# WMHS_Eastern_LI_Invitational_Circuit_Boa.net
KiCad netlist of a schematic drawn in EAGLE
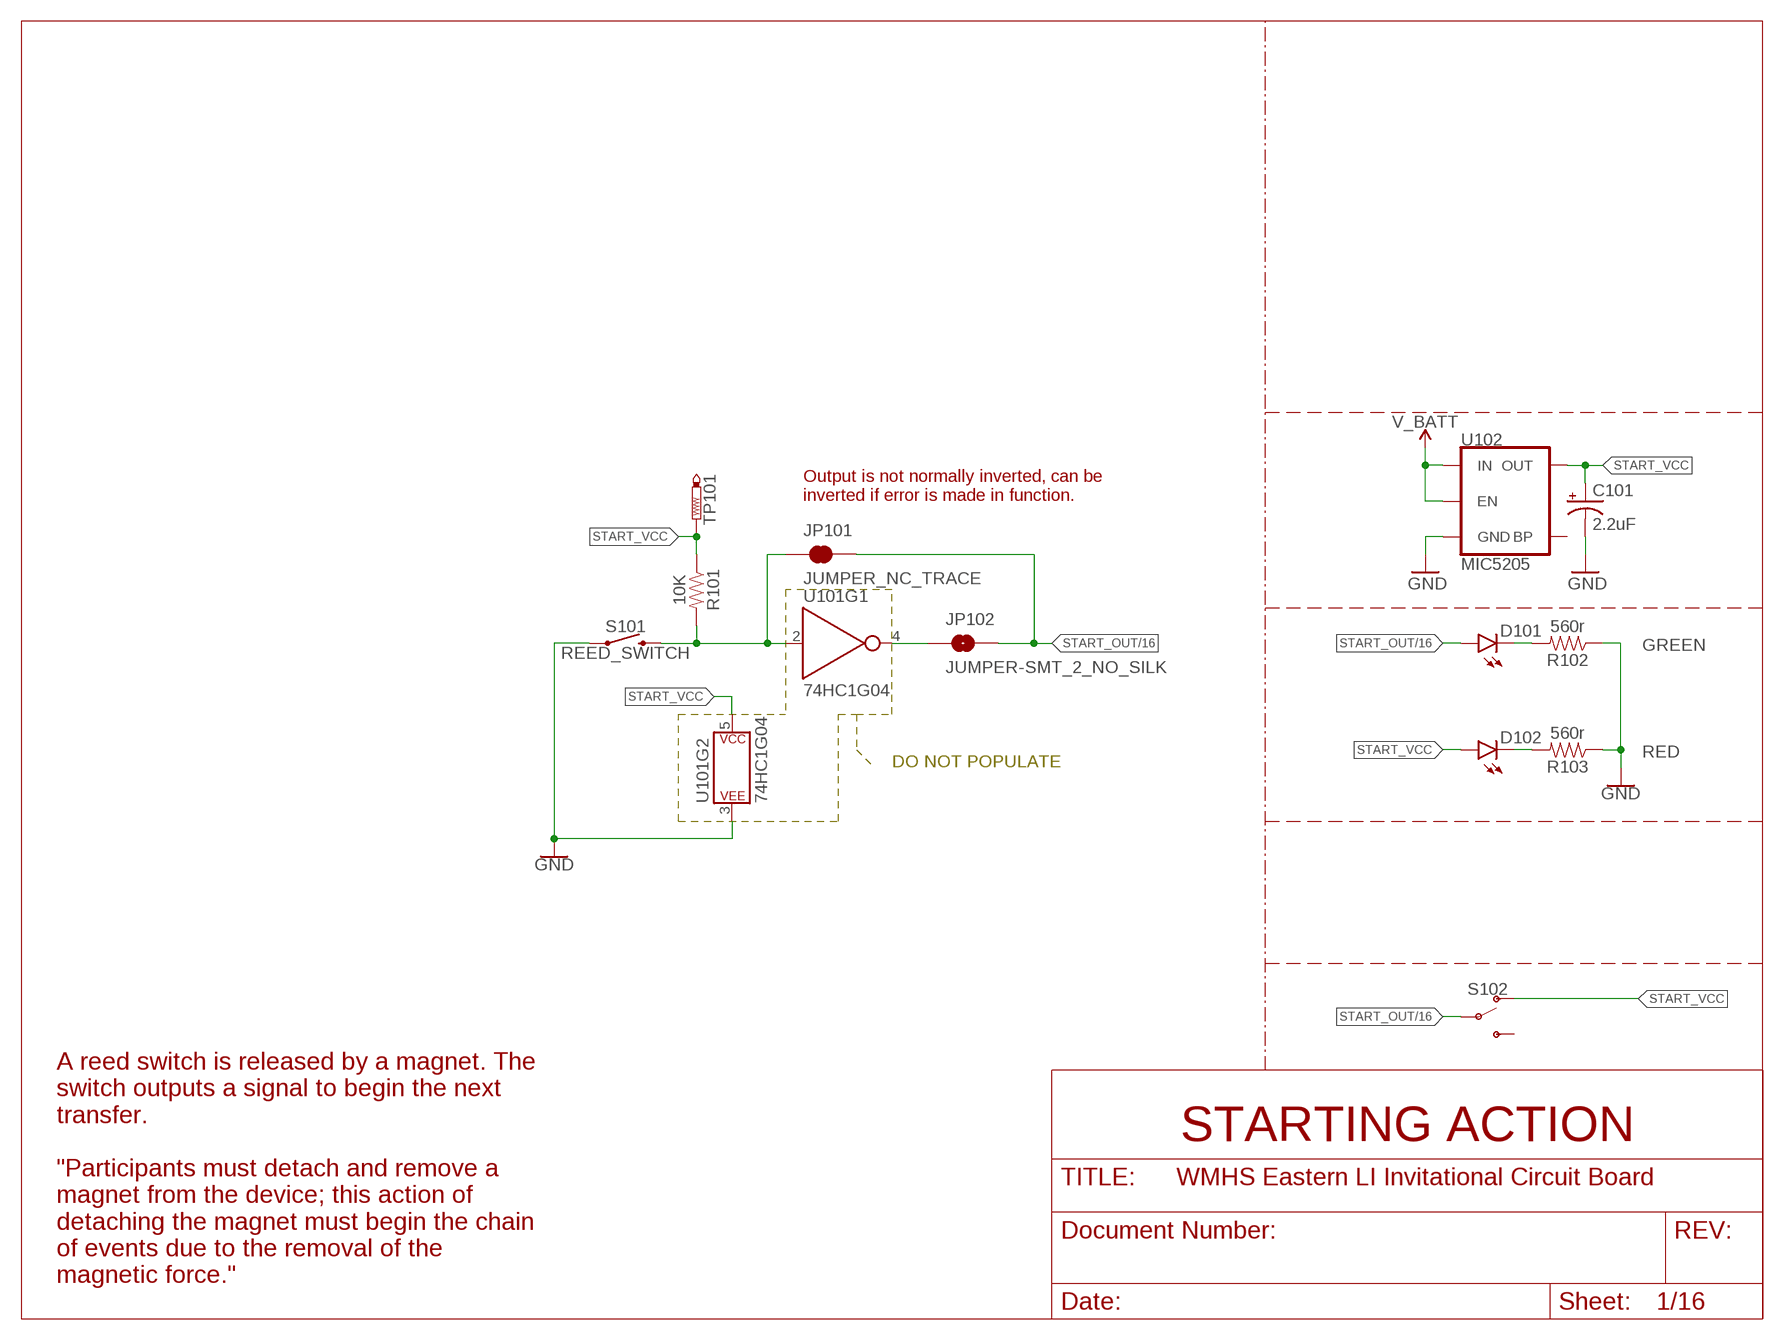
[diagram p0: schematic, sheet 1]
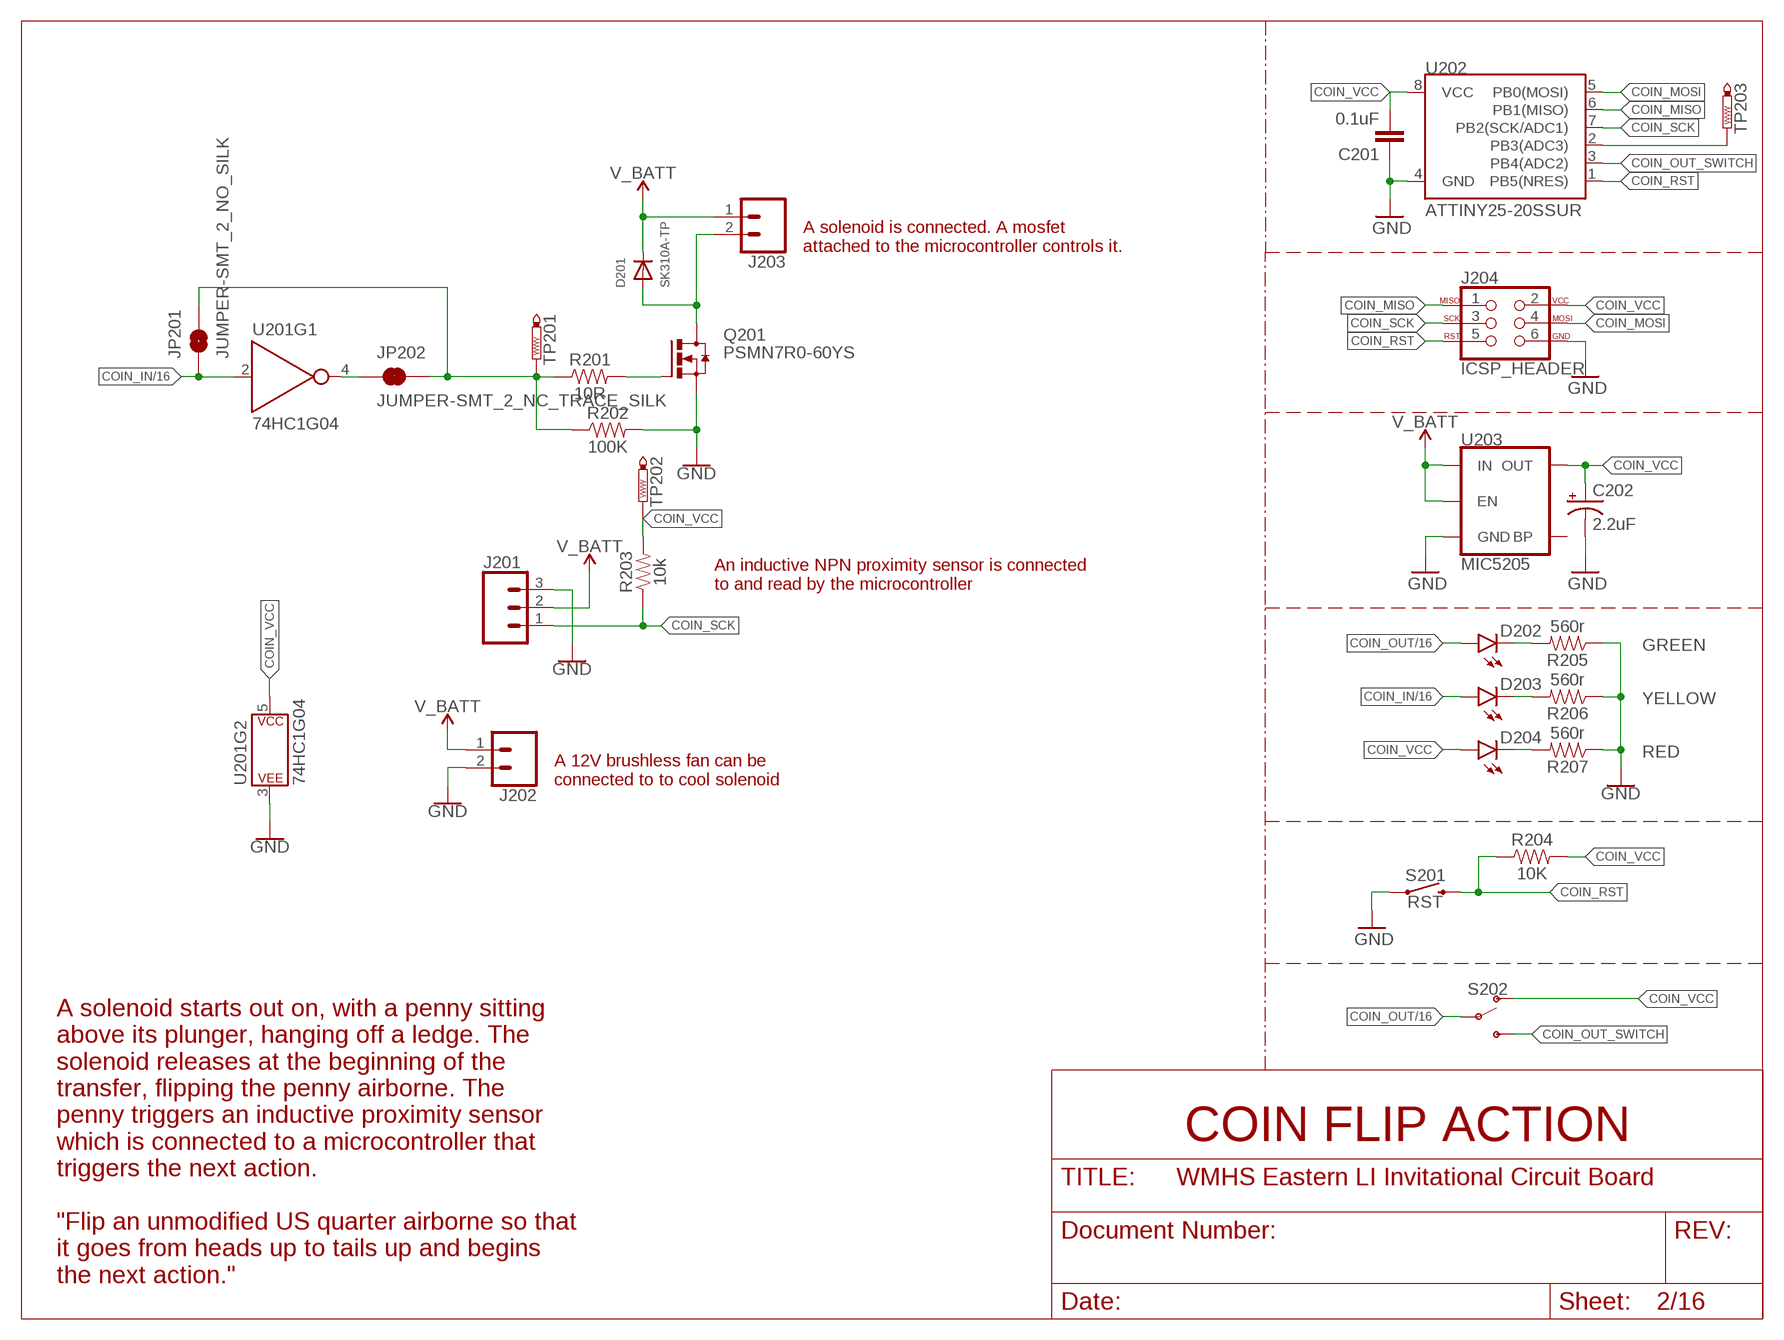
[diagram p1: schematic, sheet 2]
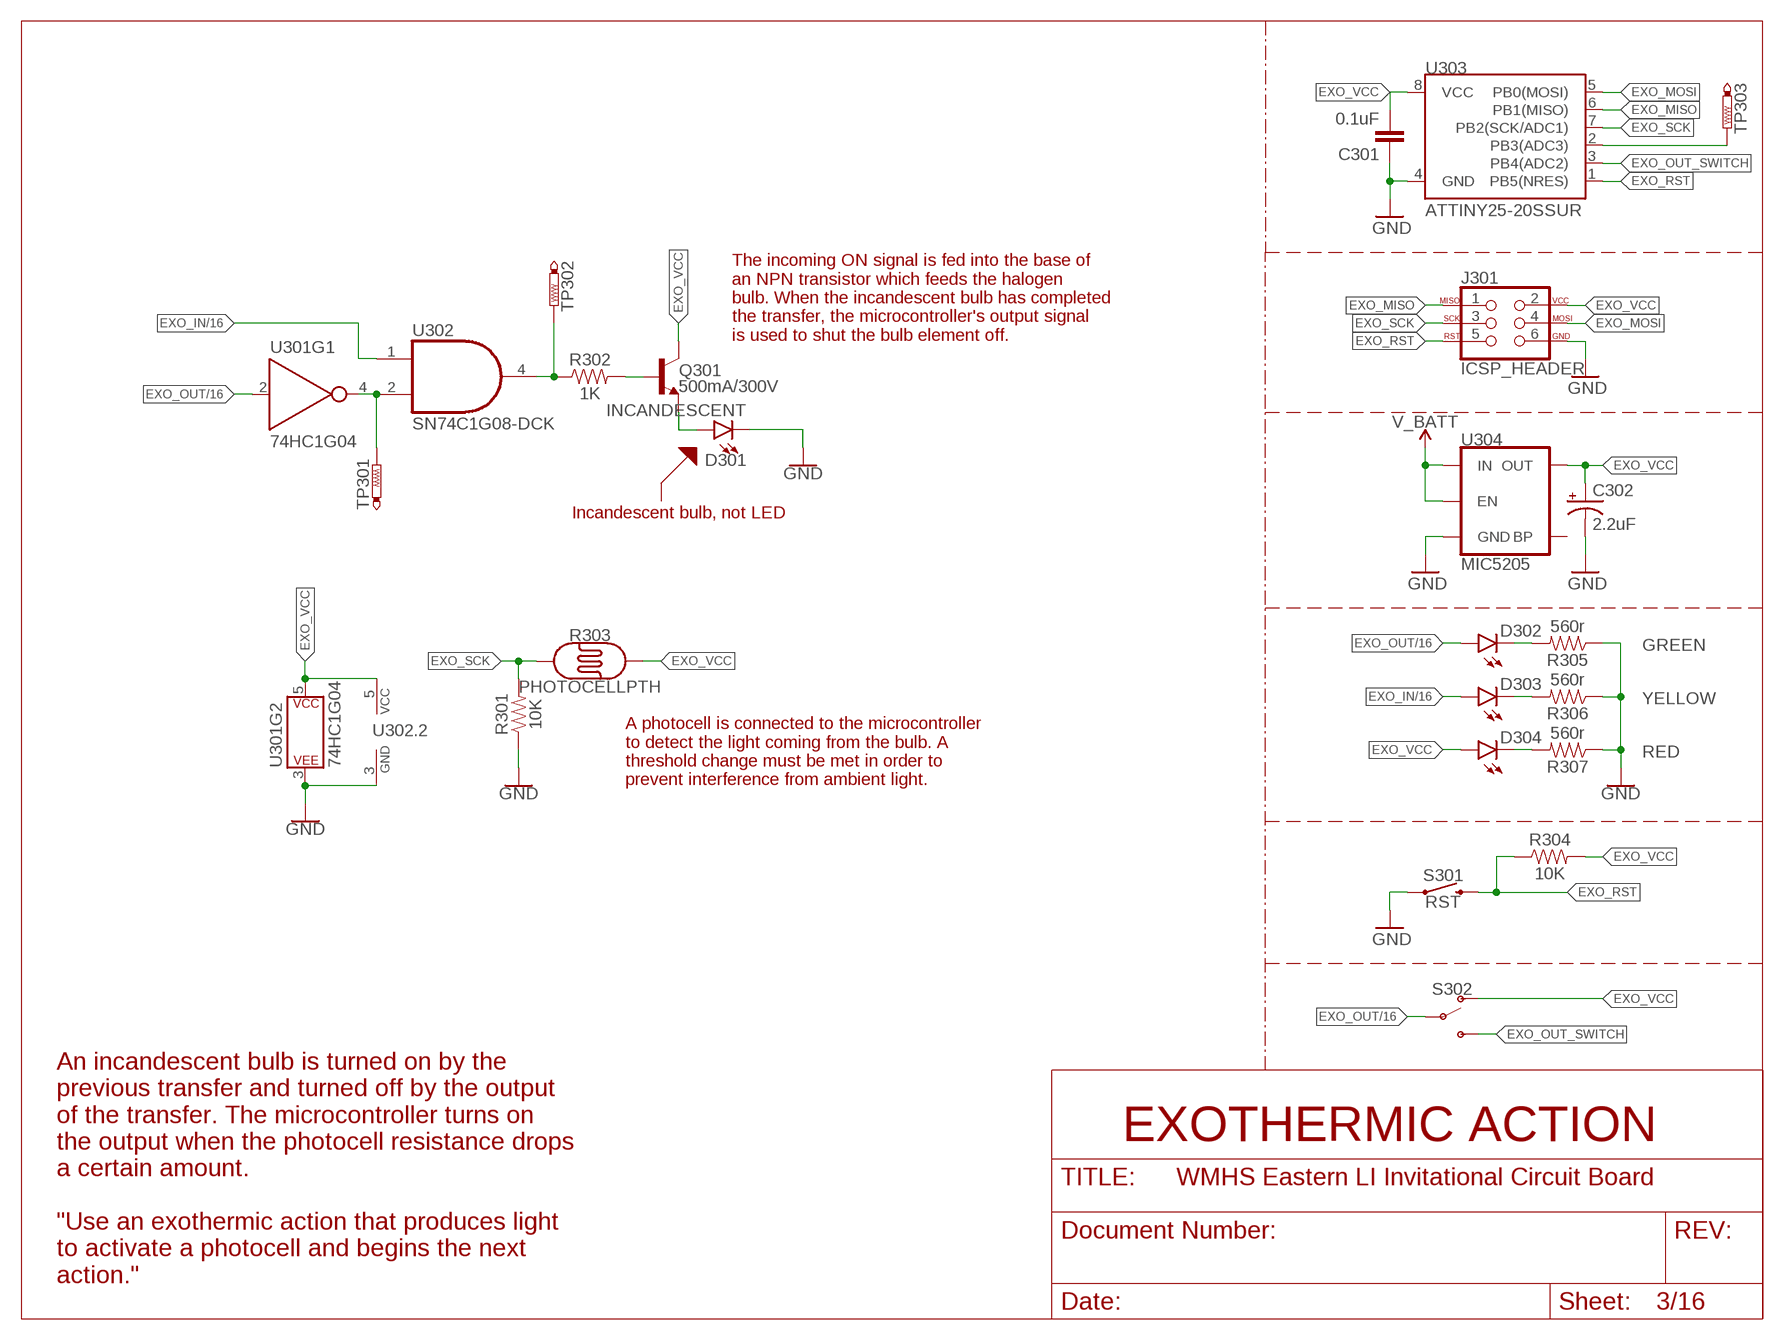
[diagram p2: schematic, sheet 3]
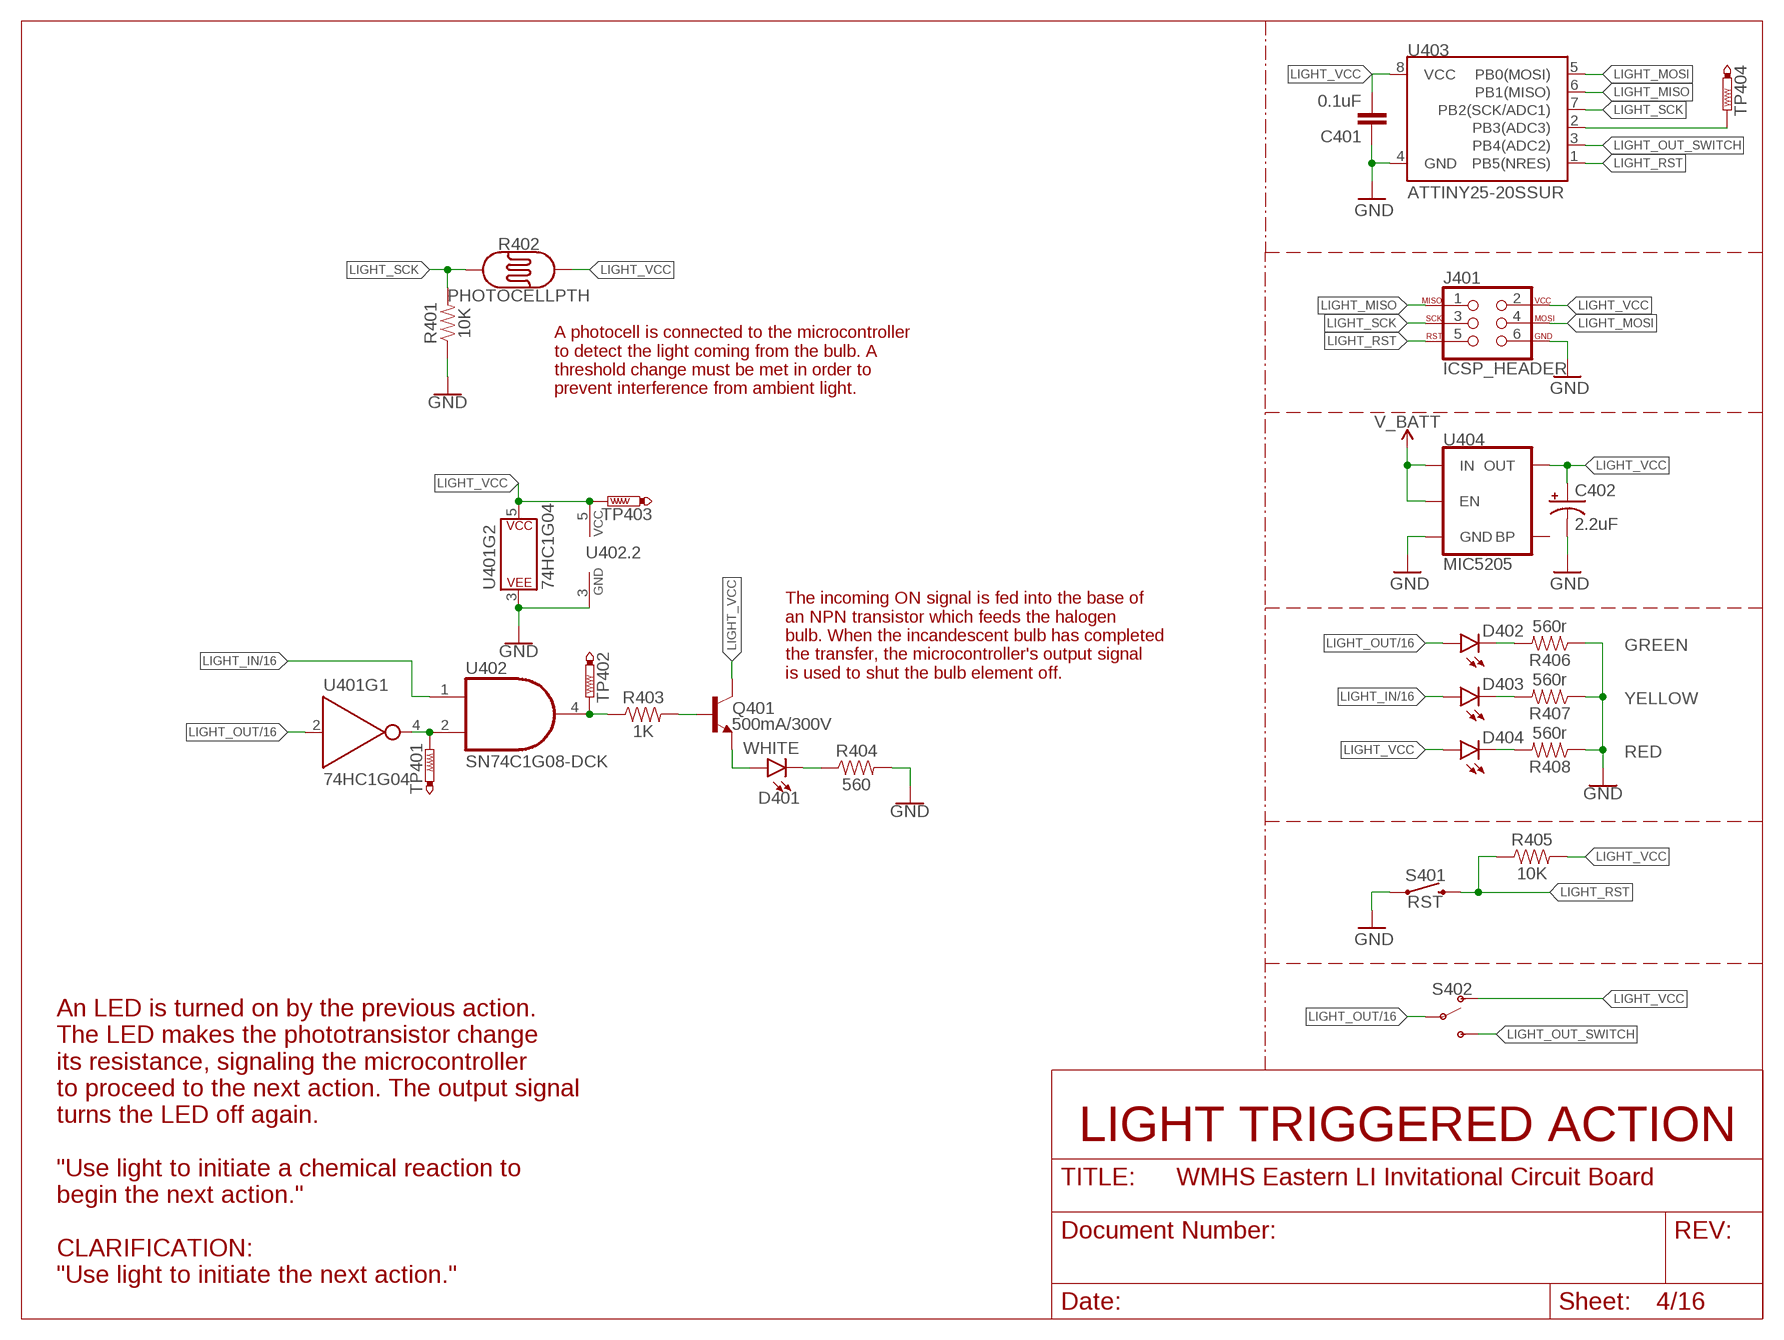
[diagram p3: schematic, sheet 4]
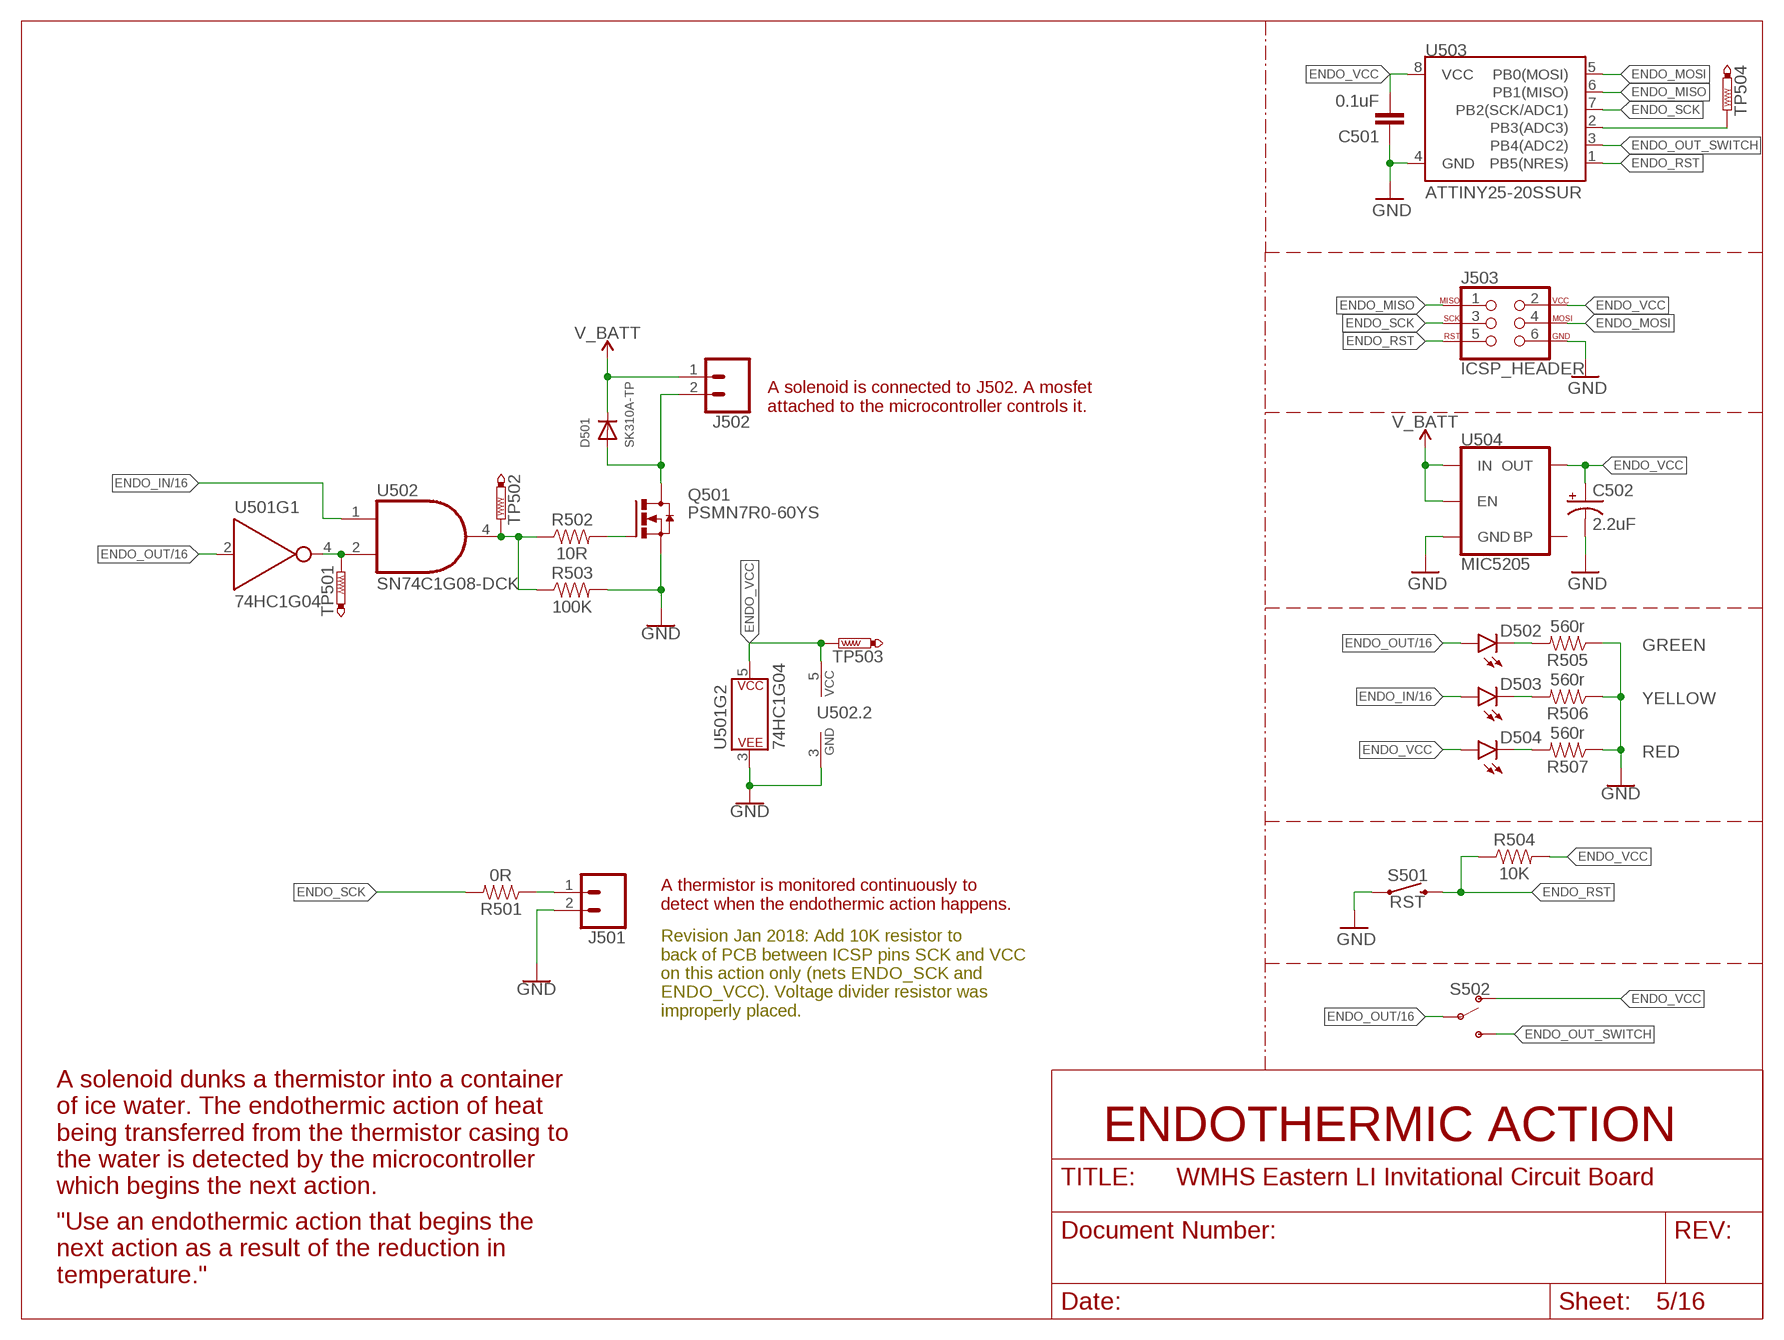
[diagram p4: schematic, sheet 5]
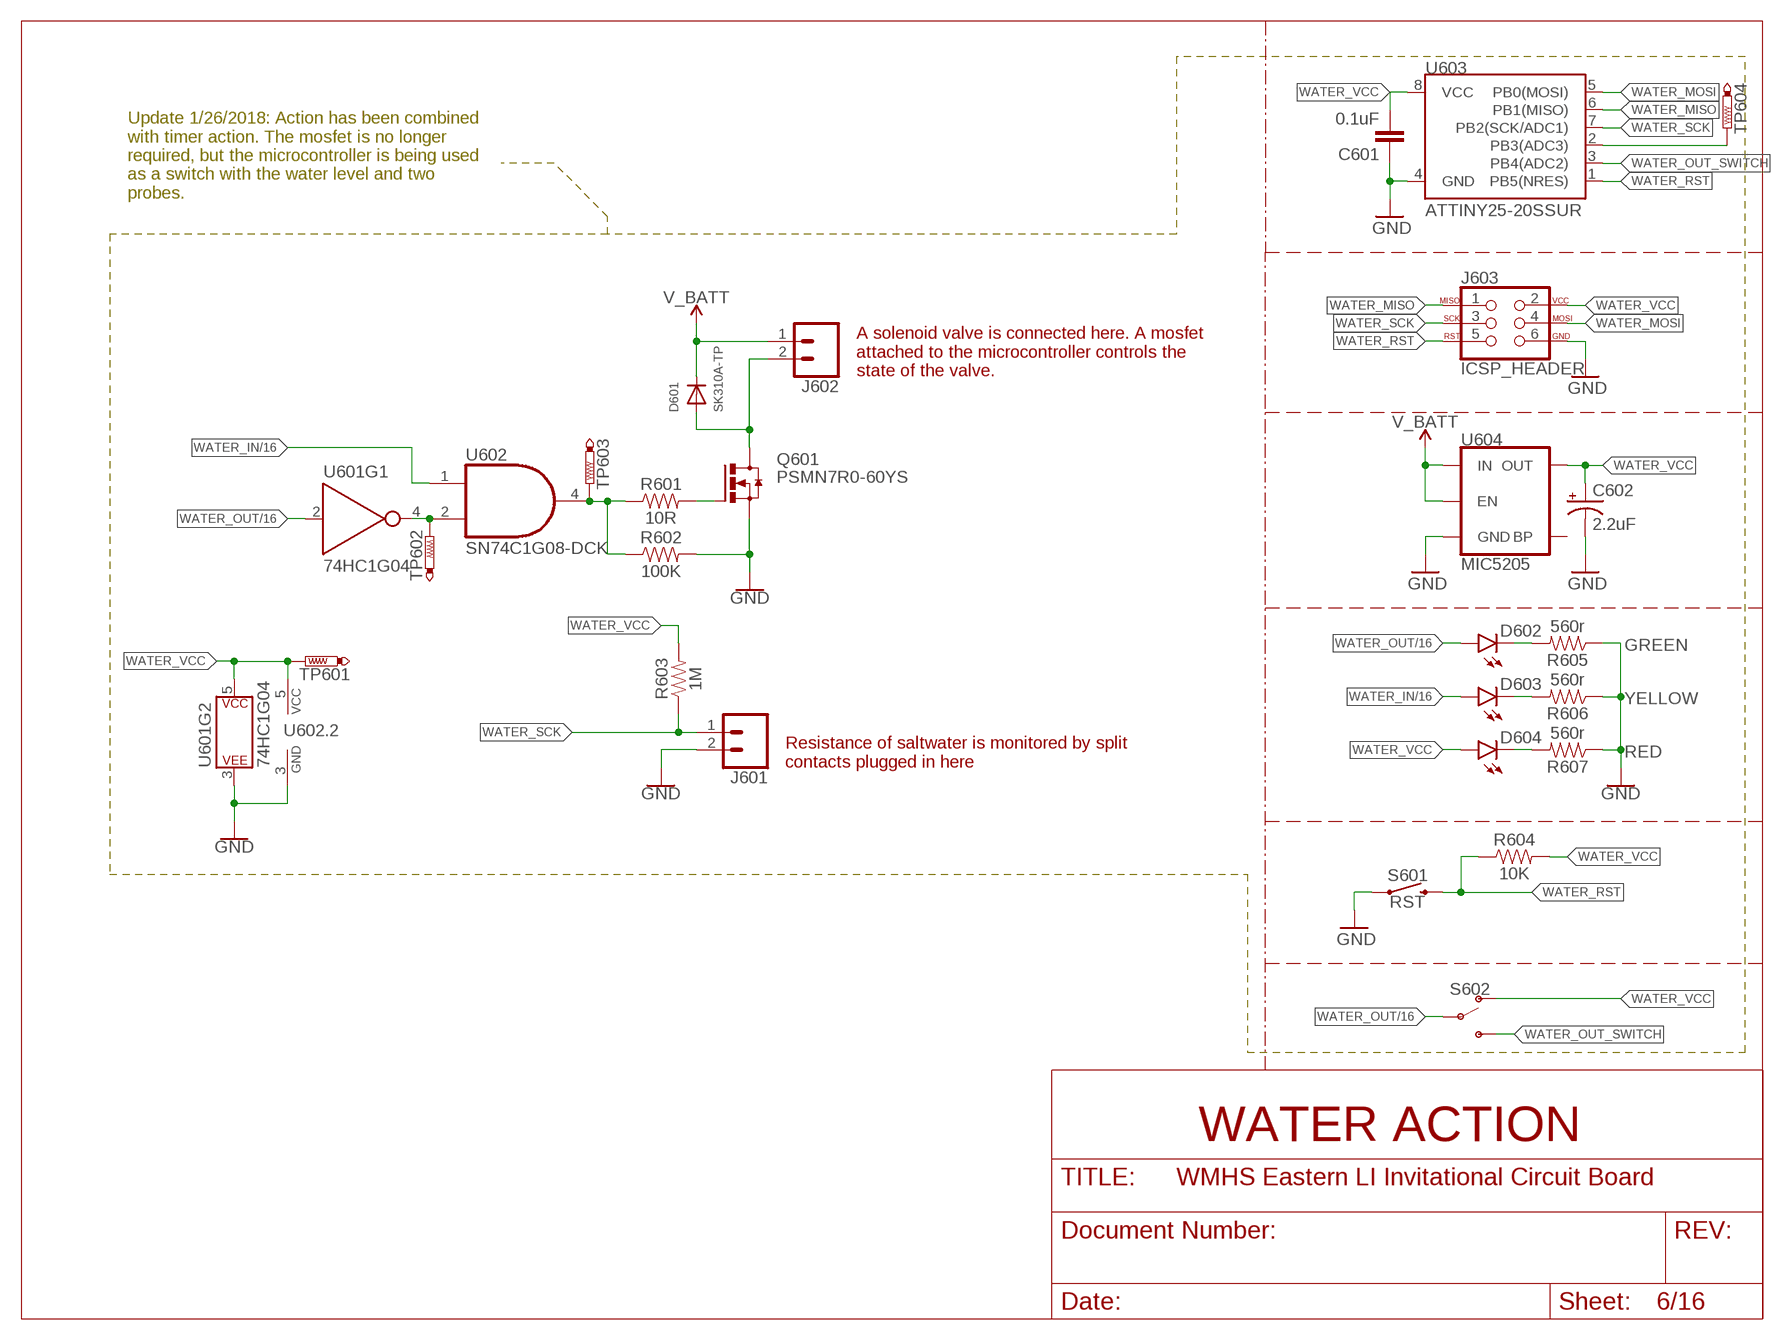
[diagram p5: schematic, sheet 6]
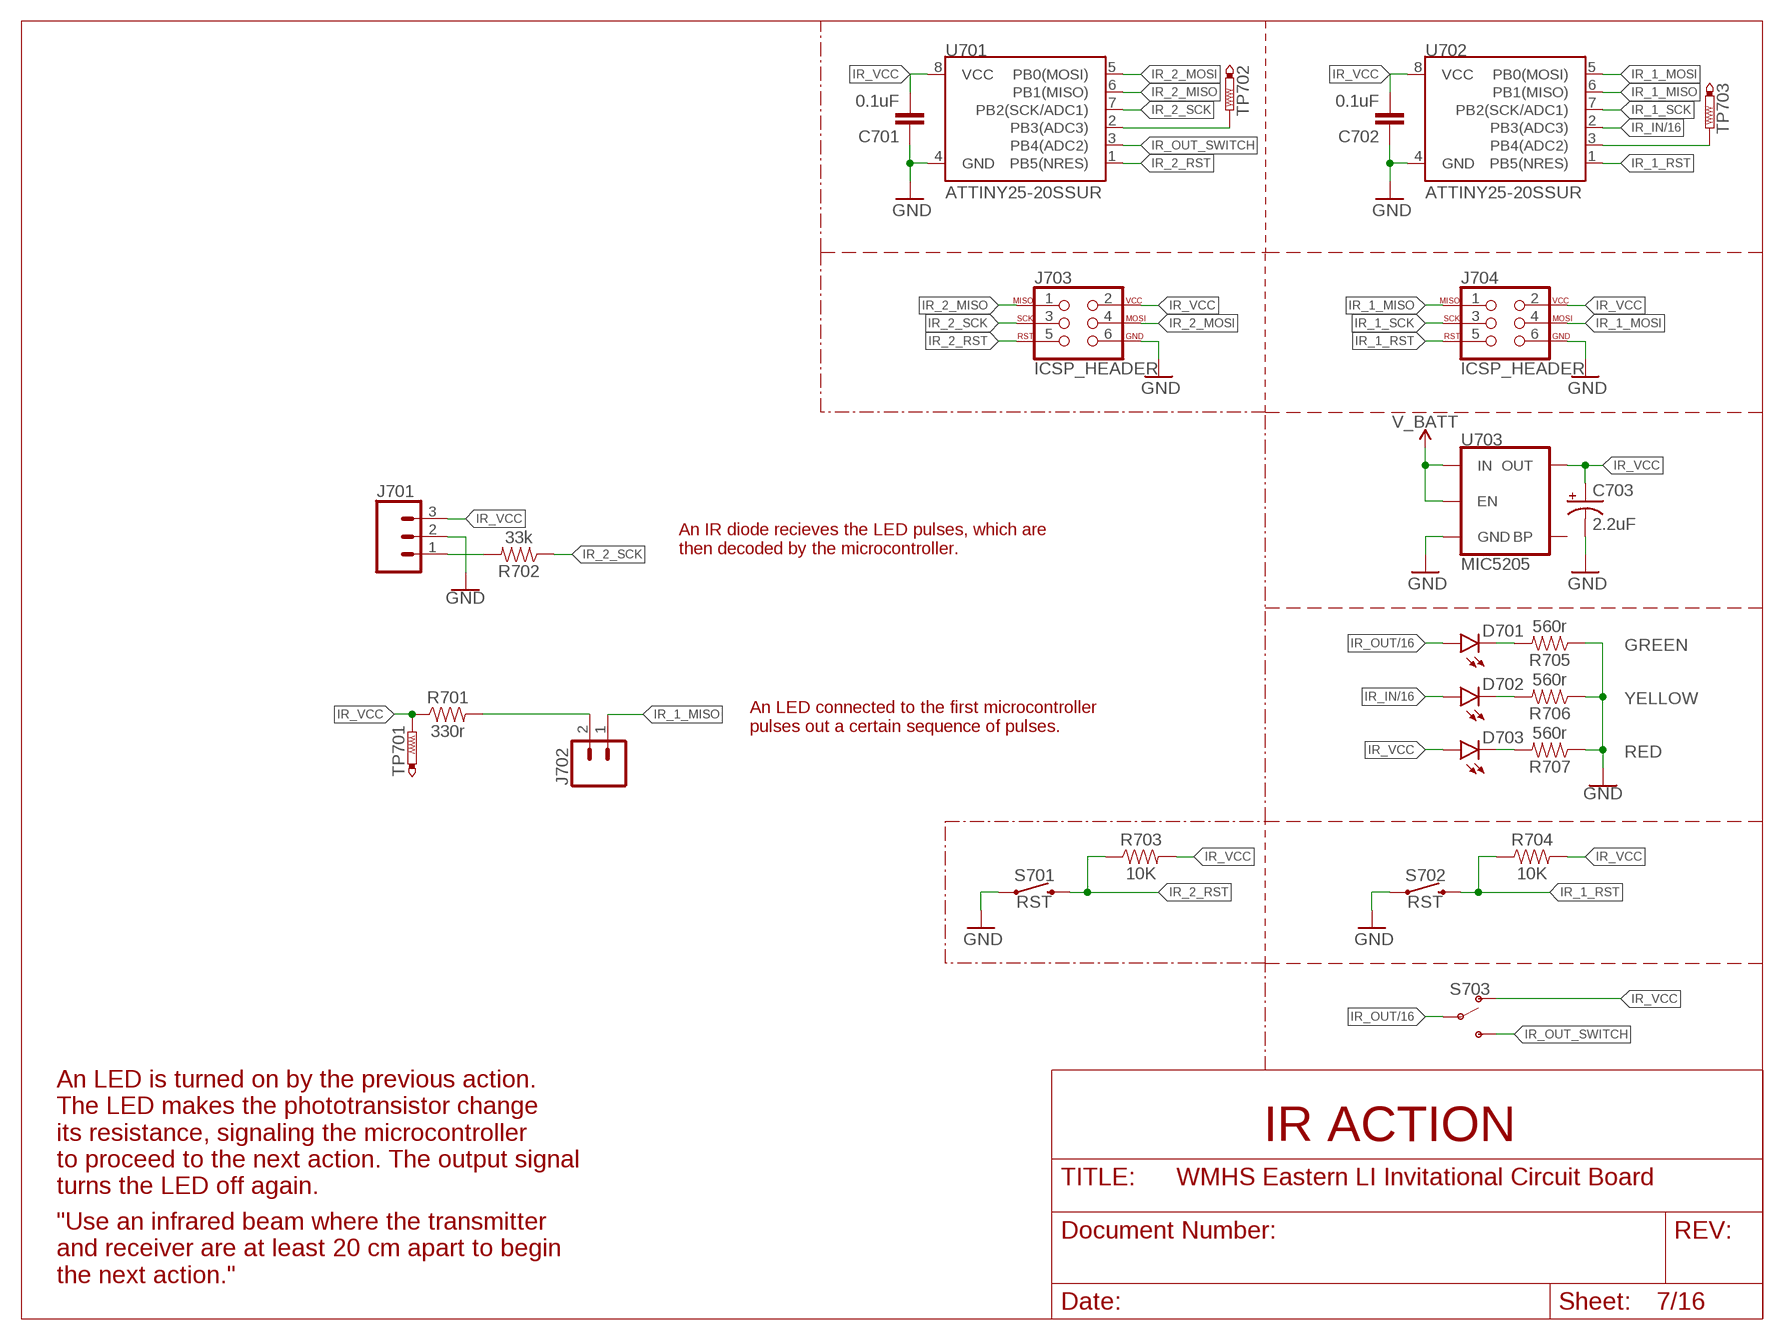
[diagram p6: schematic, sheet 7]
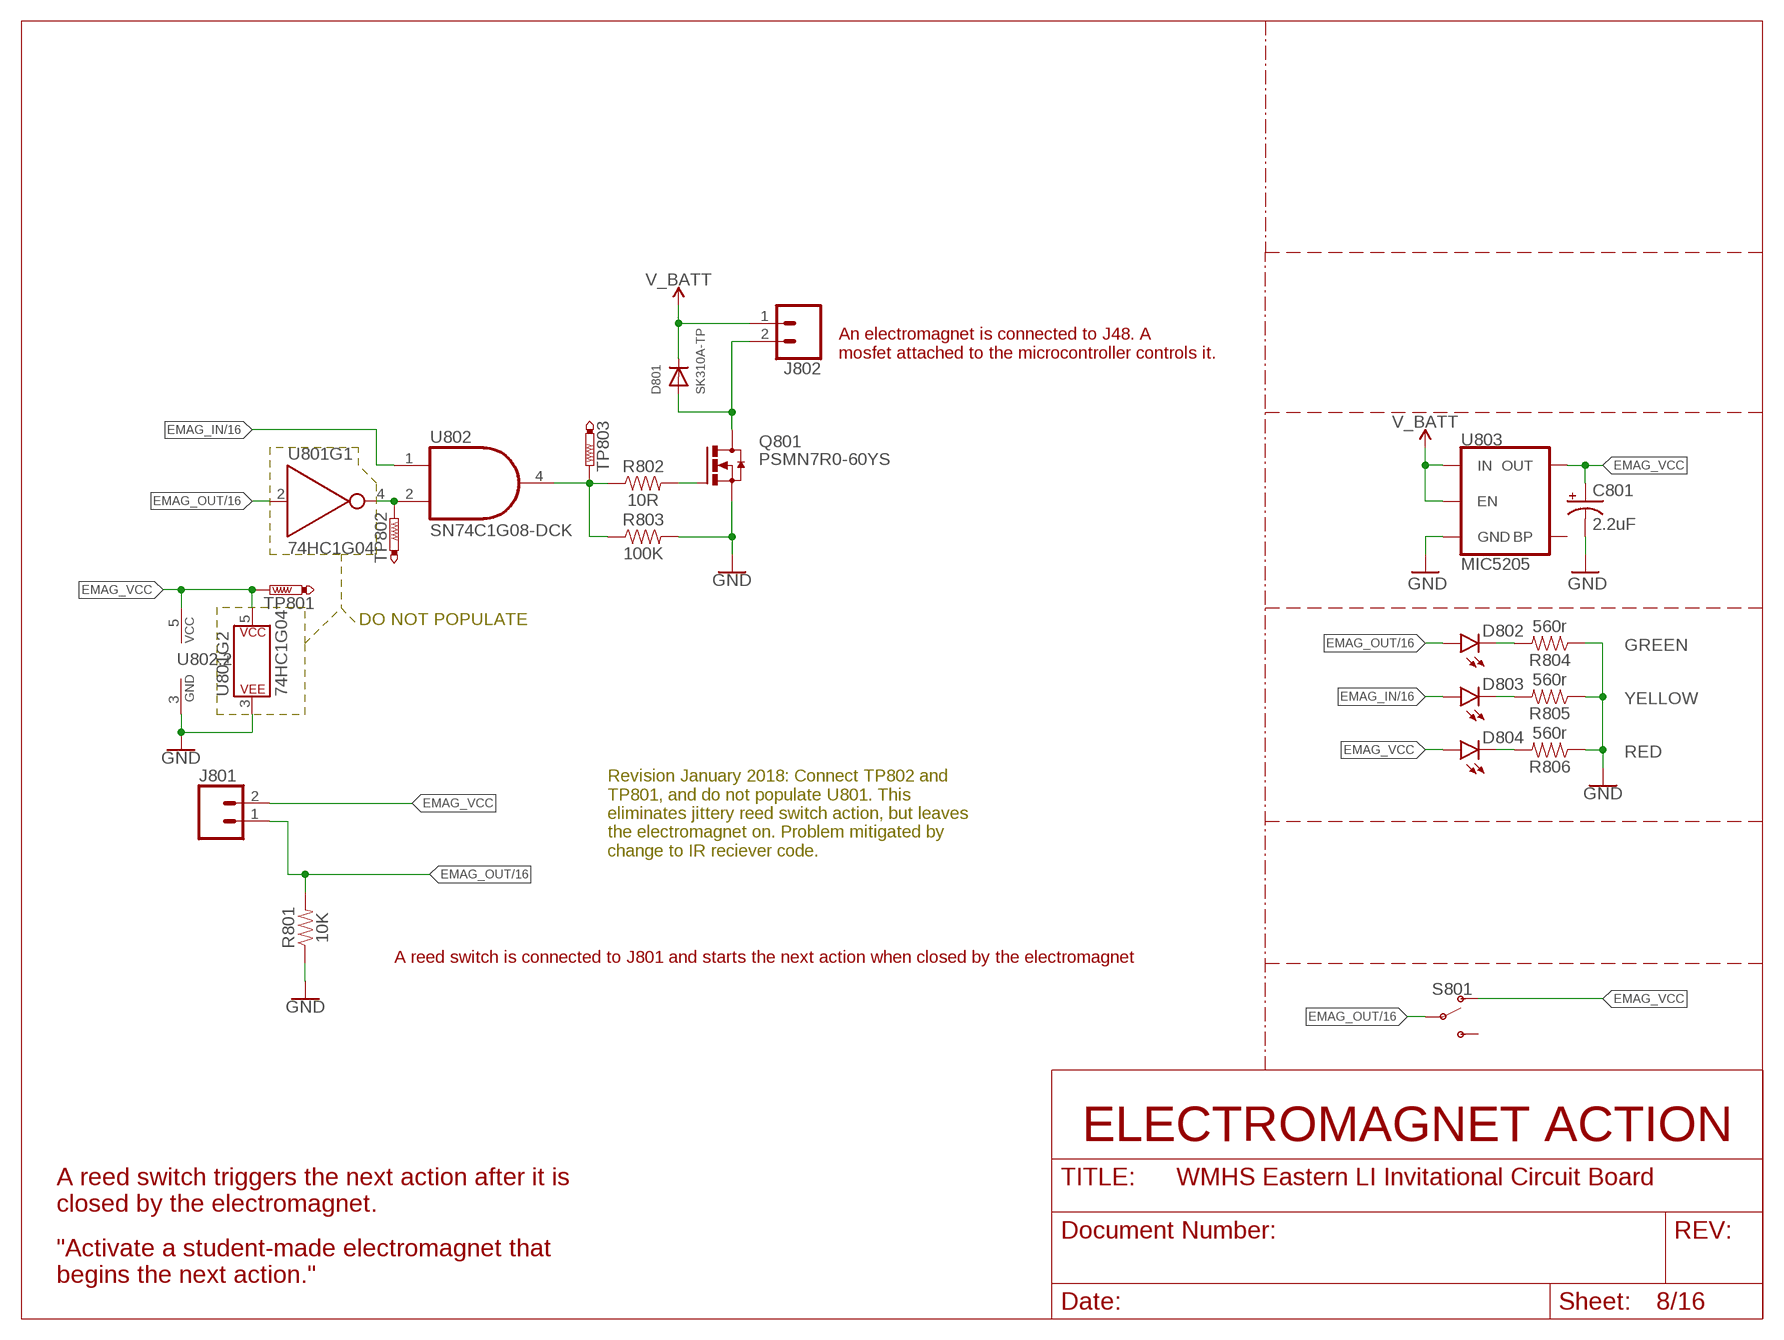
[diagram p7: schematic, sheet 8]
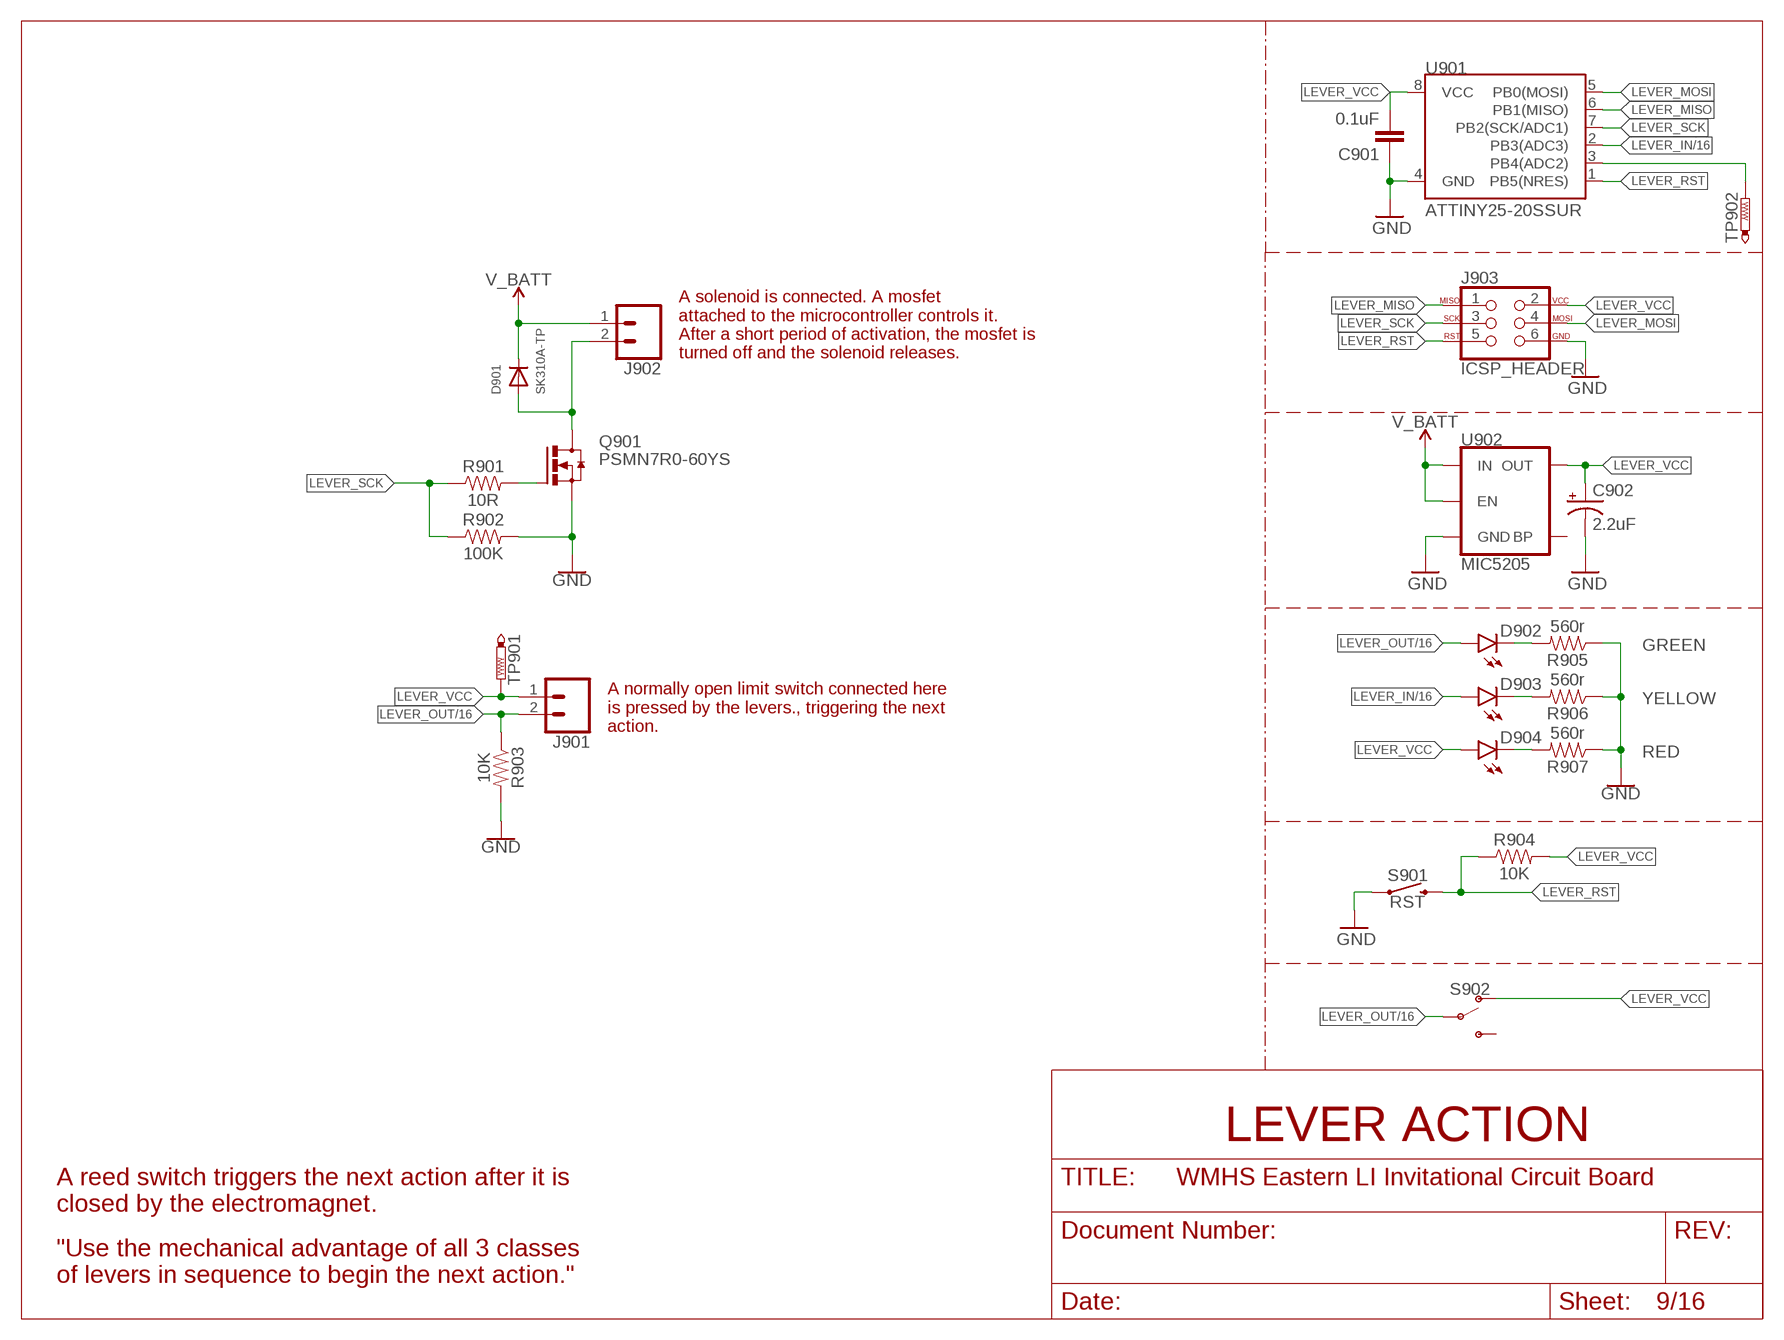
[diagram p8: schematic, sheet 9]
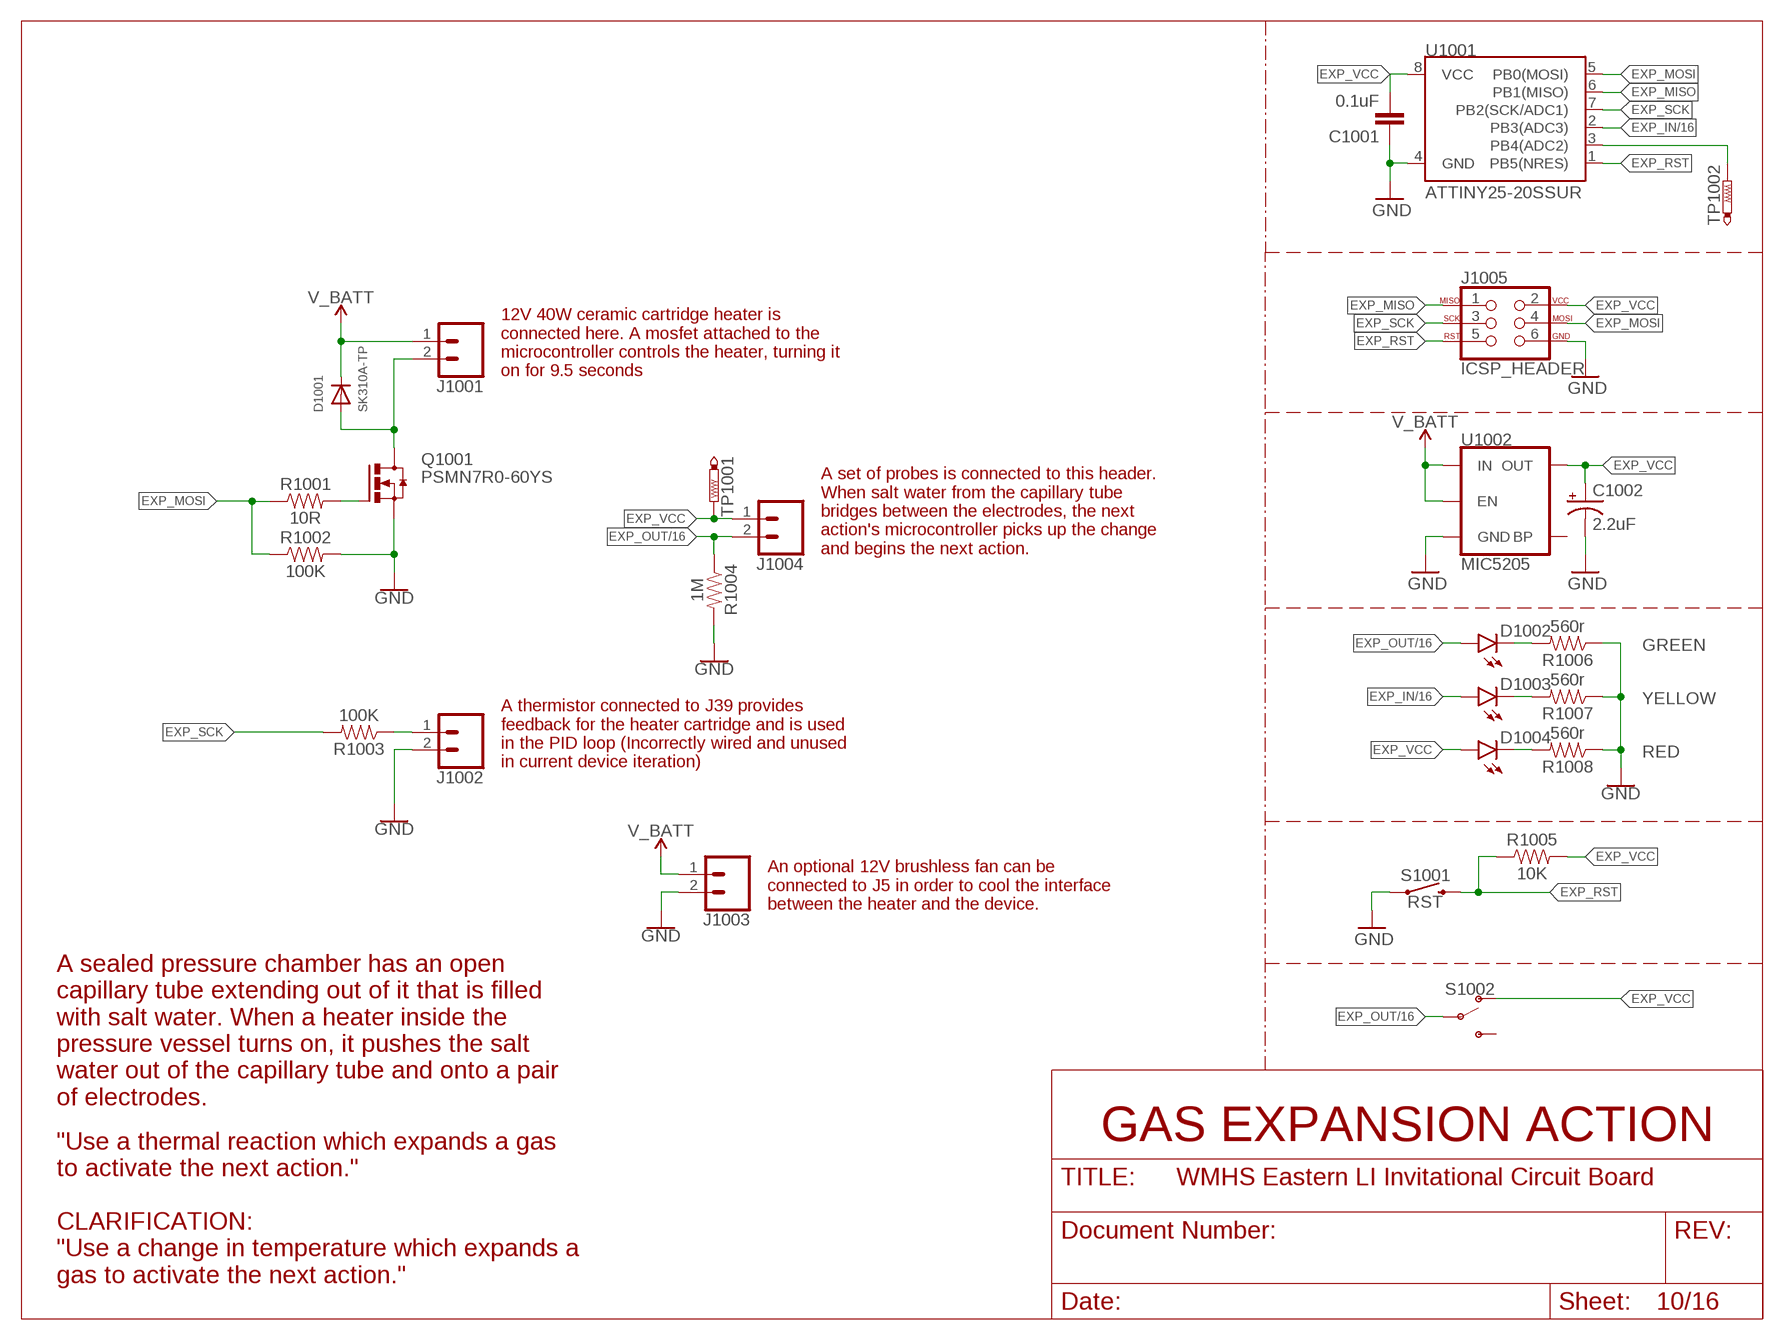
[diagram p9: schematic, sheet 10]
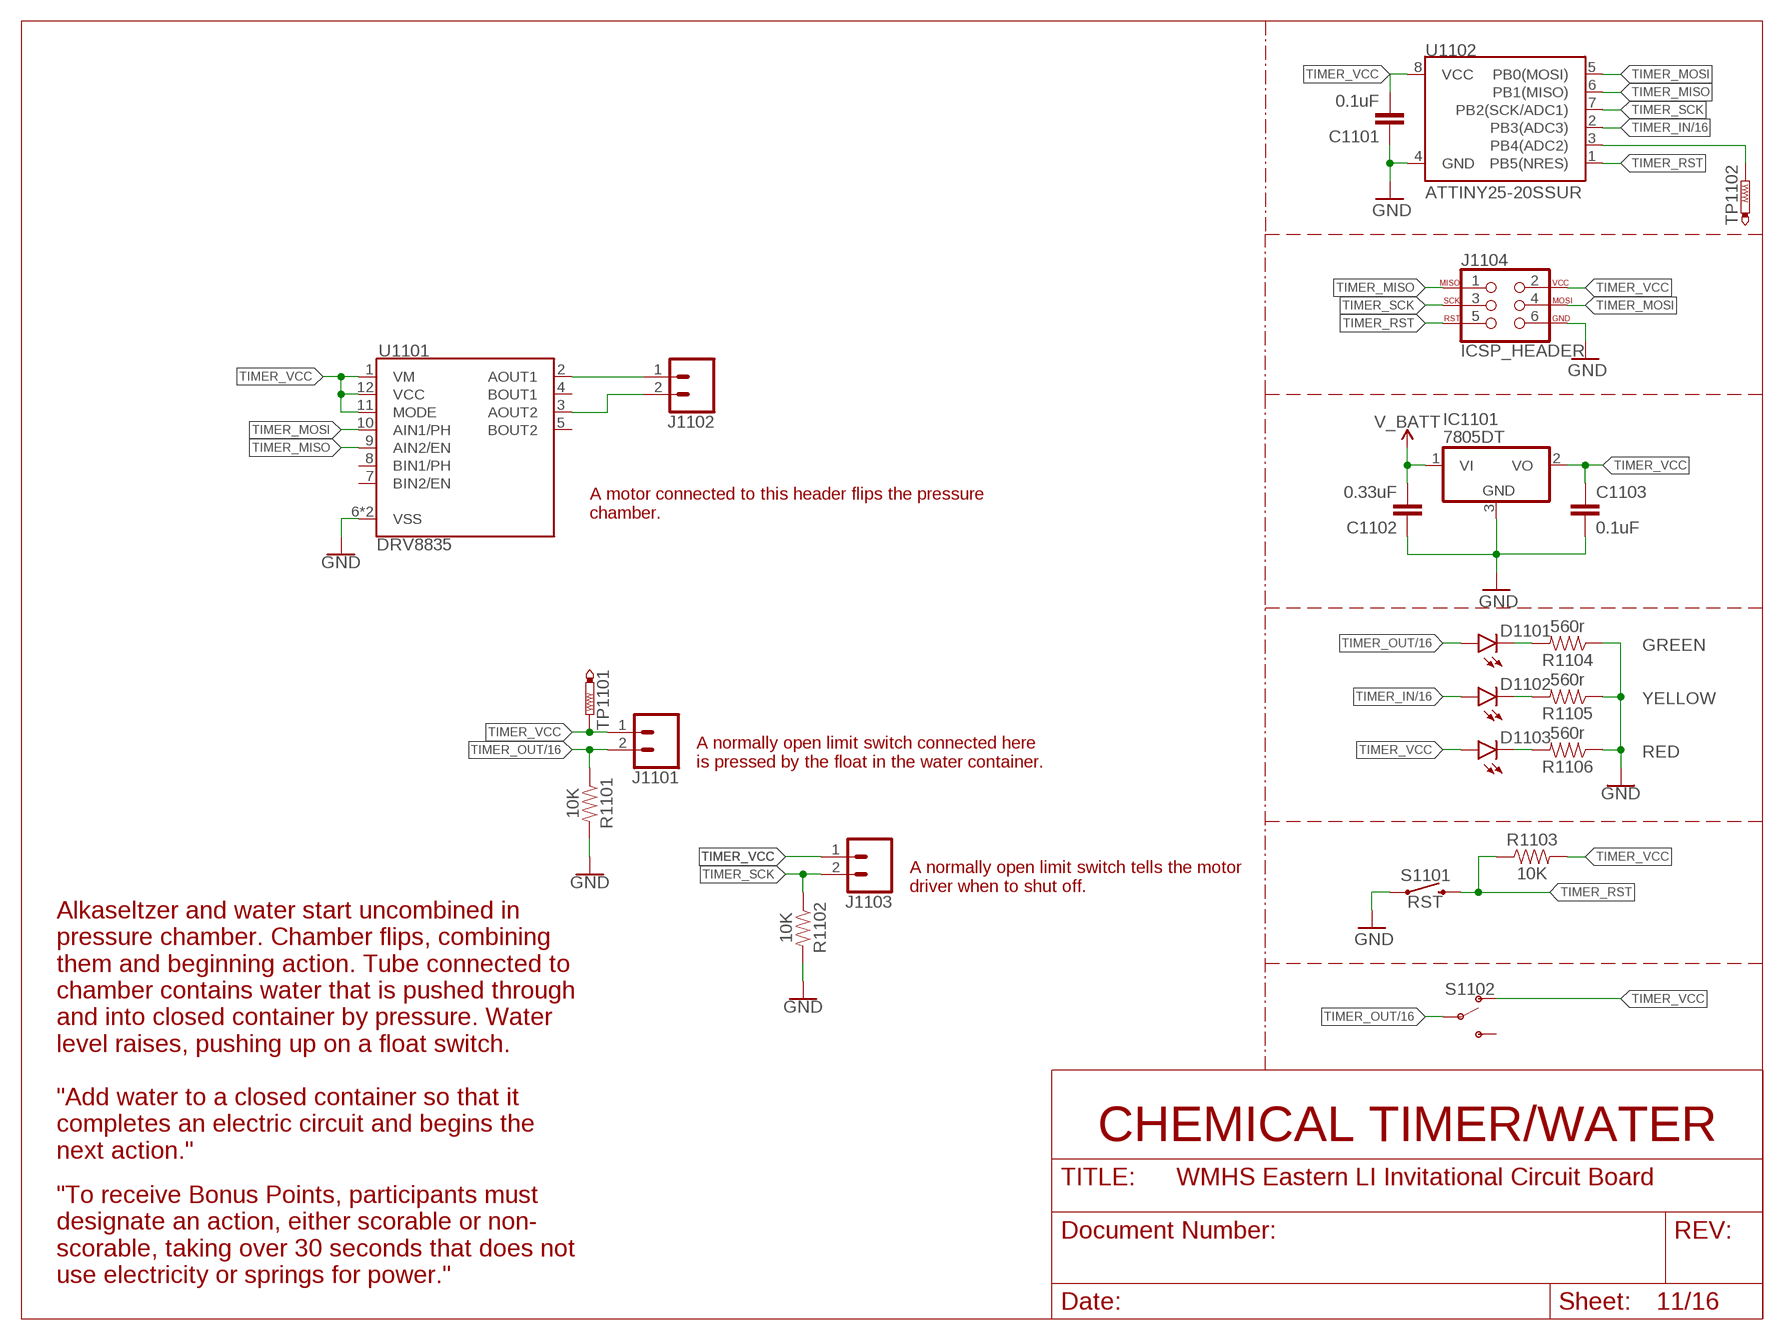
[diagram p10: schematic, sheet 11]
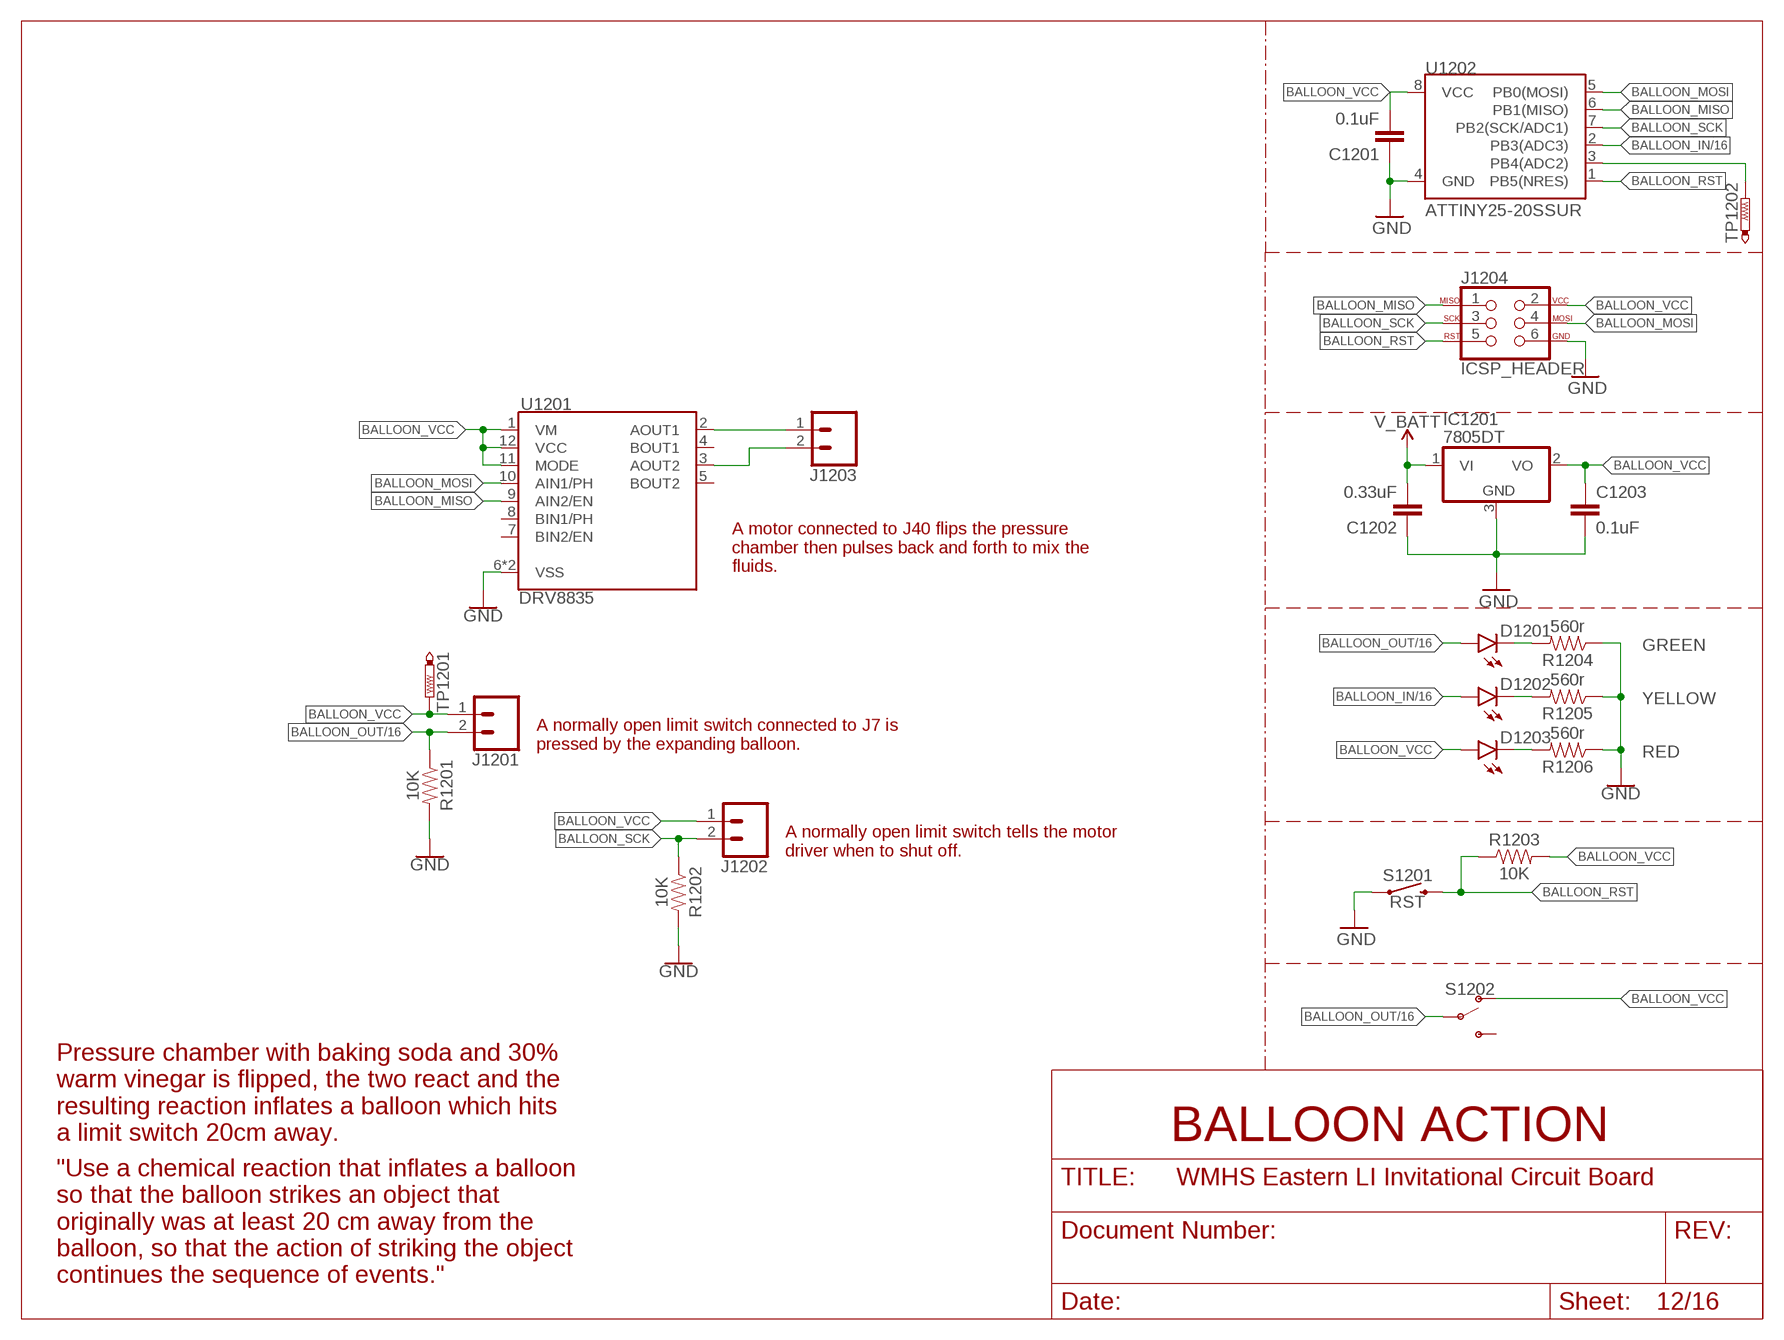
[diagram p11: schematic, sheet 12]
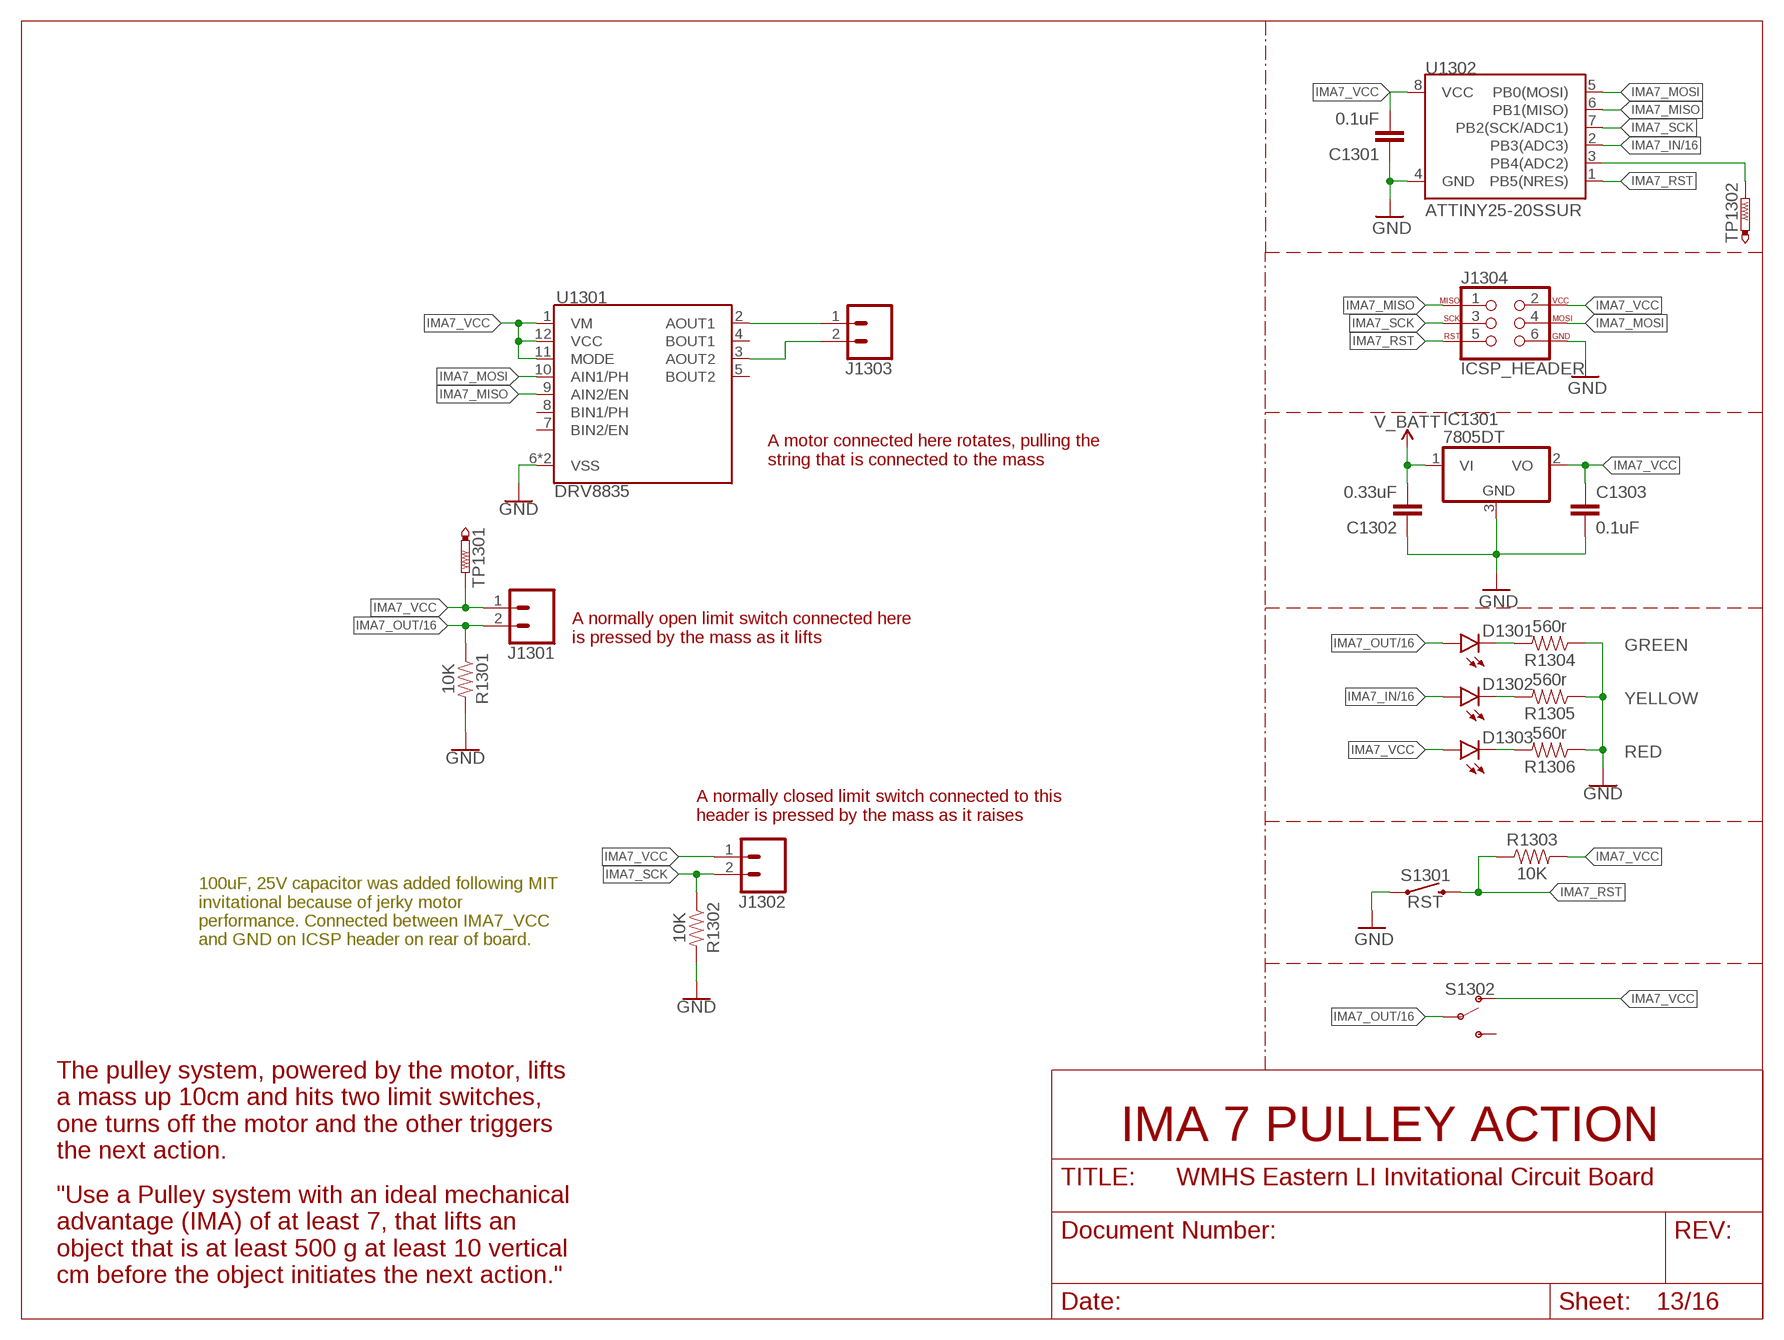
[diagram p12: schematic, sheet 13]
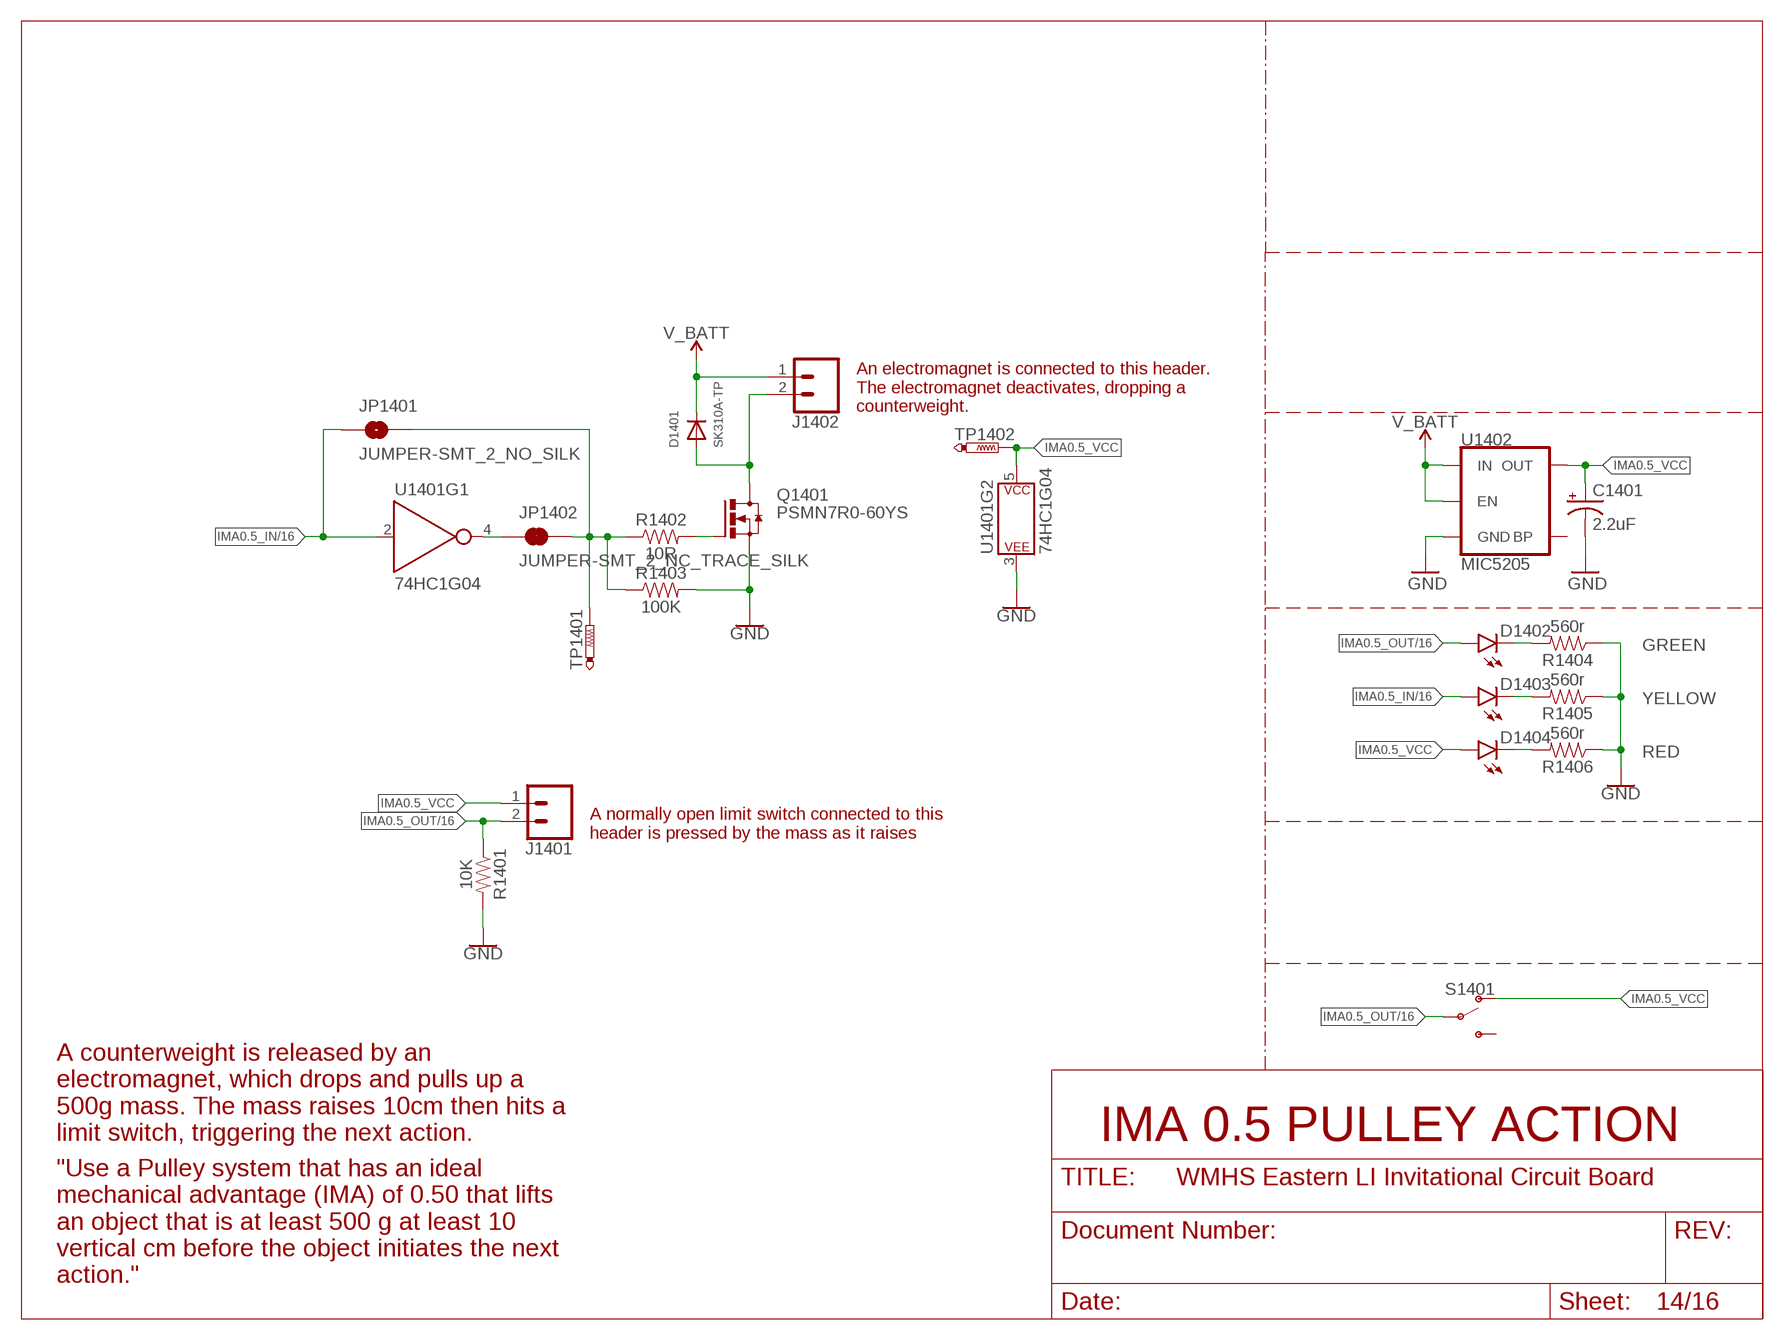
[diagram p13: schematic, sheet 14]
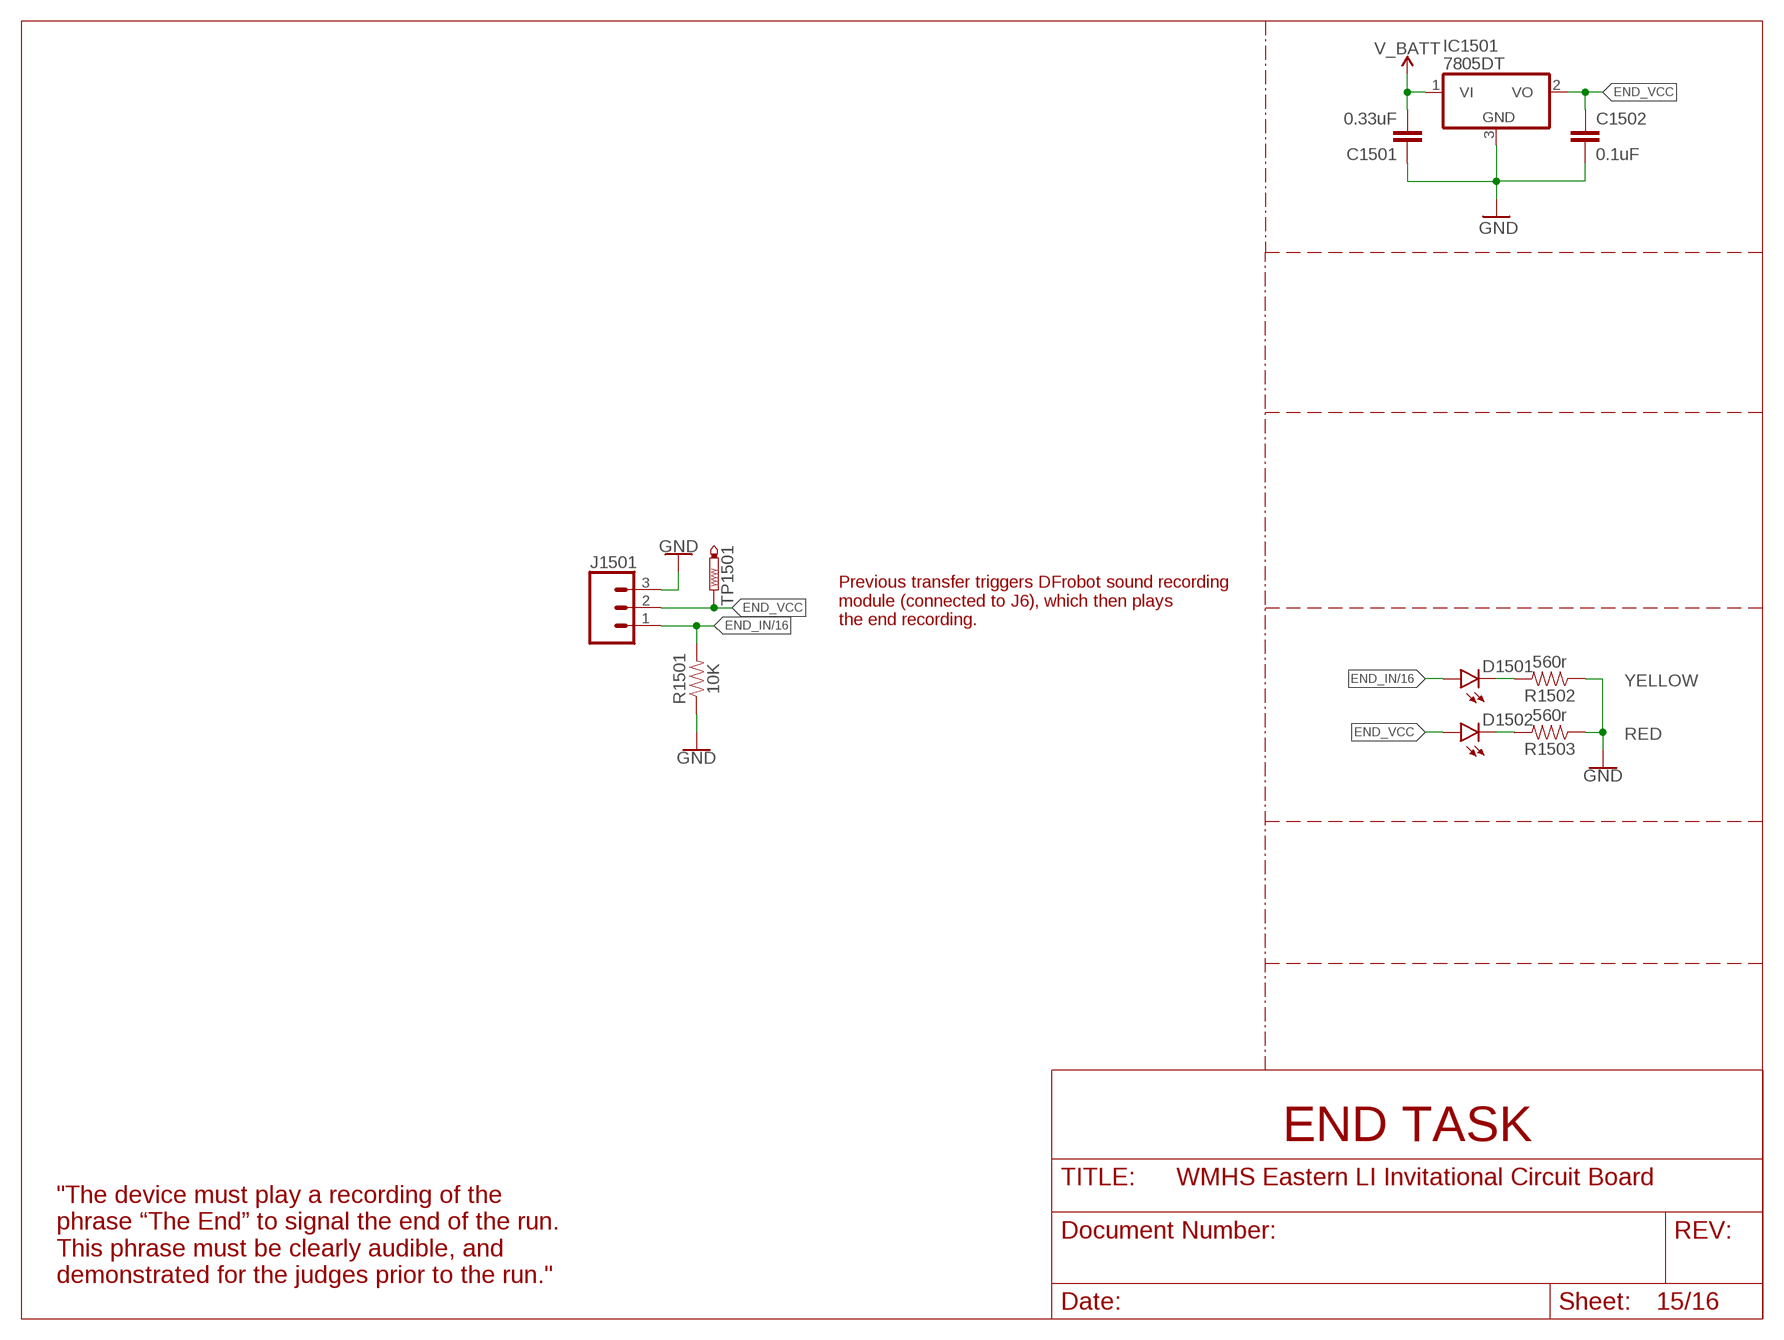
[diagram p14: schematic, sheet 15]
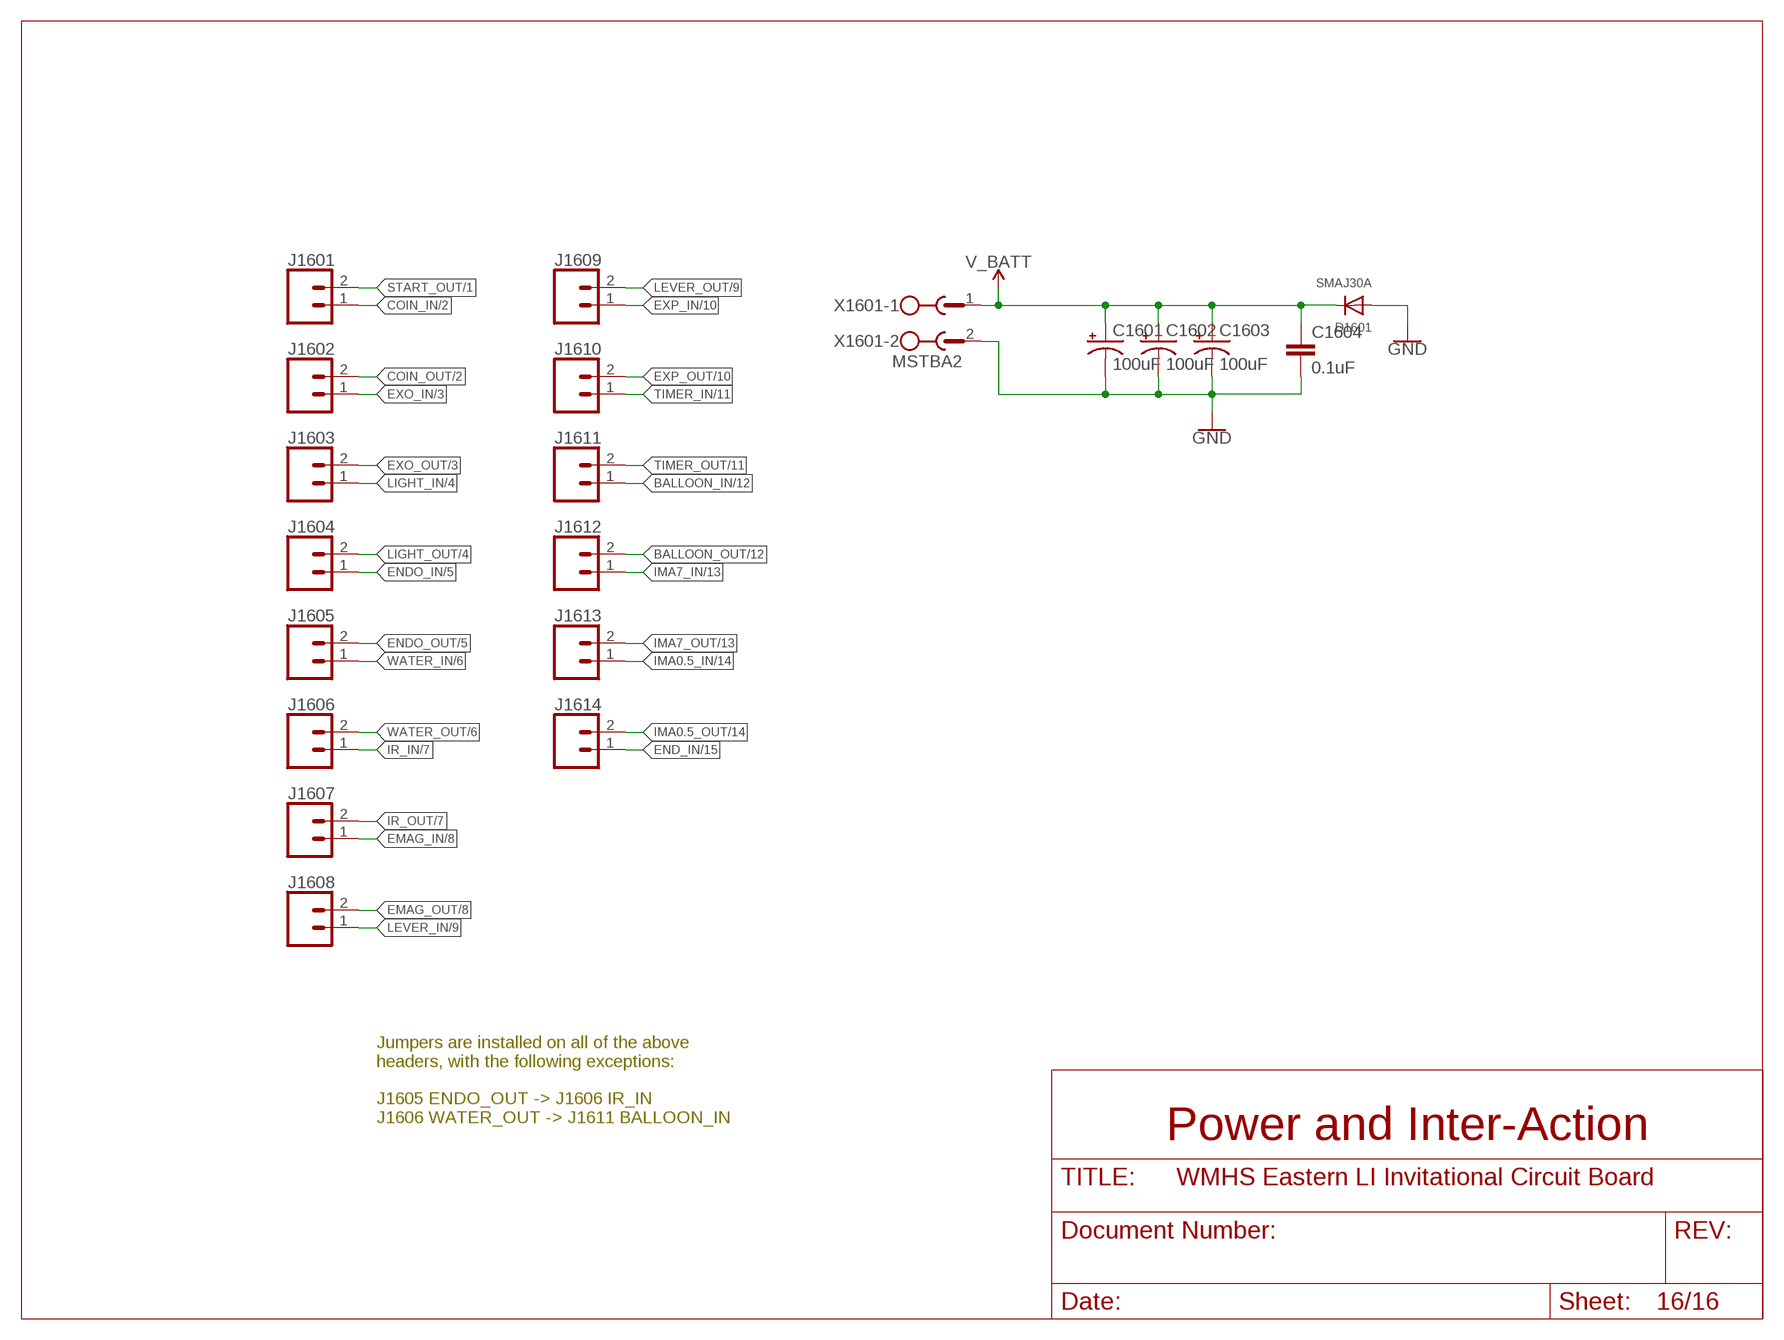
[diagram p15: schematic, sheet 16]

(export (version "E")
  (design (tool "Eeschema 10.0.6"))
  (components
    (comp (ref "C901")
      (value "0.1uF")
      (footprint "eagle-import:0603")
      (libsource (lib "eagle-import") (part "0.1UF-0603-25V-5%"))
    )
    (comp (ref "C902")
      (value "2.2uF")
      (footprint "eagle-import:EIA3216")
      (libsource (lib "eagle-import") (part "10UF-POLAR-EIA3216-16V-10%(TANT)"))
    )
    (comp (ref "D901")
      (value "SK310A-TP")
      (footprint "eagle-import:SMADIODE")
      (libsource (lib "eagle-import") (part "DIODESMA"))
    )
    (comp (ref "D902")
      (value "GREEN")
      (footprint "eagle-import:LED-0603")
      (libsource (lib "eagle-import") (part "LED-GREEN0603"))
    )
    (comp (ref "D903")
      (value "YELLOW")
      (footprint "eagle-import:LED-0603")
      (libsource (lib "eagle-import") (part "LED-YELLOW0603"))
    )
    (comp (ref "D904")
      (value "RED")
      (footprint "eagle-import:LED-0603")
      (libsource (lib "eagle-import") (part "LED-RED0603"))
    )
    (comp (ref "J901")
      (value "CONN_02LOCK")
      (footprint "eagle-import:1X02_LOCK")
      (libsource (lib "eagle-import") (part "CONN_02LOCK"))
    )
    (comp (ref "J902")
      (value "CONN_023.5MM_LOCK")
      (footprint "eagle-import:SCREWTERMINAL-3.5MM-2_LOCK")
      (libsource (lib "eagle-import") (part "CONN_023.5MM_LOCK"))
    )
    (comp (ref "J903")
      (value "ICSP_HEADER")
      (footprint "eagle-import:2X3")
      (libsource (lib "eagle-import") (part "AVR_SPI_PROG_3X2PTH"))
    )
    (comp (ref "Q901")
      (value "PSMN7R0-60YS")
      (footprint "eagle-import:SOT669")
      (libsource (lib "eagle-import") (part "PSMN7R0-60YS"))
    )
    (comp (ref "R901")
      (value "10R")
      (footprint "eagle-import:0603")
      (libsource (lib "eagle-import") (part "RESISTOR0603"))
    )
    (comp (ref "R902")
      (value "100K")
      (footprint "eagle-import:0603")
      (libsource (lib "eagle-import") (part "RESISTOR0603"))
    )
    (comp (ref "R903")
      (value "10K")
      (footprint "eagle-import:0603")
      (libsource (lib "eagle-import") (part "RESISTOR0603"))
    )
    (comp (ref "R904")
      (value "10K")
      (footprint "eagle-import:0603")
      (libsource (lib "eagle-import") (part "330OHM-0603-1/10W-1%"))
    )
    (comp (ref "R905")
      (value "560r")
      (footprint "eagle-import:0603")
      (libsource (lib "eagle-import") (part "330OHM-0603-1/10W-1%"))
    )
    (comp (ref "R906")
      (value "560r")
      (footprint "eagle-import:0603")
      (libsource (lib "eagle-import") (part "330OHM-0603-1/10W-1%"))
    )
    (comp (ref "R907")
      (value "560r")
      (footprint "eagle-import:0603")
      (libsource (lib "eagle-import") (part "330OHM-0603-1/10W-1%"))
    )
    (comp (ref "S901")
      (value "RST")
      (footprint "eagle-import:TACTILE_SWITCH_SMD_5.2MM")
      (libsource (lib "eagle-import") (part "MOMENTARY-SWITCH-SPST-SMD-5.2-REDUNDANT"))
    )
    (comp (ref "S902")
      (value "SWITCH-SPDT-SMD-AYZ0202")
      (footprint "eagle-import:SWITCH_DPDT_SMD_AYZ0202")
      (libsource (lib "eagle-import") (part "SWITCH-SPDT-SMD-AYZ0202"))
    )
    (comp (ref "TP901")
      (value "PTR1TP20R")
      (footprint "eagle-import:TP20R")
      (libsource (lib "eagle-import") (part "PTR1TP20R"))
    )
    (comp (ref "TP902")
      (value "PTR1TP20R")
      (footprint "eagle-import:TP20R")
      (libsource (lib "eagle-import") (part "PTR1TP20R"))
    )
    (comp (ref "U901")
      (value "ATTINY25-20SSUR")
      (footprint "eagle-import:SOIC8")
      (libsource (lib "eagle-import") (part "ATTINY45-SMT-NARROW"))
    )
    (comp (ref "U902")
      (value "MIC5205")
      (footprint "eagle-import:SOT23-5")
      (libsource (lib "eagle-import") (part "V_REG_MIC52055V"))
    )
    (comp (ref "C1001")
      (value "0.1uF")
      (footprint "eagle-import:0603")
      (libsource (lib "eagle-import") (part "0.1UF-0603-25V-5%"))
    )
    (comp (ref "C1002")
      (value "2.2uF")
      (footprint "eagle-import:EIA3216")
      (libsource (lib "eagle-import") (part "10UF-POLAR-EIA3216-16V-10%(TANT)"))
    )
    (comp (ref "D1001")
      (value "SK310A-TP")
      (footprint "eagle-import:SMADIODE")
      (libsource (lib "eagle-import") (part "DIODESMA"))
    )
    (comp (ref "D1002")
      (value "GREEN")
      (footprint "eagle-import:LED-0603")
      (libsource (lib "eagle-import") (part "LED-GREEN0603"))
    )
    (comp (ref "D1003")
      (value "YELLOW")
      (footprint "eagle-import:LED-0603")
      (libsource (lib "eagle-import") (part "LED-YELLOW0603"))
    )
    (comp (ref "D1004")
      (value "RED")
      (footprint "eagle-import:LED-0603")
      (libsource (lib "eagle-import") (part "LED-RED0603"))
    )
    (comp (ref "J1001")
      (value "CONN_023.5MM_LOCK")
      (footprint "eagle-import:SCREWTERMINAL-3.5MM-2_LOCK")
      (libsource (lib "eagle-import") (part "CONN_023.5MM_LOCK"))
    )
    (comp (ref "J1002")
      (value "CONN_02LOCK")
      (footprint "eagle-import:1X02_LOCK")
      (libsource (lib "eagle-import") (part "CONN_02LOCK"))
    )
    (comp (ref "J1003")
      (value "CONN_02LOCK")
      (footprint "eagle-import:1X02_LOCK")
      (libsource (lib "eagle-import") (part "CONN_02LOCK"))
    )
    (comp (ref "J1004")
      (value "CONN_02LOCK")
      (footprint "eagle-import:1X02_LOCK")
      (libsource (lib "eagle-import") (part "CONN_02LOCK"))
    )
    (comp (ref "J1005")
      (value "ICSP_HEADER")
      (footprint "eagle-import:2X3")
      (libsource (lib "eagle-import") (part "AVR_SPI_PROG_3X2PTH"))
    )
    (comp (ref "Q1001")
      (value "PSMN7R0-60YS")
      (footprint "eagle-import:SOT669")
      (libsource (lib "eagle-import") (part "PSMN7R0-60YS"))
    )
    (comp (ref "R1001")
      (value "10R")
      (footprint "eagle-import:0603")
      (libsource (lib "eagle-import") (part "RESISTOR0603"))
    )
    (comp (ref "R1002")
      (value "100K")
      (footprint "eagle-import:0603")
      (libsource (lib "eagle-import") (part "RESISTOR0603"))
    )
    (comp (ref "R1003")
      (value "100K")
      (footprint "eagle-import:0603")
      (libsource (lib "eagle-import") (part "RESISTOR0603"))
    )
    (comp (ref "R1004")
      (value "1M")
      (footprint "eagle-import:0603")
      (libsource (lib "eagle-import") (part "RESISTOR0603"))
    )
    (comp (ref "R1005")
      (value "10K")
      (footprint "eagle-import:0603")
      (libsource (lib "eagle-import") (part "330OHM-0603-1/10W-1%"))
    )
    (comp (ref "R1006")
      (value "560r")
      (footprint "eagle-import:0603")
      (libsource (lib "eagle-import") (part "330OHM-0603-1/10W-1%"))
    )
    (comp (ref "R1007")
      (value "560r")
      (footprint "eagle-import:0603")
      (libsource (lib "eagle-import") (part "330OHM-0603-1/10W-1%"))
    )
    (comp (ref "R1008")
      (value "560r")
      (footprint "eagle-import:0603")
      (libsource (lib "eagle-import") (part "330OHM-0603-1/10W-1%"))
    )
    (comp (ref "S1001")
      (value "RST")
      (footprint "eagle-import:TACTILE_SWITCH_SMD_5.2MM")
      (libsource (lib "eagle-import") (part "MOMENTARY-SWITCH-SPST-SMD-5.2-REDUNDANT"))
    )
    (comp (ref "S1002")
      (value "SWITCH-SPDT-SMD-AYZ0202")
      (footprint "eagle-import:SWITCH_DPDT_SMD_AYZ0202")
      (libsource (lib "eagle-import") (part "SWITCH-SPDT-SMD-AYZ0202"))
    )
    (comp (ref "TP1001")
      (value "PTR1TP20R")
      (footprint "eagle-import:TP20R")
      (libsource (lib "eagle-import") (part "PTR1TP20R"))
    )
    (comp (ref "TP1002")
      (value "PTR1TP20R")
      (footprint "eagle-import:TP20R")
      (libsource (lib "eagle-import") (part "PTR1TP20R"))
    )
    (comp (ref "U1001")
      (value "ATTINY25-20SSUR")
      (footprint "eagle-import:SOIC8")
      (libsource (lib "eagle-import") (part "ATTINY45-SMT-NARROW"))
    )
    (comp (ref "U1002")
      (value "MIC5205")
      (footprint "eagle-import:SOT23-5")
      (libsource (lib "eagle-import") (part "V_REG_MIC52055V"))
    )
    (comp (ref "C1301")
      (value "0.1uF")
      (footprint "eagle-import:0603")
      (libsource (lib "eagle-import") (part "0.1UF-0603-25V-5%"))
    )
    (comp (ref "C1302")
      (value "0.33uF")
      (footprint "eagle-import:0603")
      (libsource (lib "eagle-import") (part "0.1UF-0603-25V-(+80/-20%)"))
    )
    (comp (ref "C1303")
      (value "0.1uF")
      (footprint "eagle-import:0603")
      (libsource (lib "eagle-import") (part "0.1UF-0603-25V-(+80/-20%)"))
    )
    (comp (ref "D1301")
      (value "GREEN")
      (footprint "eagle-import:LED-0603")
      (libsource (lib "eagle-import") (part "LED-GREEN0603"))
    )
    (comp (ref "D1302")
      (value "YELLOW")
      (footprint "eagle-import:LED-0603")
      (libsource (lib "eagle-import") (part "LED-YELLOW0603"))
    )
    (comp (ref "D1303")
      (value "RED")
      (footprint "eagle-import:LED-0603")
      (libsource (lib "eagle-import") (part "LED-RED0603"))
    )
    (comp (ref "IC1301")
      (value "7805DT")
      (footprint "eagle-import:TO252")
      (libsource (lib "eagle-import") (part "78DT05"))
    )
    (comp (ref "J1301")
      (value "CONN_02LOCK")
      (footprint "eagle-import:1X02_LOCK")
      (libsource (lib "eagle-import") (part "CONN_02LOCK"))
    )
    (comp (ref "J1302")
      (value "CONN_02LOCK")
      (footprint "eagle-import:1X02_LOCK")
      (libsource (lib "eagle-import") (part "CONN_02LOCK"))
    )
    (comp (ref "J1303")
      (value "CONN_02LOCK")
      (footprint "eagle-import:1X02_LOCK")
      (libsource (lib "eagle-import") (part "CONN_02LOCK"))
    )
    (comp (ref "J1304")
      (value "ICSP_HEADER")
      (footprint "eagle-import:2X3")
      (libsource (lib "eagle-import") (part "AVR_SPI_PROG_3X2PTH"))
    )
    (comp (ref "R1301")
      (value "10K")
      (footprint "eagle-import:0603")
      (libsource (lib "eagle-import") (part "RESISTOR0603"))
    )
    (comp (ref "R1302")
      (value "10K")
      (footprint "eagle-import:0603")
      (libsource (lib "eagle-import") (part "RESISTOR0603"))
    )
    (comp (ref "R1303")
      (value "10K")
      (footprint "eagle-import:0603")
      (libsource (lib "eagle-import") (part "330OHM-0603-1/10W-1%"))
    )
    (comp (ref "R1304")
      (value "560r")
      (footprint "eagle-import:0603")
      (libsource (lib "eagle-import") (part "330OHM-0603-1/10W-1%"))
    )
    (comp (ref "R1305")
      (value "560r")
      (footprint "eagle-import:0603")
      (libsource (lib "eagle-import") (part "330OHM-0603-1/10W-1%"))
    )
    (comp (ref "R1306")
      (value "560r")
      (footprint "eagle-import:0603")
      (libsource (lib "eagle-import") (part "330OHM-0603-1/10W-1%"))
    )
    (comp (ref "S1301")
      (value "RST")
      (footprint "eagle-import:TACTILE_SWITCH_SMD_5.2MM")
      (libsource (lib "eagle-import") (part "MOMENTARY-SWITCH-SPST-SMD-5.2-REDUNDANT"))
    )
    (comp (ref "S1302")
      (value "SWITCH-SPDT-SMD-AYZ0202")
      (footprint "eagle-import:SWITCH_DPDT_SMD_AYZ0202")
      (libsource (lib "eagle-import") (part "SWITCH-SPDT-SMD-AYZ0202"))
    )
    (comp (ref "TP1301")
      (value "PTR1TP20R")
      (footprint "eagle-import:TP20R")
      (libsource (lib "eagle-import") (part "PTR1TP20R"))
    )
    (comp (ref "TP1302")
      (value "PTR1TP20R")
      (footprint "eagle-import:TP20R")
      (libsource (lib "eagle-import") (part "PTR1TP20R"))
    )
    (comp (ref "U1301")
      (value "DRV8835")
      (footprint "eagle-import:WSON-12")
      (libsource (lib "eagle-import") (part "DRV883X"))
    )
    (comp (ref "U1302")
      (value "ATTINY25-20SSUR")
      (footprint "eagle-import:SOIC8")
      (libsource (lib "eagle-import") (part "ATTINY45-SMT-NARROW"))
    )
    (comp (ref "C1601")
      (value "100uF")
      (footprint "eagle-import:PANASONIC_D")
      (libsource (lib "eagle-import") (part "100UF-POLAR-25V-20%(ELEC)"))
    )
    (comp (ref "C1602")
      (value "100uF")
      (footprint "eagle-import:PANASONIC_D")
      (libsource (lib "eagle-import") (part "100UF-POLAR-25V-20%(ELEC)"))
    )
    (comp (ref "C1603")
      (value "100uF")
      (footprint "eagle-import:PANASONIC_D")
      (libsource (lib "eagle-import") (part "100UF-POLAR-25V-20%(ELEC)"))
    )
    (comp (ref "C1604")
      (value "0.1uF")
      (footprint "eagle-import:0603")
      (libsource (lib "eagle-import") (part "0.1UF-0603-25V-5%"))
    )
    (comp (ref "D1601")
      (value "SMAJ30A")
      (footprint "eagle-import:SMADIODE")
      (libsource (lib "eagle-import") (part "DIODESMA"))
    )
    (comp (ref "J1601")
      (value "CONN_02")
      (footprint "eagle-import:1X02")
      (libsource (lib "eagle-import") (part "CONN_02"))
    )
    (comp (ref "J1602")
      (value "CONN_02")
      (footprint "eagle-import:1X02")
      (libsource (lib "eagle-import") (part "CONN_02"))
    )
    (comp (ref "J1603")
      (value "CONN_02")
      (footprint "eagle-import:1X02")
      (libsource (lib "eagle-import") (part "CONN_02"))
    )
    (comp (ref "J1604")
      (value "CONN_02")
      (footprint "eagle-import:1X02")
      (libsource (lib "eagle-import") (part "CONN_02"))
    )
    (comp (ref "J1605")
      (value "CONN_02")
      (footprint "eagle-import:1X02")
      (libsource (lib "eagle-import") (part "CONN_02"))
    )
    (comp (ref "J1606")
      (value "CONN_02")
      (footprint "eagle-import:1X02")
      (libsource (lib "eagle-import") (part "CONN_02"))
    )
    (comp (ref "J1607")
      (value "CONN_02")
      (footprint "eagle-import:1X02")
      (libsource (lib "eagle-import") (part "CONN_02"))
    )
    (comp (ref "J1608")
      (value "CONN_02")
      (footprint "eagle-import:1X02")
      (libsource (lib "eagle-import") (part "CONN_02"))
    )
    (comp (ref "J1609")
      (value "CONN_02")
      (footprint "eagle-import:1X02")
      (libsource (lib "eagle-import") (part "CONN_02"))
    )
    (comp (ref "J1610")
      (value "CONN_02")
      (footprint "eagle-import:1X02")
      (libsource (lib "eagle-import") (part "CONN_02"))
    )
    (comp (ref "J1611")
      (value "CONN_02")
      (footprint "eagle-import:1X02")
      (libsource (lib "eagle-import") (part "CONN_02"))
    )
    (comp (ref "J1612")
      (value "CONN_02")
      (footprint "eagle-import:1X02")
      (libsource (lib "eagle-import") (part "CONN_02"))
    )
    (comp (ref "J1613")
      (value "CONN_02")
      (footprint "eagle-import:1X02")
      (libsource (lib "eagle-import") (part "CONN_02"))
    )
    (comp (ref "J1614")
      (value "CONN_02")
      (footprint "eagle-import:1X02")
      (libsource (lib "eagle-import") (part "CONN_02"))
    )
    (comp (ref "X1601")
      (value "MSTBA2")
      (footprint "eagle-import:MSTBA2")
      (fields (field (name "MF") "FARNELL") (field (name "MPN") "1757242"))
      (libsource (lib "eagle-import") (part "MSTBA2"))
    )
    (comp (ref "C1501")
      (value "0.33uF")
      (footprint "eagle-import:0603")
      (libsource (lib "eagle-import") (part "0.1UF-0603-25V-(+80/-20%)"))
    )
    (comp (ref "C1502")
      (value "0.1uF")
      (footprint "eagle-import:0603")
      (libsource (lib "eagle-import") (part "0.1UF-0603-25V-(+80/-20%)"))
    )
    (comp (ref "D1501")
      (value "YELLOW")
      (footprint "eagle-import:LED-0603")
      (libsource (lib "eagle-import") (part "LED-YELLOW0603"))
    )
    (comp (ref "D1502")
      (value "RED")
      (footprint "eagle-import:LED-0603")
      (libsource (lib "eagle-import") (part "LED-RED0603"))
    )
    (comp (ref "IC1501")
      (value "7805DT")
      (footprint "eagle-import:TO252")
      (libsource (lib "eagle-import") (part "78DT05"))
    )
    (comp (ref "J1501")
      (value "CONN_03LOCK")
      (footprint "eagle-import:1X03_LOCK")
      (libsource (lib "eagle-import") (part "CONN_03LOCK"))
    )
    (comp (ref "R1501")
      (value "10K")
      (footprint "eagle-import:0603")
      (libsource (lib "eagle-import") (part "RESISTOR0603"))
    )
    (comp (ref "R1502")
      (value "560r")
      (footprint "eagle-import:0603")
      (libsource (lib "eagle-import") (part "330OHM-0603-1/10W-1%"))
    )
    (comp (ref "R1503")
      (value "560r")
      (footprint "eagle-import:0603")
      (libsource (lib "eagle-import") (part "330OHM-0603-1/10W-1%"))
    )
    (comp (ref "TP1501")
      (value "PTR1TP20R")
      (footprint "eagle-import:TP20R")
      (libsource (lib "eagle-import") (part "PTR1TP20R"))
    )
    (comp (ref "C201")
      (value "0.1uF")
      (footprint "eagle-import:0603")
      (libsource (lib "eagle-import") (part "0.1UF-0603-25V-5%"))
    )
    (comp (ref "C202")
      (value "2.2uF")
      (footprint "eagle-import:EIA3216")
      (libsource (lib "eagle-import") (part "10UF-POLAR-EIA3216-16V-10%(TANT)"))
    )
    (comp (ref "D201")
      (value "SK310A-TP")
      (footprint "eagle-import:SMADIODE")
      (libsource (lib "eagle-import") (part "DIODESMA"))
    )
    (comp (ref "D202")
      (value "GREEN")
      (footprint "eagle-import:LED-0603")
      (libsource (lib "eagle-import") (part "LED-GREEN0603"))
    )
    (comp (ref "D203")
      (value "YELLOW")
      (footprint "eagle-import:LED-0603")
      (libsource (lib "eagle-import") (part "LED-YELLOW0603"))
    )
    (comp (ref "D204")
      (value "RED")
      (footprint "eagle-import:LED-0603")
      (libsource (lib "eagle-import") (part "LED-RED0603"))
    )
    (comp (ref "J201")
      (value "CONN_03LOCK")
      (footprint "eagle-import:1X03_LOCK")
      (libsource (lib "eagle-import") (part "CONN_03LOCK"))
    )
    (comp (ref "J202")
      (value "CONN_02LOCK")
      (footprint "eagle-import:1X02_LOCK")
      (libsource (lib "eagle-import") (part "CONN_02LOCK"))
    )
    (comp (ref "J203")
      (value "CONN_023.5MM_LOCK")
      (footprint "eagle-import:SCREWTERMINAL-3.5MM-2_LOCK")
      (libsource (lib "eagle-import") (part "CONN_023.5MM_LOCK"))
    )
    (comp (ref "J204")
      (value "ICSP_HEADER")
      (footprint "eagle-import:2X3")
      (libsource (lib "eagle-import") (part "AVR_SPI_PROG_3X2PTH"))
    )
    (comp (ref "JP201")
      (value "JUMPER-SMT_2_NO_SILK")
      (footprint "eagle-import:SMT-JUMPER_2_NO_SILK")
      (libsource (lib "eagle-import") (part "JUMPER-SMT_2_NO_SILK"))
    )
    (comp (ref "JP202")
      (value "JUMPER-SMT_2_NC_TRACE_SILK")
      (footprint "eagle-import:SMT-JUMPER_2_NC_TRACE_SILK")
      (libsource (lib "eagle-import") (part "JUMPER-SMT_2_NC_TRACE_SILK"))
    )
    (comp (ref "Q201")
      (value "PSMN7R0-60YS")
      (footprint "eagle-import:SOT669")
      (libsource (lib "eagle-import") (part "PSMN7R0-60YS"))
    )
    (comp (ref "R201")
      (value "10R")
      (footprint "eagle-import:0603")
      (libsource (lib "eagle-import") (part "RESISTOR0603"))
    )
    (comp (ref "R202")
      (value "100K")
      (footprint "eagle-import:0603")
      (libsource (lib "eagle-import") (part "RESISTOR0603"))
    )
    (comp (ref "R203")
      (value "10k")
      (footprint "eagle-import:0603")
      (libsource (lib "eagle-import") (part "RESISTOR0603"))
    )
    (comp (ref "R204")
      (value "10K")
      (footprint "eagle-import:0603")
      (libsource (lib "eagle-import") (part "330OHM-0603-1/10W-1%"))
    )
    (comp (ref "R205")
      (value "560r")
      (footprint "eagle-import:0603")
      (libsource (lib "eagle-import") (part "330OHM-0603-1/10W-1%"))
    )
    (comp (ref "R206")
      (value "560r")
      (footprint "eagle-import:0603")
      (libsource (lib "eagle-import") (part "330OHM-0603-1/10W-1%"))
    )
    (comp (ref "R207")
      (value "560r")
      (footprint "eagle-import:0603")
      (libsource (lib "eagle-import") (part "330OHM-0603-1/10W-1%"))
    )
    (comp (ref "S201")
      (value "RST")
      (footprint "eagle-import:TACTILE_SWITCH_SMD_5.2MM")
      (libsource (lib "eagle-import") (part "MOMENTARY-SWITCH-SPST-SMD-5.2-REDUNDANT"))
    )
    (comp (ref "S202")
      (value "SWITCH-SPDT-SMD-AYZ0202")
      (footprint "eagle-import:SWITCH_DPDT_SMD_AYZ0202")
      (libsource (lib "eagle-import") (part "SWITCH-SPDT-SMD-AYZ0202"))
    )
    (comp (ref "TP201")
      (value "PTR1TP20R")
      (footprint "eagle-import:TP20R")
      (libsource (lib "eagle-import") (part "PTR1TP20R"))
    )
    (comp (ref "TP202")
      (value "PTR1TP20R")
      (footprint "eagle-import:TP20R")
      (libsource (lib "eagle-import") (part "PTR1TP20R"))
    )
    (comp (ref "TP203")
      (value "PTR1TP20R")
      (footprint "eagle-import:TP20R")
      (libsource (lib "eagle-import") (part "PTR1TP20R"))
    )
    (comp (ref "U201")
      (value "74HC1G04")
      (footprint "eagle-import:SOT353")
      (libsource (lib "eagle-import") (part "741G04HC"))
    )
    (comp (ref "U202")
      (value "ATTINY25-20SSUR")
      (footprint "eagle-import:SOIC8")
      (libsource (lib "eagle-import") (part "ATTINY45-SMT-NARROW"))
    )
    (comp (ref "U203")
      (value "MIC5205")
      (footprint "eagle-import:SOT23-5")
      (libsource (lib "eagle-import") (part "V_REG_MIC52055V"))
    )
    (comp (ref "C1401")
      (value "2.2uF")
      (footprint "eagle-import:EIA3216")
      (libsource (lib "eagle-import") (part "10UF-POLAR-EIA3216-16V-10%(TANT)"))
    )
    (comp (ref "D1401")
      (value "SK310A-TP")
      (footprint "eagle-import:SMADIODE")
      (libsource (lib "eagle-import") (part "DIODESMA"))
    )
    (comp (ref "D1402")
      (value "GREEN")
      (footprint "eagle-import:LED-0603")
      (libsource (lib "eagle-import") (part "LED-GREEN0603"))
    )
    (comp (ref "D1403")
      (value "YELLOW")
      (footprint "eagle-import:LED-0603")
      (libsource (lib "eagle-import") (part "LED-YELLOW0603"))
    )
    (comp (ref "D1404")
      (value "RED")
      (footprint "eagle-import:LED-0603")
      (libsource (lib "eagle-import") (part "LED-RED0603"))
    )
    (comp (ref "J1401")
      (value "CONN_02LOCK")
      (footprint "eagle-import:1X02_LOCK")
      (libsource (lib "eagle-import") (part "CONN_02LOCK"))
    )
    (comp (ref "J1402")
      (value "CONN_023.5MM_LOCK")
      (footprint "eagle-import:SCREWTERMINAL-3.5MM-2_LOCK")
      (libsource (lib "eagle-import") (part "CONN_023.5MM_LOCK"))
    )
    (comp (ref "JP1401")
      (value "JUMPER-SMT_2_NO_SILK")
      (footprint "eagle-import:SMT-JUMPER_2_NO_SILK")
      (libsource (lib "eagle-import") (part "JUMPER-SMT_2_NO_SILK"))
    )
    (comp (ref "JP1402")
      (value "JUMPER-SMT_2_NC_TRACE_SILK")
      (footprint "eagle-import:SMT-JUMPER_2_NC_TRACE_SILK")
      (libsource (lib "eagle-import") (part "JUMPER-SMT_2_NC_TRACE_SILK"))
    )
    (comp (ref "Q1401")
      (value "PSMN7R0-60YS")
      (footprint "eagle-import:SOT669")
      (libsource (lib "eagle-import") (part "PSMN7R0-60YS"))
    )
    (comp (ref "R1401")
      (value "10K")
      (footprint "eagle-import:0603")
      (libsource (lib "eagle-import") (part "RESISTOR0603"))
    )
    (comp (ref "R1402")
      (value "10R")
      (footprint "eagle-import:0603")
      (libsource (lib "eagle-import") (part "RESISTOR0603"))
    )
    (comp (ref "R1403")
      (value "100K")
      (footprint "eagle-import:0603")
      (libsource (lib "eagle-import") (part "RESISTOR0603"))
    )
    (comp (ref "R1404")
      (value "560r")
      (footprint "eagle-import:0603")
      (libsource (lib "eagle-import") (part "330OHM-0603-1/10W-1%"))
    )
    (comp (ref "R1405")
      (value "560r")
      (footprint "eagle-import:0603")
      (libsource (lib "eagle-import") (part "330OHM-0603-1/10W-1%"))
    )
    (comp (ref "R1406")
      (value "560r")
      (footprint "eagle-import:0603")
      (libsource (lib "eagle-import") (part "330OHM-0603-1/10W-1%"))
    )
    (comp (ref "S1401")
      (value "SWITCH-SPDT-SMD-AYZ0202")
      (footprint "eagle-import:SWITCH_DPDT_SMD_AYZ0202")
      (libsource (lib "eagle-import") (part "SWITCH-SPDT-SMD-AYZ0202"))
    )
    (comp (ref "TP1401")
      (value "PTR1TP20R")
      (footprint "eagle-import:TP20R")
      (libsource (lib "eagle-import") (part "PTR1TP20R"))
    )
    (comp (ref "TP1402")
      (value "PTR1TP20R")
      (footprint "eagle-import:TP20R")
      (libsource (lib "eagle-import") (part "PTR1TP20R"))
    )
    (comp (ref "U1401")
      (value "74HC1G04")
      (footprint "eagle-import:SOT353")
      (libsource (lib "eagle-import") (part "741G04HC"))
    )
    (comp (ref "U1402")
      (value "MIC5205")
      (footprint "eagle-import:SOT23-5")
      (libsource (lib "eagle-import") (part "V_REG_MIC52055V"))
    )
    (comp (ref "C601")
      (value "0.1uF")
      (footprint "eagle-import:0603")
      (libsource (lib "eagle-import") (part "0.1UF-0603-25V-5%"))
    )
    (comp (ref "C602")
      (value "2.2uF")
      (footprint "eagle-import:EIA3216")
      (libsource (lib "eagle-import") (part "10UF-POLAR-EIA3216-16V-10%(TANT)"))
    )
    (comp (ref "D601")
      (value "SK310A-TP")
      (footprint "eagle-import:SMADIODE")
      (libsource (lib "eagle-import") (part "DIODESMA"))
    )
    (comp (ref "D602")
      (value "GREEN")
      (footprint "eagle-import:LED-0603")
      (libsource (lib "eagle-import") (part "LED-GREEN0603"))
    )
    (comp (ref "D603")
      (value "YELLOW")
      (footprint "eagle-import:LED-0603")
      (libsource (lib "eagle-import") (part "LED-YELLOW0603"))
    )
    (comp (ref "D604")
      (value "RED")
      (footprint "eagle-import:LED-0603")
      (libsource (lib "eagle-import") (part "LED-RED0603"))
    )
    (comp (ref "J601")
      (value "CONN_02LOCK")
      (footprint "eagle-import:1X02_LOCK")
      (libsource (lib "eagle-import") (part "CONN_02LOCK"))
    )
    (comp (ref "J602")
      (value "CONN_023.5MM_LOCK")
      (footprint "eagle-import:SCREWTERMINAL-3.5MM-2_LOCK")
      (libsource (lib "eagle-import") (part "CONN_023.5MM_LOCK"))
    )
    (comp (ref "J603")
      (value "ICSP_HEADER")
      (footprint "eagle-import:2X3")
      (libsource (lib "eagle-import") (part "AVR_SPI_PROG_3X2PTH"))
    )
    (comp (ref "Q601")
      (value "PSMN7R0-60YS")
      (footprint "eagle-import:SOT669")
      (libsource (lib "eagle-import") (part "PSMN7R0-60YS"))
    )
    (comp (ref "R601")
      (value "10R")
      (footprint "eagle-import:0603")
      (libsource (lib "eagle-import") (part "RESISTOR0603"))
    )
    (comp (ref "R602")
      (value "100K")
      (footprint "eagle-import:0603")
      (libsource (lib "eagle-import") (part "RESISTOR0603"))
    )
    (comp (ref "R603")
      (value "1M")
      (footprint "eagle-import:0603")
      (libsource (lib "eagle-import") (part "RESISTOR0603"))
    )
    (comp (ref "R604")
      (value "10K")
      (footprint "eagle-import:0603")
      (libsource (lib "eagle-import") (part "330OHM-0603-1/10W-1%"))
    )
    (comp (ref "R605")
      (value "560r")
      (footprint "eagle-import:0603")
      (libsource (lib "eagle-import") (part "330OHM-0603-1/10W-1%"))
    )
    (comp (ref "R606")
      (value "560r")
      (footprint "eagle-import:0603")
      (libsource (lib "eagle-import") (part "330OHM-0603-1/10W-1%"))
    )
    (comp (ref "R607")
      (value "560r")
      (footprint "eagle-import:0603")
      (libsource (lib "eagle-import") (part "330OHM-0603-1/10W-1%"))
    )
    (comp (ref "S601")
      (value "RST")
      (footprint "eagle-import:TACTILE_SWITCH_SMD_5.2MM")
      (libsource (lib "eagle-import") (part "MOMENTARY-SWITCH-SPST-SMD-5.2-REDUNDANT"))
    )
    (comp (ref "S602")
      (value "SWITCH-SPDT-SMD-AYZ0202")
      (footprint "eagle-import:SWITCH_DPDT_SMD_AYZ0202")
      (libsource (lib "eagle-import") (part "SWITCH-SPDT-SMD-AYZ0202"))
    )
    (comp (ref "TP601")
      (value "PTR1TP20R")
      (footprint "eagle-import:TP20R")
      (libsource (lib "eagle-import") (part "PTR1TP20R"))
    )
    (comp (ref "TP602")
      (value "PTR1TP20R")
      (footprint "eagle-import:TP20R")
      (libsource (lib "eagle-import") (part "PTR1TP20R"))
    )
    (comp (ref "TP603")
      (value "PTR1TP20R")
      (footprint "eagle-import:TP20R")
      (libsource (lib "eagle-import") (part "PTR1TP20R"))
    )
    (comp (ref "TP604")
      (value "PTR1TP20R")
      (footprint "eagle-import:TP20R")
      (libsource (lib "eagle-import") (part "PTR1TP20R"))
    )
    (comp (ref "U601")
      (value "74HC1G04")
      (footprint "eagle-import:SOT353")
      (libsource (lib "eagle-import") (part "741G04HC"))
    )
    (comp (ref "U602")
      (value "SN74C1G08-DCK")
      (footprint "eagle-import:SC-70-5")
      (libsource (lib "eagle-import") (part "SN74C1G08-DCK"))
    )
    (comp (ref "U603")
      (value "ATTINY25-20SSUR")
      (footprint "eagle-import:SOIC8")
      (libsource (lib "eagle-import") (part "ATTINY45-SMT-NARROW"))
    )
    (comp (ref "U604")
      (value "MIC5205")
      (footprint "eagle-import:SOT23-5")
      (libsource (lib "eagle-import") (part "V_REG_MIC52055V"))
    )
    (comp (ref "C1101")
      (value "0.1uF")
      (footprint "eagle-import:0603")
      (libsource (lib "eagle-import") (part "0.1UF-0603-25V-5%"))
    )
    (comp (ref "C1102")
      (value "0.33uF")
      (footprint "eagle-import:0603")
      (libsource (lib "eagle-import") (part "0.1UF-0603-25V-(+80/-20%)"))
    )
    (comp (ref "C1103")
      (value "0.1uF")
      (footprint "eagle-import:0603")
      (libsource (lib "eagle-import") (part "0.1UF-0603-100V-10%"))
    )
    (comp (ref "D1101")
      (value "GREEN")
      (footprint "eagle-import:LED-0603")
      (libsource (lib "eagle-import") (part "LED-GREEN0603"))
    )
    (comp (ref "D1102")
      (value "YELLOW")
      (footprint "eagle-import:LED-0603")
      (libsource (lib "eagle-import") (part "LED-YELLOW0603"))
    )
    (comp (ref "D1103")
      (value "RED")
      (footprint "eagle-import:LED-0603")
      (libsource (lib "eagle-import") (part "LED-RED0603"))
    )
    (comp (ref "IC1101")
      (value "7805DT")
      (footprint "eagle-import:TO252")
      (libsource (lib "eagle-import") (part "78DT05"))
    )
    (comp (ref "J1101")
      (value "CONN_02LOCK")
      (footprint "eagle-import:1X02_LOCK")
      (libsource (lib "eagle-import") (part "CONN_02LOCK"))
    )
    (comp (ref "J1102")
      (value "CONN_02LOCK")
      (footprint "eagle-import:1X02_LOCK")
      (libsource (lib "eagle-import") (part "CONN_02LOCK"))
    )
    (comp (ref "J1103")
      (value "CONN_02LOCK")
      (footprint "eagle-import:1X02_LOCK")
      (libsource (lib "eagle-import") (part "CONN_02LOCK"))
    )
    (comp (ref "J1104")
      (value "ICSP_HEADER")
      (footprint "eagle-import:2X3")
      (libsource (lib "eagle-import") (part "AVR_SPI_PROG_3X2PTH"))
    )
    (comp (ref "R1101")
      (value "10K")
      (footprint "eagle-import:0603")
      (libsource (lib "eagle-import") (part "RESISTOR0603"))
    )
    (comp (ref "R1102")
      (value "10K")
      (footprint "eagle-import:0603")
      (libsource (lib "eagle-import") (part "RESISTOR0603"))
    )
    (comp (ref "R1103")
      (value "10K")
      (footprint "eagle-import:0603")
      (libsource (lib "eagle-import") (part "330OHM-0603-1/10W-1%"))
    )
    (comp (ref "R1104")
      (value "560r")
      (footprint "eagle-import:0603")
      (libsource (lib "eagle-import") (part "330OHM-0603-1/10W-1%"))
    )
    (comp (ref "R1105")
      (value "560r")
      (footprint "eagle-import:0603")
      (libsource (lib "eagle-import") (part "330OHM-0603-1/10W-1%"))
    )
    (comp (ref "R1106")
      (value "560r")
      (footprint "eagle-import:0603")
      (libsource (lib "eagle-import") (part "330OHM-0603-1/10W-1%"))
    )
    (comp (ref "S1101")
      (value "RST")
      (footprint "eagle-import:TACTILE_SWITCH_SMD_5.2MM")
      (libsource (lib "eagle-import") (part "MOMENTARY-SWITCH-SPST-SMD-5.2-REDUNDANT"))
    )
    (comp (ref "S1102")
      (value "SWITCH-SPDT-SMD-AYZ0202")
      (footprint "eagle-import:SWITCH_DPDT_SMD_AYZ0202")
      (libsource (lib "eagle-import") (part "SWITCH-SPDT-SMD-AYZ0202"))
    )
    (comp (ref "TP1101")
      (value "PTR1TP20R")
      (footprint "eagle-import:TP20R")
      (libsource (lib "eagle-import") (part "PTR1TP20R"))
    )
    (comp (ref "TP1102")
      (value "PTR1TP20R")
      (footprint "eagle-import:TP20R")
      (libsource (lib "eagle-import") (part "PTR1TP20R"))
    )
    (comp (ref "U1101")
      (value "DRV8835")
      (footprint "eagle-import:WSON-12")
      (libsource (lib "eagle-import") (part "DRV883X"))
    )
    (comp (ref "U1102")
      (value "ATTINY25-20SSUR")
      (footprint "eagle-import:SOIC8")
      (libsource (lib "eagle-import") (part "ATTINY45-SMT-NARROW"))
    )
    (comp (ref "C301")
      (value "0.1uF")
      (footprint "eagle-import:0603")
      (libsource (lib "eagle-import") (part "0.1UF-0603-25V-5%"))
    )
    (comp (ref "C302")
      (value "2.2uF")
      (footprint "eagle-import:EIA3216")
      (libsource (lib "eagle-import") (part "10UF-POLAR-EIA3216-16V-10%(TANT)"))
    )
    (comp (ref "D301")
      (value "INCANDESCENT")
      (footprint "eagle-import:LED_3MM")
      (libsource (lib "eagle-import") (part "LED3MM"))
    )
    (comp (ref "D302")
      (value "GREEN")
      (footprint "eagle-import:LED-0603")
      (libsource (lib "eagle-import") (part "LED-GREEN0603"))
    )
    (comp (ref "D303")
      (value "YELLOW")
      (footprint "eagle-import:LED-0603")
      (libsource (lib "eagle-import") (part "LED-YELLOW0603"))
    )
    (comp (ref "D304")
      (value "RED")
      (footprint "eagle-import:LED-0603")
      (libsource (lib "eagle-import") (part "LED-RED0603"))
    )
    (comp (ref "J301")
      (value "ICSP_HEADER")
      (footprint "eagle-import:2X3")
      (libsource (lib "eagle-import") (part "AVR_SPI_PROG_3X2PTH"))
    )
    (comp (ref "Q301")
      (value "500mA/300V")
      (footprint "eagle-import:SOT23-3")
      (libsource (lib "eagle-import") (part "TRANS_NPN-MMBTA42"))
    )
    (comp (ref "R301")
      (value "10K")
      (footprint "eagle-import:0603")
      (libsource (lib "eagle-import") (part "RESISTOR0603"))
    )
    (comp (ref "R302")
      (value "1K")
      (footprint "eagle-import:0603")
      (libsource (lib "eagle-import") (part "RESISTOR0603"))
    )
    (comp (ref "R303")
      (value "PHOTOCELLPTH")
      (footprint "eagle-import:PHOTOCELL")
      (libsource (lib "eagle-import") (part "PHOTOCELLPTH"))
    )
    (comp (ref "R304")
      (value "10K")
      (footprint "eagle-import:0603")
      (libsource (lib "eagle-import") (part "330OHM-0603-1/10W-1%"))
    )
    (comp (ref "R305")
      (value "560r")
      (footprint "eagle-import:0603")
      (libsource (lib "eagle-import") (part "330OHM-0603-1/10W-1%"))
    )
    (comp (ref "R306")
      (value "560r")
      (footprint "eagle-import:0603")
      (libsource (lib "eagle-import") (part "330OHM-0603-1/10W-1%"))
    )
    (comp (ref "R307")
      (value "560r")
      (footprint "eagle-import:0603")
      (libsource (lib "eagle-import") (part "330OHM-0603-1/10W-1%"))
    )
    (comp (ref "S301")
      (value "RST")
      (footprint "eagle-import:TACTILE_SWITCH_SMD_5.2MM")
      (libsource (lib "eagle-import") (part "MOMENTARY-SWITCH-SPST-SMD-5.2-REDUNDANT"))
    )
    (comp (ref "S302")
      (value "SWITCH-SPDT-SMD-AYZ0202")
      (footprint "eagle-import:SWITCH_DPDT_SMD_AYZ0202")
      (libsource (lib "eagle-import") (part "SWITCH-SPDT-SMD-AYZ0202"))
    )
    (comp (ref "TP301")
      (value "PTR1TP20R")
      (footprint "eagle-import:TP20R")
      (libsource (lib "eagle-import") (part "PTR1TP20R"))
    )
    (comp (ref "TP302")
      (value "PTR1TP20R")
      (footprint "eagle-import:TP20R")
      (libsource (lib "eagle-import") (part "PTR1TP20R"))
    )
    (comp (ref "TP303")
      (value "PTR1TP20R")
      (footprint "eagle-import:TP20R")
      (libsource (lib "eagle-import") (part "PTR1TP20R"))
    )
    (comp (ref "U301")
      (value "74HC1G04")
      (footprint "eagle-import:SOT353")
      (libsource (lib "eagle-import") (part "741G04HC"))
    )
    (comp (ref "U302")
      (value "SN74C1G08-DCK")
      (footprint "eagle-import:SC-70-5")
      (libsource (lib "eagle-import") (part "SN74C1G08-DCK"))
    )
    (comp (ref "U303")
      (value "ATTINY25-20SSUR")
      (footprint "eagle-import:SOIC8")
      (libsource (lib "eagle-import") (part "ATTINY45-SMT-NARROW"))
    )
    (comp (ref "U304")
      (value "MIC5205")
      (footprint "eagle-import:SOT23-5")
      (libsource (lib "eagle-import") (part "V_REG_MIC52055V"))
    )
    (comp (ref "C701")
      (value "0.1uF")
      (footprint "eagle-import:0603")
      (libsource (lib "eagle-import") (part "0.1UF-0603-25V-5%"))
    )
    (comp (ref "C702")
      (value "0.1uF")
      (footprint "eagle-import:0603")
      (libsource (lib "eagle-import") (part "0.1UF-0603-25V-5%"))
    )
    (comp (ref "C703")
      (value "2.2uF")
      (footprint "eagle-import:EIA3216")
      (libsource (lib "eagle-import") (part "10UF-POLAR-EIA3216-16V-10%(TANT)"))
    )
    (comp (ref "D701")
      (value "GREEN")
      (footprint "eagle-import:LED-0603")
      (libsource (lib "eagle-import") (part "LED-GREEN0603"))
    )
    (comp (ref "D702")
      (value "YELLOW")
      (footprint "eagle-import:LED-0603")
      (libsource (lib "eagle-import") (part "LED-YELLOW0603"))
    )
    (comp (ref "D703")
      (value "RED")
      (footprint "eagle-import:LED-0603")
      (libsource (lib "eagle-import") (part "LED-RED0603"))
    )
    (comp (ref "J701")
      (value "CONN_03")
      (footprint "eagle-import:1X03")
      (libsource (lib "eagle-import") (part "CONN_03"))
    )
    (comp (ref "J702")
      (value "CONN_02LOCK")
      (footprint "eagle-import:1X02_LOCK")
      (libsource (lib "eagle-import") (part "CONN_02LOCK"))
    )
    (comp (ref "J703")
      (value "ICSP_HEADER")
      (footprint "eagle-import:2X3")
      (libsource (lib "eagle-import") (part "AVR_SPI_PROG_3X2PTH"))
    )
    (comp (ref "J704")
      (value "ICSP_HEADER")
      (footprint "eagle-import:2X3")
      (libsource (lib "eagle-import") (part "AVR_SPI_PROG_3X2PTH"))
    )
    (comp (ref "R701")
      (value "330r")
      (footprint "eagle-import:0603")
      (libsource (lib "eagle-import") (part "RESISTOR0603"))
    )
    (comp (ref "R702")
      (value "33k")
      (footprint "eagle-import:0603")
      (libsource (lib "eagle-import") (part "RESISTOR0603"))
    )
    (comp (ref "R703")
      (value "10K")
      (footprint "eagle-import:0603")
      (libsource (lib "eagle-import") (part "330OHM-0603-1/10W-1%"))
    )
    (comp (ref "R704")
      (value "10K")
      (footprint "eagle-import:0603")
      (libsource (lib "eagle-import") (part "330OHM-0603-1/10W-1%"))
    )
    (comp (ref "R705")
      (value "560r")
      (footprint "eagle-import:0603")
      (libsource (lib "eagle-import") (part "330OHM-0603-1/10W-1%"))
    )
    (comp (ref "R706")
      (value "560r")
      (footprint "eagle-import:0603")
      (libsource (lib "eagle-import") (part "330OHM-0603-1/10W-1%"))
    )
    (comp (ref "R707")
      (value "560r")
      (footprint "eagle-import:0603")
      (libsource (lib "eagle-import") (part "330OHM-0603-1/10W-1%"))
    )
    (comp (ref "S701")
      (value "RST")
      (footprint "eagle-import:TACTILE_SWITCH_SMD_5.2MM")
      (libsource (lib "eagle-import") (part "MOMENTARY-SWITCH-SPST-SMD-5.2-REDUNDANT"))
    )
    (comp (ref "S702")
      (value "RST")
      (footprint "eagle-import:TACTILE_SWITCH_SMD_5.2MM")
      (libsource (lib "eagle-import") (part "MOMENTARY-SWITCH-SPST-SMD-5.2-REDUNDANT"))
    )
    (comp (ref "S703")
      (value "SWITCH-SPDT-SMD-AYZ0202")
      (footprint "eagle-import:SWITCH_DPDT_SMD_AYZ0202")
      (libsource (lib "eagle-import") (part "SWITCH-SPDT-SMD-AYZ0202"))
    )
    (comp (ref "TP701")
      (value "PTR1TP20R")
      (footprint "eagle-import:TP20R")
      (libsource (lib "eagle-import") (part "PTR1TP20R"))
    )
    (comp (ref "TP702")
      (value "PTR1TP20R")
      (footprint "eagle-import:TP20R")
      (libsource (lib "eagle-import") (part "PTR1TP20R"))
    )
    (comp (ref "TP703")
      (value "PTR1TP20R")
      (footprint "eagle-import:TP20R")
      (libsource (lib "eagle-import") (part "PTR1TP20R"))
    )
    (comp (ref "U701")
      (value "ATTINY25-20SSUR")
      (footprint "eagle-import:SOIC8")
      (libsource (lib "eagle-import") (part "ATTINY45-SMT-NARROW"))
    )
    (comp (ref "U702")
      (value "ATTINY25-20SSUR")
      (footprint "eagle-import:SOIC8")
      (libsource (lib "eagle-import") (part "ATTINY45-SMT-NARROW"))
    )
    (comp (ref "U703")
      (value "MIC5205")
      (footprint "eagle-import:SOT23-5")
      (libsource (lib "eagle-import") (part "V_REG_MIC52055V"))
    )
    (comp (ref "C401")
      (value "0.1uF")
      (footprint "eagle-import:0603")
      (libsource (lib "eagle-import") (part "0.1UF-0603-25V-5%"))
    )
    (comp (ref "C402")
      (value "2.2uF")
      (footprint "eagle-import:EIA3216")
      (libsource (lib "eagle-import") (part "10UF-POLAR-EIA3216-16V-10%(TANT)"))
    )
    (comp (ref "D401")
      (value "WHITE")
      (footprint "eagle-import:LED_3MM")
      (libsource (lib "eagle-import") (part "LED3MM"))
    )
    (comp (ref "D402")
      (value "GREEN")
      (footprint "eagle-import:LED-0603")
      (libsource (lib "eagle-import") (part "LED-GREEN0603"))
    )
    (comp (ref "D403")
      (value "YELLOW")
      (footprint "eagle-import:LED-0603")
      (libsource (lib "eagle-import") (part "LED-YELLOW0603"))
    )
    (comp (ref "D404")
      (value "RED")
      (footprint "eagle-import:LED-0603")
      (libsource (lib "eagle-import") (part "LED-RED0603"))
    )
    (comp (ref "J401")
      (value "ICSP_HEADER")
      (footprint "eagle-import:2X3")
      (libsource (lib "eagle-import") (part "AVR_SPI_PROG_3X2PTH"))
    )
    (comp (ref "Q401")
      (value "500mA/300V")
      (footprint "eagle-import:SOT23-3")
      (libsource (lib "eagle-import") (part "TRANS_NPN-MMBTA42"))
    )
    (comp (ref "R401")
      (value "10K")
      (footprint "eagle-import:0603")
      (libsource (lib "eagle-import") (part "RESISTOR0603"))
    )
    (comp (ref "R402")
      (value "PHOTOCELLPTH")
      (footprint "eagle-import:PHOTOCELL")
      (libsource (lib "eagle-import") (part "PHOTOCELLPTH"))
    )
    (comp (ref "R403")
      (value "1K")
      (footprint "eagle-import:0603")
      (libsource (lib "eagle-import") (part "RESISTOR0603"))
    )
    (comp (ref "R404")
      (value "560")
      (footprint "eagle-import:0603")
      (libsource (lib "eagle-import") (part "RESISTOR0603"))
    )
    (comp (ref "R405")
      (value "10K")
      (footprint "eagle-import:0603")
      (libsource (lib "eagle-import") (part "330OHM-0603-1/10W-1%"))
    )
    (comp (ref "R406")
      (value "560r")
      (footprint "eagle-import:0603")
      (libsource (lib "eagle-import") (part "330OHM-0603-1/10W-1%"))
    )
    (comp (ref "R407")
      (value "560r")
      (footprint "eagle-import:0603")
      (libsource (lib "eagle-import") (part "330OHM-0603-1/10W-1%"))
    )
    (comp (ref "R408")
      (value "560r")
      (footprint "eagle-import:0603")
      (libsource (lib "eagle-import") (part "330OHM-0603-1/10W-1%"))
    )
    (comp (ref "S401")
      (value "RST")
      (footprint "eagle-import:TACTILE_SWITCH_SMD_5.2MM")
      (libsource (lib "eagle-import") (part "MOMENTARY-SWITCH-SPST-SMD-5.2-REDUNDANT"))
    )
    (comp (ref "S402")
      (value "SWITCH-SPDT-SMD-AYZ0202")
      (footprint "eagle-import:SWITCH_DPDT_SMD_AYZ0202")
      (libsource (lib "eagle-import") (part "SWITCH-SPDT-SMD-AYZ0202"))
    )
    (comp (ref "TP401")
      (value "PTR1TP20R")
      (footprint "eagle-import:TP20R")
      (libsource (lib "eagle-import") (part "PTR1TP20R"))
    )
    (comp (ref "TP402")
      (value "PTR1TP20R")
      (footprint "eagle-import:TP20R")
      (libsource (lib "eagle-import") (part "PTR1TP20R"))
    )
    (comp (ref "TP403")
      (value "PTR1TP20R")
      (footprint "eagle-import:TP20R")
      (libsource (lib "eagle-import") (part "PTR1TP20R"))
    )
    (comp (ref "TP404")
      (value "PTR1TP20R")
      (footprint "eagle-import:TP20R")
      (libsource (lib "eagle-import") (part "PTR1TP20R"))
    )
    (comp (ref "U401")
      (value "74HC1G04")
      (footprint "eagle-import:SOT353")
      (libsource (lib "eagle-import") (part "741G04HC"))
    )
    (comp (ref "U402")
      (value "SN74C1G08-DCK")
      (footprint "eagle-import:SC-70-5")
      (libsource (lib "eagle-import") (part "SN74C1G08-DCK"))
    )
    (comp (ref "U403")
      (value "ATTINY25-20SSUR")
      (footprint "eagle-import:SOIC8")
      (libsource (lib "eagle-import") (part "ATTINY45-SMT-NARROW"))
    )
    (comp (ref "U404")
      (value "MIC5205")
      (footprint "eagle-import:SOT23-5")
      (libsource (lib "eagle-import") (part "V_REG_MIC52055V"))
    )
    (comp (ref "C1201")
      (value "0.1uF")
      (footprint "eagle-import:0603")
      (libsource (lib "eagle-import") (part "0.1UF-0603-25V-5%"))
    )
    (comp (ref "C1202")
      (value "0.33uF")
      (footprint "eagle-import:0603")
      (libsource (lib "eagle-import") (part "0.1UF-0603-25V-(+80/-20%)"))
    )
    (comp (ref "C1203")
      (value "0.1uF")
      (footprint "eagle-import:0603")
      (libsource (lib "eagle-import") (part "0.1UF-0603-25V-(+80/-20%)"))
    )
    (comp (ref "D1201")
      (value "GREEN")
      (footprint "eagle-import:LED-0603")
      (libsource (lib "eagle-import") (part "LED-GREEN0603"))
    )
    (comp (ref "D1202")
      (value "YELLOW")
      (footprint "eagle-import:LED-0603")
      (libsource (lib "eagle-import") (part "LED-YELLOW0603"))
    )
    (comp (ref "D1203")
      (value "RED")
      (footprint "eagle-import:LED-0603")
      (libsource (lib "eagle-import") (part "LED-RED0603"))
    )
    (comp (ref "IC1201")
      (value "7805DT")
      (footprint "eagle-import:TO252")
      (libsource (lib "eagle-import") (part "78DT05"))
    )
    (comp (ref "J1201")
      (value "CONN_02LOCK")
      (footprint "eagle-import:1X02_LOCK")
      (libsource (lib "eagle-import") (part "CONN_02LOCK"))
    )
    (comp (ref "J1202")
      (value "CONN_02LOCK")
      (footprint "eagle-import:1X02_LOCK")
      (libsource (lib "eagle-import") (part "CONN_02LOCK"))
    )
    (comp (ref "J1203")
      (value "CONN_02LOCK")
      (footprint "eagle-import:1X02_LOCK")
      (libsource (lib "eagle-import") (part "CONN_02LOCK"))
    )
    (comp (ref "J1204")
      (value "ICSP_HEADER")
      (footprint "eagle-import:2X3")
      (libsource (lib "eagle-import") (part "AVR_SPI_PROG_3X2PTH"))
    )
    (comp (ref "R1201")
      (value "10K")
      (footprint "eagle-import:0603")
      (libsource (lib "eagle-import") (part "RESISTOR0603"))
    )
    (comp (ref "R1202")
      (value "10K")
      (footprint "eagle-import:0603")
      (libsource (lib "eagle-import") (part "RESISTOR0603"))
    )
    (comp (ref "R1203")
      (value "10K")
      (footprint "eagle-import:0603")
      (libsource (lib "eagle-import") (part "330OHM-0603-1/10W-1%"))
    )
    (comp (ref "R1204")
      (value "560r")
      (footprint "eagle-import:0603")
      (libsource (lib "eagle-import") (part "330OHM-0603-1/10W-1%"))
    )
    (comp (ref "R1205")
      (value "560r")
      (footprint "eagle-import:0603")
      (libsource (lib "eagle-import") (part "330OHM-0603-1/10W-1%"))
    )
    (comp (ref "R1206")
      (value "560r")
      (footprint "eagle-import:0603")
      (libsource (lib "eagle-import") (part "330OHM-0603-1/10W-1%"))
    )
    (comp (ref "S1201")
      (value "RST")
      (footprint "eagle-import:TACTILE_SWITCH_SMD_5.2MM")
      (libsource (lib "eagle-import") (part "MOMENTARY-SWITCH-SPST-SMD-5.2-REDUNDANT"))
    )
    (comp (ref "S1202")
      (value "SWITCH-SPDT-SMD-AYZ0202")
      (footprint "eagle-import:SWITCH_DPDT_SMD_AYZ0202")
      (libsource (lib "eagle-import") (part "SWITCH-SPDT-SMD-AYZ0202"))
    )
    (comp (ref "TP1201")
      (value "PTR1TP20R")
      (footprint "eagle-import:TP20R")
      (libsource (lib "eagle-import") (part "PTR1TP20R"))
    )
    (comp (ref "TP1202")
      (value "PTR1TP20R")
      (footprint "eagle-import:TP20R")
      (libsource (lib "eagle-import") (part "PTR1TP20R"))
    )
    (comp (ref "U1201")
      (value "DRV8835")
      (footprint "eagle-import:WSON-12")
      (libsource (lib "eagle-import") (part "DRV883X"))
    )
    (comp (ref "U1202")
      (value "ATTINY25-20SSUR")
      (footprint "eagle-import:SOIC8")
      (libsource (lib "eagle-import") (part "ATTINY45-SMT-NARROW"))
    )
    (comp (ref "C501")
      (value "0.1uF")
      (footprint "eagle-import:0603")
      (libsource (lib "eagle-import") (part "0.1UF-0603-25V-5%"))
    )
    (comp (ref "C502")
      (value "2.2uF")
      (footprint "eagle-import:EIA3216")
      (libsource (lib "eagle-import") (part "10UF-POLAR-EIA3216-16V-10%(TANT)"))
    )
    (comp (ref "D501")
      (value "SK310A-TP")
      (footprint "eagle-import:SMADIODE")
      (libsource (lib "eagle-import") (part "DIODESMA"))
    )
    (comp (ref "D502")
      (value "GREEN")
      (footprint "eagle-import:LED-0603")
      (libsource (lib "eagle-import") (part "LED-GREEN0603"))
    )
    (comp (ref "D503")
      (value "YELLOW")
      (footprint "eagle-import:LED-0603")
      (libsource (lib "eagle-import") (part "LED-YELLOW0603"))
    )
    (comp (ref "D504")
      (value "RED")
      (footprint "eagle-import:LED-0603")
      (libsource (lib "eagle-import") (part "LED-RED0603"))
    )
    (comp (ref "J501")
      (value "CONN_02LOCK")
      (footprint "eagle-import:1X02_LOCK")
      (libsource (lib "eagle-import") (part "CONN_02LOCK"))
    )
    (comp (ref "J502")
      (value "CONN_023.5MM_LOCK")
      (footprint "eagle-import:SCREWTERMINAL-3.5MM-2_LOCK")
      (libsource (lib "eagle-import") (part "CONN_023.5MM_LOCK"))
    )
    (comp (ref "J503")
      (value "ICSP_HEADER")
      (footprint "eagle-import:2X3")
      (libsource (lib "eagle-import") (part "AVR_SPI_PROG_3X2PTH"))
    )
    (comp (ref "Q501")
      (value "PSMN7R0-60YS")
      (footprint "eagle-import:SOT669")
      (libsource (lib "eagle-import") (part "PSMN7R0-60YS"))
    )
    (comp (ref "R501")
      (value "0R")
      (footprint "eagle-import:0603")
      (libsource (lib "eagle-import") (part "RESISTOR0603"))
    )
    (comp (ref "R502")
      (value "10R")
      (footprint "eagle-import:0603")
      (libsource (lib "eagle-import") (part "RESISTOR0603"))
    )
    (comp (ref "R503")
      (value "100K")
      (footprint "eagle-import:0603")
      (libsource (lib "eagle-import") (part "RESISTOR0603"))
    )
    (comp (ref "R504")
      (value "10K")
      (footprint "eagle-import:0603")
      (libsource (lib "eagle-import") (part "330OHM-0603-1/10W-1%"))
    )
    (comp (ref "R505")
      (value "560r")
      (footprint "eagle-import:0603")
      (libsource (lib "eagle-import") (part "330OHM-0603-1/10W-1%"))
    )
    (comp (ref "R506")
      (value "560r")
      (footprint "eagle-import:0603")
      (libsource (lib "eagle-import") (part "330OHM-0603-1/10W-1%"))
    )
    (comp (ref "R507")
      (value "560r")
      (footprint "eagle-import:0603")
      (libsource (lib "eagle-import") (part "330OHM-0603-1/10W-1%"))
    )
    (comp (ref "S501")
      (value "RST")
      (footprint "eagle-import:TACTILE_SWITCH_SMD_5.2MM")
      (libsource (lib "eagle-import") (part "MOMENTARY-SWITCH-SPST-SMD-5.2-REDUNDANT"))
    )
    (comp (ref "S502")
      (value "SWITCH-SPDT-SMD-AYZ0202")
      (footprint "eagle-import:SWITCH_DPDT_SMD_AYZ0202")
      (libsource (lib "eagle-import") (part "SWITCH-SPDT-SMD-AYZ0202"))
    )
    (comp (ref "TP501")
      (value "PTR1TP20R")
      (footprint "eagle-import:TP20R")
      (libsource (lib "eagle-import") (part "PTR1TP20R"))
    )
    (comp (ref "TP502")
      (value "PTR1TP20R")
      (footprint "eagle-import:TP20R")
      (libsource (lib "eagle-import") (part "PTR1TP20R"))
    )
    (comp (ref "TP503")
      (value "PTR1TP20R")
      (footprint "eagle-import:TP20R")
      (libsource (lib "eagle-import") (part "PTR1TP20R"))
    )
    (comp (ref "TP504")
      (value "PTR1TP20R")
      (footprint "eagle-import:TP20R")
      (libsource (lib "eagle-import") (part "PTR1TP20R"))
    )
    (comp (ref "U501")
      (value "74HC1G04")
      (footprint "eagle-import:SOT353")
      (libsource (lib "eagle-import") (part "741G04HC"))
    )
    (comp (ref "U502")
      (value "SN74C1G08-DCK")
      (footprint "eagle-import:SC-70-5")
      (libsource (lib "eagle-import") (part "SN74C1G08-DCK"))
    )
    (comp (ref "U503")
      (value "ATTINY25-20SSUR")
      (footprint "eagle-import:SOIC8")
      (libsource (lib "eagle-import") (part "ATTINY45-SMT-NARROW"))
    )
    (comp (ref "U504")
      (value "MIC5205")
      (footprint "eagle-import:SOT23-5")
      (libsource (lib "eagle-import") (part "V_REG_MIC52055V"))
    )
    (comp (ref "C101")
      (value "2.2uF")
      (footprint "eagle-import:EIA3216")
      (libsource (lib "eagle-import") (part "10UF-POLAR-EIA3216-16V-10%(TANT)"))
    )
    (comp (ref "D101")
      (value "GREEN")
      (footprint "eagle-import:LED-0603")
      (libsource (lib "eagle-import") (part "LED-GREEN0603"))
    )
    (comp (ref "D102")
      (value "RED")
      (footprint "eagle-import:LED-0603")
      (libsource (lib "eagle-import") (part "LED-RED0603"))
    )
    (comp (ref "JP101")
      (value "JUMPER_NC_TRACE")
      (footprint "eagle-import:SMT-JUMPER_2_NC_TRACE_SILK")
      (libsource (lib "eagle-import") (part "JUMPER-SMT_2_NC_TRACE_SILK"))
    )
    (comp (ref "JP102")
      (value "JUMPER-SMT_2_NO_SILK")
      (footprint "eagle-import:SMT-JUMPER_2_NO_SILK")
      (libsource (lib "eagle-import") (part "JUMPER-SMT_2_NO_SILK"))
    )
    (comp (ref "R101")
      (value "10K")
      (footprint "eagle-import:0603")
      (libsource (lib "eagle-import") (part "330OHM-0603-1/10W-1%"))
    )
    (comp (ref "R102")
      (value "560r")
      (footprint "eagle-import:0603")
      (libsource (lib "eagle-import") (part "330OHM-0603-1/10W-1%"))
    )
    (comp (ref "R103")
      (value "560r")
      (footprint "eagle-import:0603")
      (libsource (lib "eagle-import") (part "330OHM-0603-1/10W-1%"))
    )
    (comp (ref "S101")
      (value "REED_SWITCH")
      (footprint "eagle-import:AXIAL_GULLWING_REED")
      (libsource (lib "eagle-import") (part "MDSM-10_REED_SWITCH"))
    )
    (comp (ref "S102")
      (value "SWITCH-SPDT-SMD-AYZ0202")
      (footprint "eagle-import:SWITCH_DPDT_SMD_AYZ0202")
      (libsource (lib "eagle-import") (part "SWITCH-SPDT-SMD-AYZ0202"))
    )
    (comp (ref "TP101")
      (value "PTR1TP20R")
      (footprint "eagle-import:TP20R")
      (libsource (lib "eagle-import") (part "PTR1TP20R"))
    )
    (comp (ref "U101")
      (value "74HC1G04")
      (footprint "eagle-import:SOT353")
      (libsource (lib "eagle-import") (part "741G04HC"))
    )
    (comp (ref "U102")
      (value "MIC5205")
      (footprint "eagle-import:SOT23-5")
      (libsource (lib "eagle-import") (part "V_REG_MIC52055V"))
    )
    (comp (ref "C801")
      (value "2.2uF")
      (footprint "eagle-import:EIA3216")
      (libsource (lib "eagle-import") (part "10UF-POLAR-EIA3216-16V-10%(TANT)"))
    )
    (comp (ref "D801")
      (value "SK310A-TP")
      (footprint "eagle-import:SMADIODE")
      (libsource (lib "eagle-import") (part "DIODESMA"))
    )
    (comp (ref "D802")
      (value "GREEN")
      (footprint "eagle-import:LED-0603")
      (libsource (lib "eagle-import") (part "LED-GREEN0603"))
    )
    (comp (ref "D803")
      (value "YELLOW")
      (footprint "eagle-import:LED-0603")
      (libsource (lib "eagle-import") (part "LED-YELLOW0603"))
    )
    (comp (ref "D804")
      (value "RED")
      (footprint "eagle-import:LED-0603")
      (libsource (lib "eagle-import") (part "LED-RED0603"))
    )
    (comp (ref "J801")
      (value "CONN_02LOCK")
      (footprint "eagle-import:1X02_LOCK")
      (libsource (lib "eagle-import") (part "CONN_02LOCK"))
    )
    (comp (ref "J802")
      (value "CONN_023.5MM_LOCK")
      (footprint "eagle-import:SCREWTERMINAL-3.5MM-2_LOCK")
      (libsource (lib "eagle-import") (part "CONN_023.5MM_LOCK"))
    )
    (comp (ref "Q801")
      (value "PSMN7R0-60YS")
      (footprint "eagle-import:SOT669")
      (libsource (lib "eagle-import") (part "PSMN7R0-60YS"))
    )
    (comp (ref "R801")
      (value "10K")
      (footprint "eagle-import:0603")
      (libsource (lib "eagle-import") (part "RESISTOR0603"))
    )
    (comp (ref "R802")
      (value "10R")
      (footprint "eagle-import:0603")
      (libsource (lib "eagle-import") (part "RESISTOR0603"))
    )
    (comp (ref "R803")
      (value "100K")
      (footprint "eagle-import:0603")
      (libsource (lib "eagle-import") (part "RESISTOR0603"))
    )
    (comp (ref "R804")
      (value "560r")
      (footprint "eagle-import:0603")
      (libsource (lib "eagle-import") (part "330OHM-0603-1/10W-1%"))
    )
    (comp (ref "R805")
      (value "560r")
      (footprint "eagle-import:0603")
      (libsource (lib "eagle-import") (part "330OHM-0603-1/10W-1%"))
    )
    (comp (ref "R806")
      (value "560r")
      (footprint "eagle-import:0603")
      (libsource (lib "eagle-import") (part "330OHM-0603-1/10W-1%"))
    )
    (comp (ref "S801")
      (value "SWITCH-SPDT-SMD-AYZ0202")
      (footprint "eagle-import:SWITCH_DPDT_SMD_AYZ0202")
      (libsource (lib "eagle-import") (part "SWITCH-SPDT-SMD-AYZ0202"))
    )
    (comp (ref "TP801")
      (value "PTR1TP20R")
      (footprint "eagle-import:TP20R")
      (libsource (lib "eagle-import") (part "PTR1TP20R"))
    )
    (comp (ref "TP802")
      (value "PTR1TP20R")
      (footprint "eagle-import:TP20R")
      (libsource (lib "eagle-import") (part "PTR1TP20R"))
    )
    (comp (ref "TP803")
      (value "PTR1TP20R")
      (footprint "eagle-import:TP20R")
      (libsource (lib "eagle-import") (part "PTR1TP20R"))
    )
    (comp (ref "U801")
      (value "74HC1G04")
      (footprint "eagle-import:SOT353")
      (libsource (lib "eagle-import") (part "741G04HC"))
    )
    (comp (ref "U802")
      (value "SN74C1G08-DCK")
      (footprint "eagle-import:SC-70-5")
      (libsource (lib "eagle-import") (part "SN74C1G08-DCK"))
    )
    (comp (ref "U803")
      (value "MIC5205")
      (footprint "eagle-import:SOT23-5")
      (libsource (lib "eagle-import") (part "V_REG_MIC52055V"))
    )
  )
  (nets
    (net (code "1") (name "BALLOON_IN") (class "Default")
      (node (ref "D1202") (pin "A") (pinfunction "A_A") (pintype "passive"))
      (node (ref "J1611") (pin "1") (pinfunction "1_1") (pintype "passive"))
      (node (ref "U1202") (pin "2") (pinfunction "PB3(ADC3)_2") (pintype "bidirectional"))
    )
    (net (code "2") (name "BALLOON_MISO") (class "Default")
      (node (ref "J1204") (pin "1") (pinfunction "1_1") (pintype "passive"))
      (node (ref "U1201") (pin "9") (pinfunction "AIN2/EN_9") (pintype "bidirectional"))
      (node (ref "U1202") (pin "6") (pinfunction "PB1(MISO)_6") (pintype "bidirectional"))
    )
    (net (code "3") (name "BALLOON_MOSI") (class "Default")
      (node (ref "J1204") (pin "4") (pinfunction "4_4") (pintype "passive"))
      (node (ref "U1201") (pin "10") (pinfunction "AIN1/PH_10") (pintype "bidirectional"))
      (node (ref "U1202") (pin "5") (pinfunction "PB0(MOSI)_5") (pintype "bidirectional"))
    )
    (net (code "4") (name "BALLOON_OUT") (class "Default")
      (node (ref "D1201") (pin "A") (pinfunction "A_A") (pintype "passive"))
      (node (ref "J1201") (pin "2") (pinfunction "2_2") (pintype "passive"))
      (node (ref "J1612") (pin "2") (pinfunction "2_2") (pintype "passive"))
      (node (ref "R1201") (pin "1") (pinfunction "1_1") (pintype "passive"))
      (node (ref "S1202") (pin "2") (pinfunction "P_2") (pintype "passive"))
    )
    (net (code "5") (name "BALLOON_RST") (class "Default")
      (node (ref "J1204") (pin "5") (pinfunction "5_5") (pintype "passive"))
      (node (ref "R1203") (pin "1") (pinfunction "1_1") (pintype "passive"))
      (node (ref "S1201") (pin "3") (pinfunction "2_3") (pintype "passive"))
      (node (ref "S1201") (pin "4") (pinfunction "2_4") (pintype "passive"))
      (node (ref "U1202") (pin "1") (pinfunction "PB5(NRES)_1") (pintype "bidirectional"))
    )
    (net (code "6") (name "BALLOON_SCK") (class "Default")
      (node (ref "J1202") (pin "2") (pinfunction "2_2") (pintype "passive"))
      (node (ref "J1204") (pin "3") (pinfunction "3_3") (pintype "passive"))
      (node (ref "R1202") (pin "1") (pinfunction "1_1") (pintype "passive"))
      (node (ref "U1202") (pin "7") (pinfunction "PB2(SCK/ADC1)_7") (pintype "bidirectional"))
    )
    (net (code "7") (name "BALLOON_VCC") (class "Default")
      (node (ref "C1201") (pin "2") (pinfunction "2_2") (pintype "passive"))
      (node (ref "C1203") (pin "1") (pinfunction "1_1") (pintype "passive"))
      (node (ref "D1203") (pin "A") (pinfunction "A_A") (pintype "passive"))
      (node (ref "IC1201") (pin "2") (pinfunction "VO_2") (pintype "passive"))
      (node (ref "J1201") (pin "1") (pinfunction "1_1") (pintype "passive"))
      (node (ref "J1202") (pin "1") (pinfunction "1_1") (pintype "passive"))
      (node (ref "J1204") (pin "2") (pinfunction "2_2") (pintype "passive"))
      (node (ref "R1203") (pin "2") (pinfunction "2_2") (pintype "passive"))
      (node (ref "S1202") (pin "1") (pinfunction "O_1") (pintype "passive"))
      (node (ref "TP1201") (pin "TP") (pinfunction "TP_TP") (pintype "input"))
      (node (ref "U1201") (pin "1") (pinfunction "VM_1") (pintype "bidirectional"))
      (node (ref "U1201") (pin "11") (pinfunction "MODE_11") (pintype "bidirectional"))
      (node (ref "U1201") (pin "12") (pinfunction "VCC_12") (pintype "bidirectional"))
      (node (ref "U1202") (pin "8") (pinfunction "VCC_8") (pintype "bidirectional"))
    )
    (net (code "8") (name "COIN_IN") (class "Default")
      (node (ref "D203") (pin "A") (pinfunction "A_A") (pintype "passive"))
      (node (ref "J1601") (pin "1") (pinfunction "1_1") (pintype "passive"))
      (node (ref "JP201") (pin "1") (pinfunction "1_1") (pintype "passive"))
      (node (ref "U201") (pin "2") (pinfunction "A_2") (pintype "bidirectional"))
    )
    (net (code "9") (name "COIN_MISO") (class "Default")
      (node (ref "J204") (pin "1") (pinfunction "1_1") (pintype "passive"))
      (node (ref "U202") (pin "6") (pinfunction "PB1(MISO)_6") (pintype "bidirectional"))
    )
    (net (code "10") (name "COIN_MOSI") (class "Default")
      (node (ref "J204") (pin "4") (pinfunction "4_4") (pintype "passive"))
      (node (ref "U202") (pin "5") (pinfunction "PB0(MOSI)_5") (pintype "bidirectional"))
    )
    (net (code "11") (name "COIN_OUT") (class "Default")
      (node (ref "D202") (pin "A") (pinfunction "A_A") (pintype "passive"))
      (node (ref "J1602") (pin "2") (pinfunction "2_2") (pintype "passive"))
      (node (ref "S202") (pin "2") (pinfunction "P_2") (pintype "passive"))
    )
    (net (code "12") (name "COIN_OUT_SWITCH") (class "Default")
      (node (ref "S202") (pin "3") (pinfunction "S_3") (pintype "passive"))
      (node (ref "U202") (pin "3") (pinfunction "PB4(ADC2)_3") (pintype "bidirectional"))
    )
    (net (code "13") (name "COIN_RST") (class "Default")
      (node (ref "J204") (pin "5") (pinfunction "5_5") (pintype "passive"))
      (node (ref "R204") (pin "1") (pinfunction "1_1") (pintype "passive"))
      (node (ref "S201") (pin "3") (pinfunction "2_3") (pintype "passive"))
      (node (ref "S201") (pin "4") (pinfunction "2_4") (pintype "passive"))
      (node (ref "U202") (pin "1") (pinfunction "PB5(NRES)_1") (pintype "bidirectional"))
    )
    (net (code "14") (name "COIN_SCK") (class "Default")
      (node (ref "J201") (pin "1") (pinfunction "1_1") (pintype "passive"))
      (node (ref "J204") (pin "3") (pinfunction "3_3") (pintype "passive"))
      (node (ref "R203") (pin "1") (pinfunction "1_1") (pintype "passive"))
      (node (ref "U202") (pin "7") (pinfunction "PB2(SCK/ADC1)_7") (pintype "bidirectional"))
    )
    (net (code "15") (name "COIN_VCC") (class "Default")
      (node (ref "C201") (pin "2") (pinfunction "2_2") (pintype "passive"))
      (node (ref "C202") (pin "+") (pinfunction "+_+") (pintype "passive"))
      (node (ref "D204") (pin "A") (pinfunction "A_A") (pintype "passive"))
      (node (ref "J204") (pin "2") (pinfunction "2_2") (pintype "passive"))
      (node (ref "R203") (pin "2") (pinfunction "2_2") (pintype "passive"))
      (node (ref "R204") (pin "2") (pinfunction "2_2") (pintype "passive"))
      (node (ref "S202") (pin "1") (pinfunction "O_1") (pintype "passive"))
      (node (ref "TP202") (pin "TP") (pinfunction "TP_TP") (pintype "input"))
      (node (ref "U201") (pin "5") (pinfunction "P$V+_5") (pintype "bidirectional"))
      (node (ref "U202") (pin "8") (pinfunction "VCC_8") (pintype "bidirectional"))
      (node (ref "U203") (pin "5") (pinfunction "OUT_5") (pintype "passive"))
    )
    (net (code "16") (name "EMAG_IN") (class "Default")
      (node (ref "D803") (pin "A") (pinfunction "A_A") (pintype "passive"))
      (node (ref "J1607") (pin "1") (pinfunction "1_1") (pintype "passive"))
      (node (ref "U802") (pin "1") (pinfunction "A_1") (pintype "input"))
    )
    (net (code "17") (name "EMAG_OUT") (class "Default")
      (node (ref "D802") (pin "A") (pinfunction "A_A") (pintype "passive"))
      (node (ref "J1608") (pin "2") (pinfunction "2_2") (pintype "passive"))
      (node (ref "J801") (pin "1") (pinfunction "1_1") (pintype "passive"))
      (node (ref "R801") (pin "2") (pinfunction "2_2") (pintype "passive"))
      (node (ref "S801") (pin "2") (pinfunction "P_2") (pintype "passive"))
      (node (ref "U801") (pin "2") (pinfunction "A_2") (pintype "bidirectional"))
    )
    (net (code "18") (name "EMAG_VCC") (class "Default")
      (node (ref "C801") (pin "+") (pinfunction "+_+") (pintype "passive"))
      (node (ref "D804") (pin "A") (pinfunction "A_A") (pintype "passive"))
      (node (ref "J801") (pin "2") (pinfunction "2_2") (pintype "passive"))
      (node (ref "S801") (pin "1") (pinfunction "O_1") (pintype "passive"))
      (node (ref "TP801") (pin "TP") (pinfunction "TP_TP") (pintype "input"))
      (node (ref "U801") (pin "5") (pinfunction "P$V+_5") (pintype "bidirectional"))
      (node (ref "U802") (pin "5") (pinfunction "VCC_5") (pintype "power_in"))
      (node (ref "U803") (pin "5") (pinfunction "OUT_5") (pintype "passive"))
    )
    (net (code "19") (name "ENDO_IN") (class "Default")
      (node (ref "D503") (pin "A") (pinfunction "A_A") (pintype "passive"))
      (node (ref "J1604") (pin "1") (pinfunction "1_1") (pintype "passive"))
      (node (ref "U502") (pin "1") (pinfunction "A_1") (pintype "input"))
    )
    (net (code "20") (name "ENDO_MISO") (class "Default")
      (node (ref "J503") (pin "1") (pinfunction "1_1") (pintype "passive"))
      (node (ref "U503") (pin "6") (pinfunction "PB1(MISO)_6") (pintype "bidirectional"))
    )
    (net (code "21") (name "ENDO_MOSI") (class "Default")
      (node (ref "J503") (pin "4") (pinfunction "4_4") (pintype "passive"))
      (node (ref "U503") (pin "5") (pinfunction "PB0(MOSI)_5") (pintype "bidirectional"))
    )
    (net (code "22") (name "ENDO_OUT") (class "Default")
      (node (ref "D502") (pin "A") (pinfunction "A_A") (pintype "passive"))
      (node (ref "J1605") (pin "2") (pinfunction "2_2") (pintype "passive"))
      (node (ref "S502") (pin "2") (pinfunction "P_2") (pintype "passive"))
      (node (ref "U501") (pin "2") (pinfunction "A_2") (pintype "bidirectional"))
    )
    (net (code "23") (name "ENDO_OUT_SWITCH") (class "Default")
      (node (ref "S502") (pin "3") (pinfunction "S_3") (pintype "passive"))
      (node (ref "U503") (pin "3") (pinfunction "PB4(ADC2)_3") (pintype "bidirectional"))
    )
    (net (code "24") (name "ENDO_RST") (class "Default")
      (node (ref "J503") (pin "5") (pinfunction "5_5") (pintype "passive"))
      (node (ref "R504") (pin "1") (pinfunction "1_1") (pintype "passive"))
      (node (ref "S501") (pin "3") (pinfunction "2_3") (pintype "passive"))
      (node (ref "S501") (pin "4") (pinfunction "2_4") (pintype "passive"))
      (node (ref "U503") (pin "1") (pinfunction "PB5(NRES)_1") (pintype "bidirectional"))
    )
    (net (code "25") (name "ENDO_SCK") (class "Default")
      (node (ref "J503") (pin "3") (pinfunction "3_3") (pintype "passive"))
      (node (ref "R501") (pin "2") (pinfunction "2_2") (pintype "passive"))
      (node (ref "U503") (pin "7") (pinfunction "PB2(SCK/ADC1)_7") (pintype "bidirectional"))
    )
    (net (code "26") (name "ENDO_VCC") (class "Default")
      (node (ref "C501") (pin "2") (pinfunction "2_2") (pintype "passive"))
      (node (ref "C502") (pin "+") (pinfunction "+_+") (pintype "passive"))
      (node (ref "D504") (pin "A") (pinfunction "A_A") (pintype "passive"))
      (node (ref "J503") (pin "2") (pinfunction "2_2") (pintype "passive"))
      (node (ref "R504") (pin "2") (pinfunction "2_2") (pintype "passive"))
      (node (ref "S502") (pin "1") (pinfunction "O_1") (pintype "passive"))
      (node (ref "TP503") (pin "TP") (pinfunction "TP_TP") (pintype "input"))
      (node (ref "U501") (pin "5") (pinfunction "P$V+_5") (pintype "bidirectional"))
      (node (ref "U502") (pin "5") (pinfunction "VCC_5") (pintype "power_in"))
      (node (ref "U503") (pin "8") (pinfunction "VCC_8") (pintype "bidirectional"))
      (node (ref "U504") (pin "5") (pinfunction "OUT_5") (pintype "passive"))
    )
    (net (code "27") (name "END_IN") (class "Default")
      (node (ref "D1501") (pin "A") (pinfunction "A_A") (pintype "passive"))
      (node (ref "J1501") (pin "1") (pinfunction "1_1") (pintype "passive"))
      (node (ref "J1614") (pin "1") (pinfunction "1_1") (pintype "passive"))
      (node (ref "R1501") (pin "2") (pinfunction "2_2") (pintype "passive"))
    )
    (net (code "28") (name "END_VCC") (class "Default")
      (node (ref "C1502") (pin "1") (pinfunction "1_1") (pintype "passive"))
      (node (ref "D1502") (pin "A") (pinfunction "A_A") (pintype "passive"))
      (node (ref "IC1501") (pin "2") (pinfunction "VO_2") (pintype "passive"))
      (node (ref "J1501") (pin "2") (pinfunction "2_2") (pintype "passive"))
      (node (ref "TP1501") (pin "TP") (pinfunction "TP_TP") (pintype "input"))
    )
    (net (code "29") (name "EXO_IN") (class "Default")
      (node (ref "D303") (pin "A") (pinfunction "A_A") (pintype "passive"))
      (node (ref "J1602") (pin "1") (pinfunction "1_1") (pintype "passive"))
      (node (ref "U302") (pin "1") (pinfunction "A_1") (pintype "input"))
    )
    (net (code "30") (name "EXO_MISO") (class "Default")
      (node (ref "J301") (pin "1") (pinfunction "1_1") (pintype "passive"))
      (node (ref "U303") (pin "6") (pinfunction "PB1(MISO)_6") (pintype "bidirectional"))
    )
    (net (code "31") (name "EXO_MOSI") (class "Default")
      (node (ref "J301") (pin "4") (pinfunction "4_4") (pintype "passive"))
      (node (ref "U303") (pin "5") (pinfunction "PB0(MOSI)_5") (pintype "bidirectional"))
    )
    (net (code "32") (name "EXO_OUT") (class "Default")
      (node (ref "D302") (pin "A") (pinfunction "A_A") (pintype "passive"))
      (node (ref "J1603") (pin "2") (pinfunction "2_2") (pintype "passive"))
      (node (ref "S302") (pin "2") (pinfunction "P_2") (pintype "passive"))
      (node (ref "U301") (pin "2") (pinfunction "A_2") (pintype "bidirectional"))
    )
    (net (code "33") (name "EXO_OUT_SWITCH") (class "Default")
      (node (ref "S302") (pin "3") (pinfunction "S_3") (pintype "passive"))
      (node (ref "U303") (pin "3") (pinfunction "PB4(ADC2)_3") (pintype "bidirectional"))
    )
    (net (code "34") (name "EXO_RST") (class "Default")
      (node (ref "J301") (pin "5") (pinfunction "5_5") (pintype "passive"))
      (node (ref "R304") (pin "1") (pinfunction "1_1") (pintype "passive"))
      (node (ref "S301") (pin "3") (pinfunction "2_3") (pintype "passive"))
      (node (ref "S301") (pin "4") (pinfunction "2_4") (pintype "passive"))
      (node (ref "U303") (pin "1") (pinfunction "PB5(NRES)_1") (pintype "bidirectional"))
    )
    (net (code "35") (name "EXO_SCK") (class "Default")
      (node (ref "J301") (pin "3") (pinfunction "3_3") (pintype "passive"))
      (node (ref "R301") (pin "2") (pinfunction "2_2") (pintype "passive"))
      (node (ref "R303") (pin "1") (pinfunction "P$1_1") (pintype "bidirectional"))
      (node (ref "U303") (pin "7") (pinfunction "PB2(SCK/ADC1)_7") (pintype "bidirectional"))
    )
    (net (code "36") (name "EXO_VCC") (class "Default")
      (node (ref "C301") (pin "2") (pinfunction "2_2") (pintype "passive"))
      (node (ref "C302") (pin "+") (pinfunction "+_+") (pintype "passive"))
      (node (ref "D304") (pin "A") (pinfunction "A_A") (pintype "passive"))
      (node (ref "J301") (pin "2") (pinfunction "2_2") (pintype "passive"))
      (node (ref "Q301") (pin "3") (pinfunction "C_3") (pintype "passive"))
      (node (ref "R303") (pin "2") (pinfunction "P$2_2") (pintype "bidirectional"))
      (node (ref "R304") (pin "2") (pinfunction "2_2") (pintype "passive"))
      (node (ref "S302") (pin "1") (pinfunction "O_1") (pintype "passive"))
      (node (ref "U301") (pin "5") (pinfunction "P$V+_5") (pintype "bidirectional"))
      (node (ref "U302") (pin "5") (pinfunction "VCC_5") (pintype "power_in"))
      (node (ref "U303") (pin "8") (pinfunction "VCC_8") (pintype "bidirectional"))
      (node (ref "U304") (pin "5") (pinfunction "OUT_5") (pintype "passive"))
    )
    (net (code "37") (name "EXP_IN") (class "Default")
      (node (ref "D1003") (pin "A") (pinfunction "A_A") (pintype "passive"))
      (node (ref "J1609") (pin "1") (pinfunction "1_1") (pintype "passive"))
      (node (ref "U1001") (pin "2") (pinfunction "PB3(ADC3)_2") (pintype "bidirectional"))
    )
    (net (code "38") (name "EXP_MISO") (class "Default")
      (node (ref "J1005") (pin "1") (pinfunction "1_1") (pintype "passive"))
      (node (ref "U1001") (pin "6") (pinfunction "PB1(MISO)_6") (pintype "bidirectional"))
    )
    (net (code "39") (name "EXP_MOSI") (class "Default")
      (node (ref "J1005") (pin "4") (pinfunction "4_4") (pintype "passive"))
      (node (ref "R1001") (pin "1") (pinfunction "1_1") (pintype "passive"))
      (node (ref "R1002") (pin "1") (pinfunction "1_1") (pintype "passive"))
      (node (ref "U1001") (pin "5") (pinfunction "PB0(MOSI)_5") (pintype "bidirectional"))
    )
    (net (code "40") (name "EXP_OUT") (class "Default")
      (node (ref "D1002") (pin "A") (pinfunction "A_A") (pintype "passive"))
      (node (ref "J1004") (pin "2") (pinfunction "2_2") (pintype "passive"))
      (node (ref "J1610") (pin "2") (pinfunction "2_2") (pintype "passive"))
      (node (ref "R1004") (pin "1") (pinfunction "1_1") (pintype "passive"))
      (node (ref "S1002") (pin "2") (pinfunction "P_2") (pintype "passive"))
    )
    (net (code "41") (name "EXP_RST") (class "Default")
      (node (ref "J1005") (pin "5") (pinfunction "5_5") (pintype "passive"))
      (node (ref "R1005") (pin "1") (pinfunction "1_1") (pintype "passive"))
      (node (ref "S1001") (pin "3") (pinfunction "2_3") (pintype "passive"))
      (node (ref "S1001") (pin "4") (pinfunction "2_4") (pintype "passive"))
      (node (ref "U1001") (pin "1") (pinfunction "PB5(NRES)_1") (pintype "bidirectional"))
    )
    (net (code "42") (name "EXP_SCK") (class "Default")
      (node (ref "J1005") (pin "3") (pinfunction "3_3") (pintype "passive"))
      (node (ref "R1003") (pin "2") (pinfunction "2_2") (pintype "passive"))
      (node (ref "U1001") (pin "7") (pinfunction "PB2(SCK/ADC1)_7") (pintype "bidirectional"))
    )
    (net (code "43") (name "EXP_VCC") (class "Default")
      (node (ref "C1001") (pin "2") (pinfunction "2_2") (pintype "passive"))
      (node (ref "C1002") (pin "+") (pinfunction "+_+") (pintype "passive"))
      (node (ref "D1004") (pin "A") (pinfunction "A_A") (pintype "passive"))
      (node (ref "J1004") (pin "1") (pinfunction "1_1") (pintype "passive"))
      (node (ref "J1005") (pin "2") (pinfunction "2_2") (pintype "passive"))
      (node (ref "R1005") (pin "2") (pinfunction "2_2") (pintype "passive"))
      (node (ref "S1002") (pin "1") (pinfunction "O_1") (pintype "passive"))
      (node (ref "TP1001") (pin "TP") (pinfunction "TP_TP") (pintype "input"))
      (node (ref "U1001") (pin "8") (pinfunction "VCC_8") (pintype "bidirectional"))
      (node (ref "U1002") (pin "5") (pinfunction "OUT_5") (pintype "passive"))
    )
    (net (code "44") (name "GND") (class "Default")
      (node (ref "C1001") (pin "1") (pinfunction "1_1") (pintype "passive"))
      (node (ref "C1002") (pin "-") (pinfunction "-_-") (pintype "passive"))
      (node (ref "C101") (pin "-") (pinfunction "-_-") (pintype "passive"))
      (node (ref "C1101") (pin "1") (pinfunction "1_1") (pintype "passive"))
      (node (ref "C1102") (pin "1") (pinfunction "1_1") (pintype "passive"))
      (node (ref "C1103") (pin "2") (pinfunction "2_2") (pintype "passive"))
      (node (ref "C1201") (pin "1") (pinfunction "1_1") (pintype "passive"))
      (node (ref "C1202") (pin "1") (pinfunction "1_1") (pintype "passive"))
      (node (ref "C1203") (pin "2") (pinfunction "2_2") (pintype "passive"))
      (node (ref "C1301") (pin "1") (pinfunction "1_1") (pintype "passive"))
      (node (ref "C1302") (pin "1") (pinfunction "1_1") (pintype "passive"))
      (node (ref "C1303") (pin "2") (pinfunction "2_2") (pintype "passive"))
      (node (ref "C1401") (pin "-") (pinfunction "-_-") (pintype "passive"))
      (node (ref "C1501") (pin "1") (pinfunction "1_1") (pintype "passive"))
      (node (ref "C1502") (pin "2") (pinfunction "2_2") (pintype "passive"))
      (node (ref "C1601") (pin "-") (pinfunction "-_-") (pintype "passive"))
      (node (ref "C1602") (pin "-") (pinfunction "-_-") (pintype "passive"))
      (node (ref "C1603") (pin "-") (pinfunction "-_-") (pintype "passive"))
      (node (ref "C1604") (pin "2") (pinfunction "2_2") (pintype "passive"))
      (node (ref "C201") (pin "1") (pinfunction "1_1") (pintype "passive"))
      (node (ref "C202") (pin "-") (pinfunction "-_-") (pintype "passive"))
      (node (ref "C301") (pin "1") (pinfunction "1_1") (pintype "passive"))
      (node (ref "C302") (pin "-") (pinfunction "-_-") (pintype "passive"))
      (node (ref "C401") (pin "1") (pinfunction "1_1") (pintype "passive"))
      (node (ref "C402") (pin "-") (pinfunction "-_-") (pintype "passive"))
      (node (ref "C501") (pin "1") (pinfunction "1_1") (pintype "passive"))
      (node (ref "C502") (pin "-") (pinfunction "-_-") (pintype "passive"))
      (node (ref "C601") (pin "1") (pinfunction "1_1") (pintype "passive"))
      (node (ref "C602") (pin "-") (pinfunction "-_-") (pintype "passive"))
      (node (ref "C701") (pin "1") (pinfunction "1_1") (pintype "passive"))
      (node (ref "C702") (pin "1") (pinfunction "1_1") (pintype "passive"))
      (node (ref "C703") (pin "-") (pinfunction "-_-") (pintype "passive"))
      (node (ref "C801") (pin "-") (pinfunction "-_-") (pintype "passive"))
      (node (ref "C901") (pin "1") (pinfunction "1_1") (pintype "passive"))
      (node (ref "C902") (pin "-") (pinfunction "-_-") (pintype "passive"))
      (node (ref "D1601") (pin "A") (pinfunction "A_A") (pintype "passive"))
      (node (ref "D301") (pin "K") (pinfunction "C_K") (pintype "passive"))
      (node (ref "IC1101") (pin "3") (pinfunction "GND_3") (pintype "passive"))
      (node (ref "IC1201") (pin "3") (pinfunction "GND_3") (pintype "passive"))
      (node (ref "IC1301") (pin "3") (pinfunction "GND_3") (pintype "passive"))
      (node (ref "IC1501") (pin "3") (pinfunction "GND_3") (pintype "passive"))
      (node (ref "J1002") (pin "2") (pinfunction "2_2") (pintype "passive"))
      (node (ref "J1003") (pin "2") (pinfunction "2_2") (pintype "passive"))
      (node (ref "J1005") (pin "6") (pinfunction "6_6") (pintype "passive"))
      (node (ref "J1104") (pin "6") (pinfunction "6_6") (pintype "passive"))
      (node (ref "J1204") (pin "6") (pinfunction "6_6") (pintype "passive"))
      (node (ref "J1304") (pin "6") (pinfunction "6_6") (pintype "passive"))
      (node (ref "J1501") (pin "3") (pinfunction "3_3") (pintype "passive"))
      (node (ref "J201") (pin "3") (pinfunction "3_3") (pintype "passive"))
      (node (ref "J202") (pin "2") (pinfunction "2_2") (pintype "passive"))
      (node (ref "J204") (pin "6") (pinfunction "6_6") (pintype "passive"))
      (node (ref "J301") (pin "6") (pinfunction "6_6") (pintype "passive"))
      (node (ref "J401") (pin "6") (pinfunction "6_6") (pintype "passive"))
      (node (ref "J501") (pin "2") (pinfunction "2_2") (pintype "passive"))
      (node (ref "J503") (pin "6") (pinfunction "6_6") (pintype "passive"))
      (node (ref "J601") (pin "2") (pinfunction "2_2") (pintype "passive"))
      (node (ref "J603") (pin "6") (pinfunction "6_6") (pintype "passive"))
      (node (ref "J701") (pin "2") (pinfunction "2_2") (pintype "passive"))
      (node (ref "J703") (pin "6") (pinfunction "6_6") (pintype "passive"))
      (node (ref "J704") (pin "6") (pinfunction "6_6") (pintype "passive"))
      (node (ref "J903") (pin "6") (pinfunction "6_6") (pintype "passive"))
      (node (ref "Q1001") (pin "1") (pinfunction "S_1") (pintype "passive"))
      (node (ref "Q1001") (pin "2") (pinfunction "S_2") (pintype "passive"))
      (node (ref "Q1001") (pin "3") (pinfunction "S_3") (pintype "passive"))
      (node (ref "Q1401") (pin "1") (pinfunction "S_1") (pintype "passive"))
      (node (ref "Q1401") (pin "2") (pinfunction "S_2") (pintype "passive"))
      (node (ref "Q1401") (pin "3") (pinfunction "S_3") (pintype "passive"))
      (node (ref "Q201") (pin "1") (pinfunction "S_1") (pintype "passive"))
      (node (ref "Q201") (pin "2") (pinfunction "S_2") (pintype "passive"))
      (node (ref "Q201") (pin "3") (pinfunction "S_3") (pintype "passive"))
      (node (ref "Q501") (pin "1") (pinfunction "S_1") (pintype "passive"))
      (node (ref "Q501") (pin "2") (pinfunction "S_2") (pintype "passive"))
      (node (ref "Q501") (pin "3") (pinfunction "S_3") (pintype "passive"))
      (node (ref "Q601") (pin "1") (pinfunction "S_1") (pintype "passive"))
      (node (ref "Q601") (pin "2") (pinfunction "S_2") (pintype "passive"))
      (node (ref "Q601") (pin "3") (pinfunction "S_3") (pintype "passive"))
      (node (ref "Q801") (pin "1") (pinfunction "S_1") (pintype "passive"))
      (node (ref "Q801") (pin "2") (pinfunction "S_2") (pintype "passive"))
      (node (ref "Q801") (pin "3") (pinfunction "S_3") (pintype "passive"))
      (node (ref "Q901") (pin "1") (pinfunction "S_1") (pintype "passive"))
      (node (ref "Q901") (pin "2") (pinfunction "S_2") (pintype "passive"))
      (node (ref "Q901") (pin "3") (pinfunction "S_3") (pintype "passive"))
      (node (ref "R1002") (pin "2") (pinfunction "2_2") (pintype "passive"))
      (node (ref "R1004") (pin "2") (pinfunction "2_2") (pintype "passive"))
      (node (ref "R1006") (pin "1") (pinfunction "1_1") (pintype "passive"))
      (node (ref "R1007") (pin "1") (pinfunction "1_1") (pintype "passive"))
      (node (ref "R1008") (pin "1") (pinfunction "1_1") (pintype "passive"))
      (node (ref "R102") (pin "1") (pinfunction "1_1") (pintype "passive"))
      (node (ref "R103") (pin "1") (pinfunction "1_1") (pintype "passive"))
      (node (ref "R1101") (pin "2") (pinfunction "2_2") (pintype "passive"))
      (node (ref "R1102") (pin "2") (pinfunction "2_2") (pintype "passive"))
      (node (ref "R1104") (pin "1") (pinfunction "1_1") (pintype "passive"))
      (node (ref "R1105") (pin "1") (pinfunction "1_1") (pintype "passive"))
      (node (ref "R1106") (pin "1") (pinfunction "1_1") (pintype "passive"))
      (node (ref "R1201") (pin "2") (pinfunction "2_2") (pintype "passive"))
      (node (ref "R1202") (pin "2") (pinfunction "2_2") (pintype "passive"))
      (node (ref "R1204") (pin "1") (pinfunction "1_1") (pintype "passive"))
      (node (ref "R1205") (pin "1") (pinfunction "1_1") (pintype "passive"))
      (node (ref "R1206") (pin "1") (pinfunction "1_1") (pintype "passive"))
      (node (ref "R1301") (pin "2") (pinfunction "2_2") (pintype "passive"))
      (node (ref "R1302") (pin "2") (pinfunction "2_2") (pintype "passive"))
      (node (ref "R1304") (pin "1") (pinfunction "1_1") (pintype "passive"))
      (node (ref "R1305") (pin "1") (pinfunction "1_1") (pintype "passive"))
      (node (ref "R1306") (pin "1") (pinfunction "1_1") (pintype "passive"))
      (node (ref "R1401") (pin "2") (pinfunction "2_2") (pintype "passive"))
      (node (ref "R1403") (pin "2") (pinfunction "2_2") (pintype "passive"))
      (node (ref "R1404") (pin "1") (pinfunction "1_1") (pintype "passive"))
      (node (ref "R1405") (pin "1") (pinfunction "1_1") (pintype "passive"))
      (node (ref "R1406") (pin "1") (pinfunction "1_1") (pintype "passive"))
      (node (ref "R1501") (pin "1") (pinfunction "1_1") (pintype "passive"))
      (node (ref "R1502") (pin "1") (pinfunction "1_1") (pintype "passive"))
      (node (ref "R1503") (pin "1") (pinfunction "1_1") (pintype "passive"))
      (node (ref "R202") (pin "2") (pinfunction "2_2") (pintype "passive"))
      (node (ref "R205") (pin "1") (pinfunction "1_1") (pintype "passive"))
      (node (ref "R206") (pin "1") (pinfunction "1_1") (pintype "passive"))
      (node (ref "R207") (pin "1") (pinfunction "1_1") (pintype "passive"))
      (node (ref "R301") (pin "1") (pinfunction "1_1") (pintype "passive"))
      (node (ref "R305") (pin "1") (pinfunction "1_1") (pintype "passive"))
      (node (ref "R306") (pin "1") (pinfunction "1_1") (pintype "passive"))
      (node (ref "R307") (pin "1") (pinfunction "1_1") (pintype "passive"))
      (node (ref "R401") (pin "1") (pinfunction "1_1") (pintype "passive"))
      (node (ref "R404") (pin "2") (pinfunction "2_2") (pintype "passive"))
      (node (ref "R406") (pin "1") (pinfunction "1_1") (pintype "passive"))
      (node (ref "R407") (pin "1") (pinfunction "1_1") (pintype "passive"))
      (node (ref "R408") (pin "1") (pinfunction "1_1") (pintype "passive"))
      (node (ref "R503") (pin "2") (pinfunction "2_2") (pintype "passive"))
      (node (ref "R505") (pin "1") (pinfunction "1_1") (pintype "passive"))
      (node (ref "R506") (pin "1") (pinfunction "1_1") (pintype "passive"))
      (node (ref "R507") (pin "1") (pinfunction "1_1") (pintype "passive"))
      (node (ref "R602") (pin "2") (pinfunction "2_2") (pintype "passive"))
      (node (ref "R605") (pin "1") (pinfunction "1_1") (pintype "passive"))
      (node (ref "R606") (pin "1") (pinfunction "1_1") (pintype "passive"))
      (node (ref "R607") (pin "1") (pinfunction "1_1") (pintype "passive"))
      (node (ref "R705") (pin "1") (pinfunction "1_1") (pintype "passive"))
      (node (ref "R706") (pin "1") (pinfunction "1_1") (pintype "passive"))
      (node (ref "R707") (pin "1") (pinfunction "1_1") (pintype "passive"))
      (node (ref "R801") (pin "1") (pinfunction "1_1") (pintype "passive"))
      (node (ref "R803") (pin "2") (pinfunction "2_2") (pintype "passive"))
      (node (ref "R804") (pin "1") (pinfunction "1_1") (pintype "passive"))
      (node (ref "R805") (pin "1") (pinfunction "1_1") (pintype "passive"))
      (node (ref "R806") (pin "1") (pinfunction "1_1") (pintype "passive"))
      (node (ref "R902") (pin "2") (pinfunction "2_2") (pintype "passive"))
      (node (ref "R903") (pin "2") (pinfunction "2_2") (pintype "passive"))
      (node (ref "R905") (pin "1") (pinfunction "1_1") (pintype "passive"))
      (node (ref "R906") (pin "1") (pinfunction "1_1") (pintype "passive"))
      (node (ref "R907") (pin "1") (pinfunction "1_1") (pintype "passive"))
      (node (ref "S1001") (pin "1") (pinfunction "1_1") (pintype "passive"))
      (node (ref "S1001") (pin "2") (pinfunction "1_2") (pintype "passive"))
      (node (ref "S101") (pin "P$1") (pinfunction "1_P$1") (pintype "passive"))
      (node (ref "S1101") (pin "1") (pinfunction "1_1") (pintype "passive"))
      (node (ref "S1101") (pin "2") (pinfunction "1_2") (pintype "passive"))
      (node (ref "S1201") (pin "1") (pinfunction "1_1") (pintype "passive"))
      (node (ref "S1201") (pin "2") (pinfunction "1_2") (pintype "passive"))
      (node (ref "S1301") (pin "1") (pinfunction "1_1") (pintype "passive"))
      (node (ref "S1301") (pin "2") (pinfunction "1_2") (pintype "passive"))
      (node (ref "S201") (pin "1") (pinfunction "1_1") (pintype "passive"))
      (node (ref "S201") (pin "2") (pinfunction "1_2") (pintype "passive"))
      (node (ref "S301") (pin "1") (pinfunction "1_1") (pintype "passive"))
      (node (ref "S301") (pin "2") (pinfunction "1_2") (pintype "passive"))
      (node (ref "S401") (pin "1") (pinfunction "1_1") (pintype "passive"))
      (node (ref "S401") (pin "2") (pinfunction "1_2") (pintype "passive"))
      (node (ref "S501") (pin "1") (pinfunction "1_1") (pintype "passive"))
      (node (ref "S501") (pin "2") (pinfunction "1_2") (pintype "passive"))
      (node (ref "S601") (pin "1") (pinfunction "1_1") (pintype "passive"))
      (node (ref "S601") (pin "2") (pinfunction "1_2") (pintype "passive"))
      (node (ref "S701") (pin "1") (pinfunction "1_1") (pintype "passive"))
      (node (ref "S701") (pin "2") (pinfunction "1_2") (pintype "passive"))
      (node (ref "S702") (pin "1") (pinfunction "1_1") (pintype "passive"))
      (node (ref "S702") (pin "2") (pinfunction "1_2") (pintype "passive"))
      (node (ref "S901") (pin "1") (pinfunction "1_1") (pintype "passive"))
      (node (ref "S901") (pin "2") (pinfunction "1_2") (pintype "passive"))
      (node (ref "U1001") (pin "4") (pinfunction "GND_4") (pintype "bidirectional"))
      (node (ref "U1002") (pin "2") (pinfunction "GND_2") (pintype "input"))
      (node (ref "U101") (pin "3") (pinfunction "P$V-_3") (pintype "bidirectional"))
      (node (ref "U102") (pin "2") (pinfunction "GND_2") (pintype "input"))
      (node (ref "U1101") (pin "6") (pinfunction "VSS_6") (pintype "bidirectional"))
      (node (ref "U1101") (pin "PAD") (pinfunction "VSS_PAD") (pintype "bidirectional"))
      (node (ref "U1102") (pin "4") (pinfunction "GND_4") (pintype "bidirectional"))
      (node (ref "U1201") (pin "6") (pinfunction "VSS_6") (pintype "bidirectional"))
      (node (ref "U1201") (pin "PAD") (pinfunction "VSS_PAD") (pintype "bidirectional"))
      (node (ref "U1202") (pin "4") (pinfunction "GND_4") (pintype "bidirectional"))
      (node (ref "U1301") (pin "6") (pinfunction "VSS_6") (pintype "bidirectional"))
      (node (ref "U1301") (pin "PAD") (pinfunction "VSS_PAD") (pintype "bidirectional"))
      (node (ref "U1302") (pin "4") (pinfunction "GND_4") (pintype "bidirectional"))
      (node (ref "U1401") (pin "3") (pinfunction "P$V-_3") (pintype "bidirectional"))
      (node (ref "U1402") (pin "2") (pinfunction "GND_2") (pintype "input"))
      (node (ref "U201") (pin "3") (pinfunction "P$V-_3") (pintype "bidirectional"))
      (node (ref "U202") (pin "4") (pinfunction "GND_4") (pintype "bidirectional"))
      (node (ref "U203") (pin "2") (pinfunction "GND_2") (pintype "input"))
      (node (ref "U301") (pin "3") (pinfunction "P$V-_3") (pintype "bidirectional"))
      (node (ref "U302") (pin "3") (pinfunction "GND_3") (pintype "power_in"))
      (node (ref "U303") (pin "4") (pinfunction "GND_4") (pintype "bidirectional"))
      (node (ref "U304") (pin "2") (pinfunction "GND_2") (pintype "input"))
      (node (ref "U401") (pin "3") (pinfunction "P$V-_3") (pintype "bidirectional"))
      (node (ref "U402") (pin "3") (pinfunction "GND_3") (pintype "power_in"))
      (node (ref "U403") (pin "4") (pinfunction "GND_4") (pintype "bidirectional"))
      (node (ref "U404") (pin "2") (pinfunction "GND_2") (pintype "input"))
      (node (ref "U501") (pin "3") (pinfunction "P$V-_3") (pintype "bidirectional"))
      (node (ref "U502") (pin "3") (pinfunction "GND_3") (pintype "power_in"))
      (node (ref "U503") (pin "4") (pinfunction "GND_4") (pintype "bidirectional"))
      (node (ref "U504") (pin "2") (pinfunction "GND_2") (pintype "input"))
      (node (ref "U601") (pin "3") (pinfunction "P$V-_3") (pintype "bidirectional"))
      (node (ref "U602") (pin "3") (pinfunction "GND_3") (pintype "power_in"))
      (node (ref "U603") (pin "4") (pinfunction "GND_4") (pintype "bidirectional"))
      (node (ref "U604") (pin "2") (pinfunction "GND_2") (pintype "input"))
      (node (ref "U701") (pin "4") (pinfunction "GND_4") (pintype "bidirectional"))
      (node (ref "U702") (pin "4") (pinfunction "GND_4") (pintype "bidirectional"))
      (node (ref "U703") (pin "2") (pinfunction "GND_2") (pintype "input"))
      (node (ref "U801") (pin "3") (pinfunction "P$V-_3") (pintype "bidirectional"))
      (node (ref "U802") (pin "3") (pinfunction "GND_3") (pintype "power_in"))
      (node (ref "U803") (pin "2") (pinfunction "GND_2") (pintype "input"))
      (node (ref "U901") (pin "4") (pinfunction "GND_4") (pintype "bidirectional"))
      (node (ref "U902") (pin "2") (pinfunction "GND_2") (pintype "input"))
      (node (ref "X1601") (pin "2") (pinfunction "1_2") (pintype "passive"))
    )
    (net (code "45") (name "IMA0.5_IN") (class "Default")
      (node (ref "D1403") (pin "A") (pinfunction "A_A") (pintype "passive"))
      (node (ref "J1613") (pin "1") (pinfunction "1_1") (pintype "passive"))
      (node (ref "JP1401") (pin "1") (pinfunction "1_1") (pintype "passive"))
      (node (ref "U1401") (pin "2") (pinfunction "A_2") (pintype "bidirectional"))
    )
    (net (code "46") (name "IMA0.5_OUT") (class "Default")
      (node (ref "D1402") (pin "A") (pinfunction "A_A") (pintype "passive"))
      (node (ref "J1401") (pin "2") (pinfunction "2_2") (pintype "passive"))
      (node (ref "J1614") (pin "2") (pinfunction "2_2") (pintype "passive"))
      (node (ref "R1401") (pin "1") (pinfunction "1_1") (pintype "passive"))
      (node (ref "S1401") (pin "2") (pinfunction "P_2") (pintype "passive"))
    )
    (net (code "47") (name "IMA0.5_VCC") (class "Default")
      (node (ref "C1401") (pin "+") (pinfunction "+_+") (pintype "passive"))
      (node (ref "D1404") (pin "A") (pinfunction "A_A") (pintype "passive"))
      (node (ref "J1401") (pin "1") (pinfunction "1_1") (pintype "passive"))
      (node (ref "S1401") (pin "1") (pinfunction "O_1") (pintype "passive"))
      (node (ref "TP1402") (pin "TP") (pinfunction "TP_TP") (pintype "input"))
      (node (ref "U1401") (pin "5") (pinfunction "P$V+_5") (pintype "bidirectional"))
      (node (ref "U1402") (pin "5") (pinfunction "OUT_5") (pintype "passive"))
    )
    (net (code "48") (name "IMA7_IN") (class "Default")
      (node (ref "D1302") (pin "A") (pinfunction "A_A") (pintype "passive"))
      (node (ref "J1612") (pin "1") (pinfunction "1_1") (pintype "passive"))
      (node (ref "U1302") (pin "2") (pinfunction "PB3(ADC3)_2") (pintype "bidirectional"))
    )
    (net (code "49") (name "IMA7_MISO") (class "Default")
      (node (ref "J1304") (pin "1") (pinfunction "1_1") (pintype "passive"))
      (node (ref "U1301") (pin "9") (pinfunction "AIN2/EN_9") (pintype "bidirectional"))
      (node (ref "U1302") (pin "6") (pinfunction "PB1(MISO)_6") (pintype "bidirectional"))
    )
    (net (code "50") (name "IMA7_MOSI") (class "Default")
      (node (ref "J1304") (pin "4") (pinfunction "4_4") (pintype "passive"))
      (node (ref "U1301") (pin "10") (pinfunction "AIN1/PH_10") (pintype "bidirectional"))
      (node (ref "U1302") (pin "5") (pinfunction "PB0(MOSI)_5") (pintype "bidirectional"))
    )
    (net (code "51") (name "IMA7_OUT") (class "Default")
      (node (ref "D1301") (pin "A") (pinfunction "A_A") (pintype "passive"))
      (node (ref "J1301") (pin "2") (pinfunction "2_2") (pintype "passive"))
      (node (ref "J1613") (pin "2") (pinfunction "2_2") (pintype "passive"))
      (node (ref "R1301") (pin "1") (pinfunction "1_1") (pintype "passive"))
      (node (ref "S1302") (pin "2") (pinfunction "P_2") (pintype "passive"))
    )
    (net (code "52") (name "IMA7_RST") (class "Default")
      (node (ref "J1304") (pin "5") (pinfunction "5_5") (pintype "passive"))
      (node (ref "R1303") (pin "1") (pinfunction "1_1") (pintype "passive"))
      (node (ref "S1301") (pin "3") (pinfunction "2_3") (pintype "passive"))
      (node (ref "S1301") (pin "4") (pinfunction "2_4") (pintype "passive"))
      (node (ref "U1302") (pin "1") (pinfunction "PB5(NRES)_1") (pintype "bidirectional"))
    )
    (net (code "53") (name "IMA7_SCK") (class "Default")
      (node (ref "J1302") (pin "2") (pinfunction "2_2") (pintype "passive"))
      (node (ref "J1304") (pin "3") (pinfunction "3_3") (pintype "passive"))
      (node (ref "R1302") (pin "1") (pinfunction "1_1") (pintype "passive"))
      (node (ref "U1302") (pin "7") (pinfunction "PB2(SCK/ADC1)_7") (pintype "bidirectional"))
    )
    (net (code "54") (name "IMA7_VCC") (class "Default")
      (node (ref "C1301") (pin "2") (pinfunction "2_2") (pintype "passive"))
      (node (ref "C1303") (pin "1") (pinfunction "1_1") (pintype "passive"))
      (node (ref "D1303") (pin "A") (pinfunction "A_A") (pintype "passive"))
      (node (ref "IC1301") (pin "2") (pinfunction "VO_2") (pintype "passive"))
      (node (ref "J1301") (pin "1") (pinfunction "1_1") (pintype "passive"))
      (node (ref "J1302") (pin "1") (pinfunction "1_1") (pintype "passive"))
      (node (ref "J1304") (pin "2") (pinfunction "2_2") (pintype "passive"))
      (node (ref "R1303") (pin "2") (pinfunction "2_2") (pintype "passive"))
      (node (ref "S1302") (pin "1") (pinfunction "O_1") (pintype "passive"))
      (node (ref "TP1301") (pin "TP") (pinfunction "TP_TP") (pintype "input"))
      (node (ref "U1301") (pin "1") (pinfunction "VM_1") (pintype "bidirectional"))
      (node (ref "U1301") (pin "11") (pinfunction "MODE_11") (pintype "bidirectional"))
      (node (ref "U1301") (pin "12") (pinfunction "VCC_12") (pintype "bidirectional"))
      (node (ref "U1302") (pin "8") (pinfunction "VCC_8") (pintype "bidirectional"))
    )
    (net (code "55") (name "IR_1_MISO") (class "Default")
      (node (ref "J702") (pin "1") (pinfunction "1_1") (pintype "passive"))
      (node (ref "J704") (pin "1") (pinfunction "1_1") (pintype "passive"))
      (node (ref "U702") (pin "6") (pinfunction "PB1(MISO)_6") (pintype "bidirectional"))
    )
    (net (code "56") (name "IR_1_MOSI") (class "Default")
      (node (ref "J704") (pin "4") (pinfunction "4_4") (pintype "passive"))
      (node (ref "U702") (pin "5") (pinfunction "PB0(MOSI)_5") (pintype "bidirectional"))
    )
    (net (code "57") (name "IR_1_RST") (class "Default")
      (node (ref "J704") (pin "5") (pinfunction "5_5") (pintype "passive"))
      (node (ref "R704") (pin "1") (pinfunction "1_1") (pintype "passive"))
      (node (ref "S702") (pin "3") (pinfunction "2_3") (pintype "passive"))
      (node (ref "S702") (pin "4") (pinfunction "2_4") (pintype "passive"))
      (node (ref "U702") (pin "1") (pinfunction "PB5(NRES)_1") (pintype "bidirectional"))
    )
    (net (code "58") (name "IR_1_SCK") (class "Default")
      (node (ref "J704") (pin "3") (pinfunction "3_3") (pintype "passive"))
      (node (ref "U702") (pin "7") (pinfunction "PB2(SCK/ADC1)_7") (pintype "bidirectional"))
    )
    (net (code "59") (name "IR_2_MISO") (class "Default")
      (node (ref "J703") (pin "1") (pinfunction "1_1") (pintype "passive"))
      (node (ref "U701") (pin "6") (pinfunction "PB1(MISO)_6") (pintype "bidirectional"))
    )
    (net (code "60") (name "IR_2_MOSI") (class "Default")
      (node (ref "J703") (pin "4") (pinfunction "4_4") (pintype "passive"))
      (node (ref "U701") (pin "5") (pinfunction "PB0(MOSI)_5") (pintype "bidirectional"))
    )
    (net (code "61") (name "IR_2_RST") (class "Default")
      (node (ref "J703") (pin "5") (pinfunction "5_5") (pintype "passive"))
      (node (ref "R703") (pin "1") (pinfunction "1_1") (pintype "passive"))
      (node (ref "S701") (pin "3") (pinfunction "2_3") (pintype "passive"))
      (node (ref "S701") (pin "4") (pinfunction "2_4") (pintype "passive"))
      (node (ref "U701") (pin "1") (pinfunction "PB5(NRES)_1") (pintype "bidirectional"))
    )
    (net (code "62") (name "IR_2_SCK") (class "Default")
      (node (ref "J703") (pin "3") (pinfunction "3_3") (pintype "passive"))
      (node (ref "R702") (pin "1") (pinfunction "1_1") (pintype "passive"))
      (node (ref "U701") (pin "7") (pinfunction "PB2(SCK/ADC1)_7") (pintype "bidirectional"))
    )
    (net (code "63") (name "IR_IN") (class "Default")
      (node (ref "D702") (pin "A") (pinfunction "A_A") (pintype "passive"))
      (node (ref "J1606") (pin "1") (pinfunction "1_1") (pintype "passive"))
      (node (ref "U702") (pin "2") (pinfunction "PB3(ADC3)_2") (pintype "bidirectional"))
    )
    (net (code "64") (name "IR_OUT") (class "Default")
      (node (ref "D701") (pin "A") (pinfunction "A_A") (pintype "passive"))
      (node (ref "J1607") (pin "2") (pinfunction "2_2") (pintype "passive"))
      (node (ref "S703") (pin "2") (pinfunction "P_2") (pintype "passive"))
    )
    (net (code "65") (name "IR_OUT_SWITCH") (class "Default")
      (node (ref "S703") (pin "3") (pinfunction "S_3") (pintype "passive"))
      (node (ref "U701") (pin "3") (pinfunction "PB4(ADC2)_3") (pintype "bidirectional"))
    )
    (net (code "66") (name "IR_VCC") (class "Default")
      (node (ref "C701") (pin "2") (pinfunction "2_2") (pintype "passive"))
      (node (ref "C702") (pin "2") (pinfunction "2_2") (pintype "passive"))
      (node (ref "C703") (pin "+") (pinfunction "+_+") (pintype "passive"))
      (node (ref "D703") (pin "A") (pinfunction "A_A") (pintype "passive"))
      (node (ref "J701") (pin "3") (pinfunction "3_3") (pintype "passive"))
      (node (ref "J703") (pin "2") (pinfunction "2_2") (pintype "passive"))
      (node (ref "J704") (pin "2") (pinfunction "2_2") (pintype "passive"))
      (node (ref "R701") (pin "1") (pinfunction "1_1") (pintype "passive"))
      (node (ref "R703") (pin "2") (pinfunction "2_2") (pintype "passive"))
      (node (ref "R704") (pin "2") (pinfunction "2_2") (pintype "passive"))
      (node (ref "S703") (pin "1") (pinfunction "O_1") (pintype "passive"))
      (node (ref "TP701") (pin "TP") (pinfunction "TP_TP") (pintype "input"))
      (node (ref "U701") (pin "8") (pinfunction "VCC_8") (pintype "bidirectional"))
      (node (ref "U702") (pin "8") (pinfunction "VCC_8") (pintype "bidirectional"))
      (node (ref "U703") (pin "5") (pinfunction "OUT_5") (pintype "passive"))
    )
    (net (code "67") (name "LEVER_IN") (class "Default")
      (node (ref "D903") (pin "A") (pinfunction "A_A") (pintype "passive"))
      (node (ref "J1608") (pin "1") (pinfunction "1_1") (pintype "passive"))
      (node (ref "U901") (pin "2") (pinfunction "PB3(ADC3)_2") (pintype "bidirectional"))
    )
    (net (code "68") (name "LEVER_MISO") (class "Default")
      (node (ref "J903") (pin "1") (pinfunction "1_1") (pintype "passive"))
      (node (ref "U901") (pin "6") (pinfunction "PB1(MISO)_6") (pintype "bidirectional"))
    )
    (net (code "69") (name "LEVER_MOSI") (class "Default")
      (node (ref "J903") (pin "4") (pinfunction "4_4") (pintype "passive"))
      (node (ref "U901") (pin "5") (pinfunction "PB0(MOSI)_5") (pintype "bidirectional"))
    )
    (net (code "70") (name "LEVER_OUT") (class "Default")
      (node (ref "D902") (pin "A") (pinfunction "A_A") (pintype "passive"))
      (node (ref "J1609") (pin "2") (pinfunction "2_2") (pintype "passive"))
      (node (ref "J901") (pin "2") (pinfunction "2_2") (pintype "passive"))
      (node (ref "R903") (pin "1") (pinfunction "1_1") (pintype "passive"))
      (node (ref "S902") (pin "2") (pinfunction "P_2") (pintype "passive"))
    )
    (net (code "71") (name "LEVER_RST") (class "Default")
      (node (ref "J903") (pin "5") (pinfunction "5_5") (pintype "passive"))
      (node (ref "R904") (pin "1") (pinfunction "1_1") (pintype "passive"))
      (node (ref "S901") (pin "3") (pinfunction "2_3") (pintype "passive"))
      (node (ref "S901") (pin "4") (pinfunction "2_4") (pintype "passive"))
      (node (ref "U901") (pin "1") (pinfunction "PB5(NRES)_1") (pintype "bidirectional"))
    )
    (net (code "72") (name "LEVER_SCK") (class "Default")
      (node (ref "J903") (pin "3") (pinfunction "3_3") (pintype "passive"))
      (node (ref "R901") (pin "1") (pinfunction "1_1") (pintype "passive"))
      (node (ref "R902") (pin "1") (pinfunction "1_1") (pintype "passive"))
      (node (ref "U901") (pin "7") (pinfunction "PB2(SCK/ADC1)_7") (pintype "bidirectional"))
    )
    (net (code "73") (name "LEVER_VCC") (class "Default")
      (node (ref "C901") (pin "2") (pinfunction "2_2") (pintype "passive"))
      (node (ref "C902") (pin "+") (pinfunction "+_+") (pintype "passive"))
      (node (ref "D904") (pin "A") (pinfunction "A_A") (pintype "passive"))
      (node (ref "J901") (pin "1") (pinfunction "1_1") (pintype "passive"))
      (node (ref "J903") (pin "2") (pinfunction "2_2") (pintype "passive"))
      (node (ref "R904") (pin "2") (pinfunction "2_2") (pintype "passive"))
      (node (ref "S902") (pin "1") (pinfunction "O_1") (pintype "passive"))
      (node (ref "TP901") (pin "TP") (pinfunction "TP_TP") (pintype "input"))
      (node (ref "U901") (pin "8") (pinfunction "VCC_8") (pintype "bidirectional"))
      (node (ref "U902") (pin "5") (pinfunction "OUT_5") (pintype "passive"))
    )
    (net (code "74") (name "LIGHT_IN") (class "Default")
      (node (ref "D403") (pin "A") (pinfunction "A_A") (pintype "passive"))
      (node (ref "J1603") (pin "1") (pinfunction "1_1") (pintype "passive"))
      (node (ref "U402") (pin "1") (pinfunction "A_1") (pintype "input"))
    )
    (net (code "75") (name "LIGHT_MISO") (class "Default")
      (node (ref "J401") (pin "1") (pinfunction "1_1") (pintype "passive"))
      (node (ref "U403") (pin "6") (pinfunction "PB1(MISO)_6") (pintype "bidirectional"))
    )
    (net (code "76") (name "LIGHT_MOSI") (class "Default")
      (node (ref "J401") (pin "4") (pinfunction "4_4") (pintype "passive"))
      (node (ref "U403") (pin "5") (pinfunction "PB0(MOSI)_5") (pintype "bidirectional"))
    )
    (net (code "77") (name "LIGHT_OUT") (class "Default")
      (node (ref "D402") (pin "A") (pinfunction "A_A") (pintype "passive"))
      (node (ref "J1604") (pin "2") (pinfunction "2_2") (pintype "passive"))
      (node (ref "S402") (pin "2") (pinfunction "P_2") (pintype "passive"))
      (node (ref "U401") (pin "2") (pinfunction "A_2") (pintype "bidirectional"))
    )
    (net (code "78") (name "LIGHT_OUT_SWITCH") (class "Default")
      (node (ref "S402") (pin "3") (pinfunction "S_3") (pintype "passive"))
      (node (ref "U403") (pin "3") (pinfunction "PB4(ADC2)_3") (pintype "bidirectional"))
    )
    (net (code "79") (name "LIGHT_RST") (class "Default")
      (node (ref "J401") (pin "5") (pinfunction "5_5") (pintype "passive"))
      (node (ref "R405") (pin "1") (pinfunction "1_1") (pintype "passive"))
      (node (ref "S401") (pin "3") (pinfunction "2_3") (pintype "passive"))
      (node (ref "S401") (pin "4") (pinfunction "2_4") (pintype "passive"))
      (node (ref "U403") (pin "1") (pinfunction "PB5(NRES)_1") (pintype "bidirectional"))
    )
    (net (code "80") (name "LIGHT_SCK") (class "Default")
      (node (ref "J401") (pin "3") (pinfunction "3_3") (pintype "passive"))
      (node (ref "R401") (pin "2") (pinfunction "2_2") (pintype "passive"))
      (node (ref "R402") (pin "1") (pinfunction "P$1_1") (pintype "bidirectional"))
      (node (ref "U403") (pin "7") (pinfunction "PB2(SCK/ADC1)_7") (pintype "bidirectional"))
    )
    (net (code "81") (name "LIGHT_VCC") (class "Default")
      (node (ref "C401") (pin "2") (pinfunction "2_2") (pintype "passive"))
      (node (ref "C402") (pin "+") (pinfunction "+_+") (pintype "passive"))
      (node (ref "D404") (pin "A") (pinfunction "A_A") (pintype "passive"))
      (node (ref "J401") (pin "2") (pinfunction "2_2") (pintype "passive"))
      (node (ref "Q401") (pin "3") (pinfunction "C_3") (pintype "passive"))
      (node (ref "R402") (pin "2") (pinfunction "P$2_2") (pintype "bidirectional"))
      (node (ref "R405") (pin "2") (pinfunction "2_2") (pintype "passive"))
      (node (ref "S402") (pin "1") (pinfunction "O_1") (pintype "passive"))
      (node (ref "TP403") (pin "TP") (pinfunction "TP_TP") (pintype "input"))
      (node (ref "U401") (pin "5") (pinfunction "P$V+_5") (pintype "bidirectional"))
      (node (ref "U402") (pin "5") (pinfunction "VCC_5") (pintype "power_in"))
      (node (ref "U403") (pin "8") (pinfunction "VCC_8") (pintype "bidirectional"))
      (node (ref "U404") (pin "5") (pinfunction "OUT_5") (pintype "passive"))
    )
    (net (code "82") (name "Net-(D101-PadC)") (class "Default")
      (node (ref "D101") (pin "C") (pinfunction "C_C") (pintype "passive"))
      (node (ref "R102") (pin "2") (pinfunction "2_2") (pintype "passive"))
    )
    (net (code "83") (name "Net-(D102-PadC)") (class "Default")
      (node (ref "D102") (pin "C") (pinfunction "C_C") (pintype "passive"))
      (node (ref "R103") (pin "2") (pinfunction "2_2") (pintype "passive"))
    )
    (net (code "84") (name "Net-(D202-PadC)") (class "Default")
      (node (ref "D202") (pin "C") (pinfunction "C_C") (pintype "passive"))
      (node (ref "R205") (pin "2") (pinfunction "2_2") (pintype "passive"))
    )
    (net (code "85") (name "Net-(D203-PadC)") (class "Default")
      (node (ref "D203") (pin "C") (pinfunction "C_C") (pintype "passive"))
      (node (ref "R206") (pin "2") (pinfunction "2_2") (pintype "passive"))
    )
    (net (code "86") (name "Net-(D204-PadC)") (class "Default")
      (node (ref "D204") (pin "C") (pinfunction "C_C") (pintype "passive"))
      (node (ref "R207") (pin "2") (pinfunction "2_2") (pintype "passive"))
    )
    (net (code "87") (name "Net-(D302-PadC)") (class "Default")
      (node (ref "D302") (pin "C") (pinfunction "C_C") (pintype "passive"))
      (node (ref "R305") (pin "2") (pinfunction "2_2") (pintype "passive"))
    )
    (net (code "88") (name "Net-(D303-PadC)") (class "Default")
      (node (ref "D303") (pin "C") (pinfunction "C_C") (pintype "passive"))
      (node (ref "R306") (pin "2") (pinfunction "2_2") (pintype "passive"))
    )
    (net (code "89") (name "Net-(D304-PadC)") (class "Default")
      (node (ref "D304") (pin "C") (pinfunction "C_C") (pintype "passive"))
      (node (ref "R307") (pin "2") (pinfunction "2_2") (pintype "passive"))
    )
    (net (code "90") (name "Net-(D401-C)") (class "Default")
      (node (ref "D401") (pin "K") (pinfunction "C_K") (pintype "passive"))
      (node (ref "R404") (pin "1") (pinfunction "1_1") (pintype "passive"))
    )
    (net (code "91") (name "Net-(D402-PadC)") (class "Default")
      (node (ref "D402") (pin "C") (pinfunction "C_C") (pintype "passive"))
      (node (ref "R406") (pin "2") (pinfunction "2_2") (pintype "passive"))
    )
    (net (code "92") (name "Net-(D403-PadC)") (class "Default")
      (node (ref "D403") (pin "C") (pinfunction "C_C") (pintype "passive"))
      (node (ref "R407") (pin "2") (pinfunction "2_2") (pintype "passive"))
    )
    (net (code "93") (name "Net-(D404-PadC)") (class "Default")
      (node (ref "D404") (pin "C") (pinfunction "C_C") (pintype "passive"))
      (node (ref "R408") (pin "2") (pinfunction "2_2") (pintype "passive"))
    )
    (net (code "94") (name "Net-(D502-PadC)") (class "Default")
      (node (ref "D502") (pin "C") (pinfunction "C_C") (pintype "passive"))
      (node (ref "R505") (pin "2") (pinfunction "2_2") (pintype "passive"))
    )
    (net (code "95") (name "Net-(D503-PadC)") (class "Default")
      (node (ref "D503") (pin "C") (pinfunction "C_C") (pintype "passive"))
      (node (ref "R506") (pin "2") (pinfunction "2_2") (pintype "passive"))
    )
    (net (code "96") (name "Net-(D504-PadC)") (class "Default")
      (node (ref "D504") (pin "C") (pinfunction "C_C") (pintype "passive"))
      (node (ref "R507") (pin "2") (pinfunction "2_2") (pintype "passive"))
    )
    (net (code "97") (name "Net-(D602-PadC)") (class "Default")
      (node (ref "D602") (pin "C") (pinfunction "C_C") (pintype "passive"))
      (node (ref "R605") (pin "2") (pinfunction "2_2") (pintype "passive"))
    )
    (net (code "98") (name "Net-(D603-PadC)") (class "Default")
      (node (ref "D603") (pin "C") (pinfunction "C_C") (pintype "passive"))
      (node (ref "R606") (pin "2") (pinfunction "2_2") (pintype "passive"))
    )
    (net (code "99") (name "Net-(D604-PadC)") (class "Default")
      (node (ref "D604") (pin "C") (pinfunction "C_C") (pintype "passive"))
      (node (ref "R607") (pin "2") (pinfunction "2_2") (pintype "passive"))
    )
    (net (code "100") (name "Net-(D701-PadC)") (class "Default")
      (node (ref "D701") (pin "C") (pinfunction "C_C") (pintype "passive"))
      (node (ref "R705") (pin "2") (pinfunction "2_2") (pintype "passive"))
    )
    (net (code "101") (name "Net-(D702-PadC)") (class "Default")
      (node (ref "D702") (pin "C") (pinfunction "C_C") (pintype "passive"))
      (node (ref "R706") (pin "2") (pinfunction "2_2") (pintype "passive"))
    )
    (net (code "102") (name "Net-(D703-PadC)") (class "Default")
      (node (ref "D703") (pin "C") (pinfunction "C_C") (pintype "passive"))
      (node (ref "R707") (pin "2") (pinfunction "2_2") (pintype "passive"))
    )
    (net (code "103") (name "Net-(D802-PadC)") (class "Default")
      (node (ref "D802") (pin "C") (pinfunction "C_C") (pintype "passive"))
      (node (ref "R804") (pin "2") (pinfunction "2_2") (pintype "passive"))
    )
    (net (code "104") (name "Net-(D803-PadC)") (class "Default")
      (node (ref "D803") (pin "C") (pinfunction "C_C") (pintype "passive"))
      (node (ref "R805") (pin "2") (pinfunction "2_2") (pintype "passive"))
    )
    (net (code "105") (name "Net-(D804-PadC)") (class "Default")
      (node (ref "D804") (pin "C") (pinfunction "C_C") (pintype "passive"))
      (node (ref "R806") (pin "2") (pinfunction "2_2") (pintype "passive"))
    )
    (net (code "106") (name "Net-(D902-PadC)") (class "Default")
      (node (ref "D902") (pin "C") (pinfunction "C_C") (pintype "passive"))
      (node (ref "R905") (pin "2") (pinfunction "2_2") (pintype "passive"))
    )
    (net (code "107") (name "Net-(D903-PadC)") (class "Default")
      (node (ref "D903") (pin "C") (pinfunction "C_C") (pintype "passive"))
      (node (ref "R906") (pin "2") (pinfunction "2_2") (pintype "passive"))
    )
    (net (code "108") (name "Net-(D904-PadC)") (class "Default")
      (node (ref "D904") (pin "C") (pinfunction "C_C") (pintype "passive"))
      (node (ref "R907") (pin "2") (pinfunction "2_2") (pintype "passive"))
    )
    (net (code "109") (name "Net-(D1002-PadC)") (class "Default")
      (node (ref "D1002") (pin "C") (pinfunction "C_C") (pintype "passive"))
      (node (ref "R1006") (pin "2") (pinfunction "2_2") (pintype "passive"))
    )
    (net (code "110") (name "Net-(D1003-PadC)") (class "Default")
      (node (ref "D1003") (pin "C") (pinfunction "C_C") (pintype "passive"))
      (node (ref "R1007") (pin "2") (pinfunction "2_2") (pintype "passive"))
    )
    (net (code "111") (name "Net-(D1004-PadC)") (class "Default")
      (node (ref "D1004") (pin "C") (pinfunction "C_C") (pintype "passive"))
      (node (ref "R1008") (pin "2") (pinfunction "2_2") (pintype "passive"))
    )
    (net (code "112") (name "Net-(D1101-PadC)") (class "Default")
      (node (ref "D1101") (pin "C") (pinfunction "C_C") (pintype "passive"))
      (node (ref "R1104") (pin "2") (pinfunction "2_2") (pintype "passive"))
    )
    (net (code "113") (name "Net-(D1102-PadC)") (class "Default")
      (node (ref "D1102") (pin "C") (pinfunction "C_C") (pintype "passive"))
      (node (ref "R1105") (pin "2") (pinfunction "2_2") (pintype "passive"))
    )
    (net (code "114") (name "Net-(D1103-PadC)") (class "Default")
      (node (ref "D1103") (pin "C") (pinfunction "C_C") (pintype "passive"))
      (node (ref "R1106") (pin "2") (pinfunction "2_2") (pintype "passive"))
    )
    (net (code "115") (name "Net-(D1201-PadC)") (class "Default")
      (node (ref "D1201") (pin "C") (pinfunction "C_C") (pintype "passive"))
      (node (ref "R1204") (pin "2") (pinfunction "2_2") (pintype "passive"))
    )
    (net (code "116") (name "Net-(D1202-PadC)") (class "Default")
      (node (ref "D1202") (pin "C") (pinfunction "C_C") (pintype "passive"))
      (node (ref "R1205") (pin "2") (pinfunction "2_2") (pintype "passive"))
    )
    (net (code "117") (name "Net-(D1203-PadC)") (class "Default")
      (node (ref "D1203") (pin "C") (pinfunction "C_C") (pintype "passive"))
      (node (ref "R1206") (pin "2") (pinfunction "2_2") (pintype "passive"))
    )
    (net (code "118") (name "Net-(D1301-PadC)") (class "Default")
      (node (ref "D1301") (pin "C") (pinfunction "C_C") (pintype "passive"))
      (node (ref "R1304") (pin "2") (pinfunction "2_2") (pintype "passive"))
    )
    (net (code "119") (name "Net-(D1302-PadC)") (class "Default")
      (node (ref "D1302") (pin "C") (pinfunction "C_C") (pintype "passive"))
      (node (ref "R1305") (pin "2") (pinfunction "2_2") (pintype "passive"))
    )
    (net (code "120") (name "Net-(D1303-PadC)") (class "Default")
      (node (ref "D1303") (pin "C") (pinfunction "C_C") (pintype "passive"))
      (node (ref "R1306") (pin "2") (pinfunction "2_2") (pintype "passive"))
    )
    (net (code "121") (name "Net-(D1402-PadC)") (class "Default")
      (node (ref "D1402") (pin "C") (pinfunction "C_C") (pintype "passive"))
      (node (ref "R1404") (pin "2") (pinfunction "2_2") (pintype "passive"))
    )
    (net (code "122") (name "Net-(D1403-PadC)") (class "Default")
      (node (ref "D1403") (pin "C") (pinfunction "C_C") (pintype "passive"))
      (node (ref "R1405") (pin "2") (pinfunction "2_2") (pintype "passive"))
    )
    (net (code "123") (name "Net-(D1404-PadC)") (class "Default")
      (node (ref "D1404") (pin "C") (pinfunction "C_C") (pintype "passive"))
      (node (ref "R1406") (pin "2") (pinfunction "2_2") (pintype "passive"))
    )
    (net (code "124") (name "Net-(D1501-PadC)") (class "Default")
      (node (ref "D1501") (pin "C") (pinfunction "C_C") (pintype "passive"))
      (node (ref "R1502") (pin "2") (pinfunction "2_2") (pintype "passive"))
    )
    (net (code "125") (name "Net-(D1502-PadC)") (class "Default")
      (node (ref "D1502") (pin "C") (pinfunction "C_C") (pintype "passive"))
      (node (ref "R1503") (pin "2") (pinfunction "2_2") (pintype "passive"))
    )
    (net (code "126") (name "Net-(J501-Pad1)") (class "Default")
      (node (ref "J501") (pin "1") (pinfunction "1_1") (pintype "passive"))
      (node (ref "R501") (pin "1") (pinfunction "1_1") (pintype "passive"))
    )
    (net (code "127") (name "Net-(J701-Pad1)") (class "Default")
      (node (ref "J701") (pin "1") (pinfunction "1_1") (pintype "passive"))
      (node (ref "R702") (pin "2") (pinfunction "2_2") (pintype "passive"))
    )
    (net (code "128") (name "Net-(J702-Pad2)") (class "Default")
      (node (ref "J702") (pin "2") (pinfunction "2_2") (pintype "passive"))
      (node (ref "R701") (pin "2") (pinfunction "2_2") (pintype "passive"))
    )
    (net (code "129") (name "Net-(J1002-Pad1)") (class "Default")
      (node (ref "J1002") (pin "1") (pinfunction "1_1") (pintype "passive"))
      (node (ref "R1003") (pin "1") (pinfunction "1_1") (pintype "passive"))
    )
    (net (code "130") (name "Net-(JP201-Pad2)") (class "Default")
      (node (ref "JP201") (pin "2") (pinfunction "2_2") (pintype "passive"))
      (node (ref "JP202") (pin "2") (pinfunction "2_2") (pintype "passive"))
      (node (ref "R201") (pin "1") (pinfunction "1_1") (pintype "passive"))
      (node (ref "R202") (pin "1") (pinfunction "1_1") (pintype "passive"))
      (node (ref "TP201") (pin "TP") (pinfunction "TP_TP") (pintype "input"))
    )
    (net (code "131") (name "Net-(JP1401-Pad2)") (class "Default")
      (node (ref "JP1401") (pin "2") (pinfunction "2_2") (pintype "passive"))
      (node (ref "JP1402") (pin "2") (pinfunction "2_2") (pintype "passive"))
      (node (ref "R1402") (pin "1") (pinfunction "1_1") (pintype "passive"))
      (node (ref "R1403") (pin "1") (pinfunction "1_1") (pintype "passive"))
      (node (ref "TP1401") (pin "TP") (pinfunction "TP_TP") (pintype "input"))
    )
    (net (code "132") (name "Net-(Q201-D)") (class "Default")
      (node (ref "D201") (pin "A") (pinfunction "A_A") (pintype "passive"))
      (node (ref "J203") (pin "2") (pinfunction "2_2") (pintype "passive"))
      (node (ref "Q201") (pin "MB") (pinfunction "D_MB") (pintype "passive"))
    )
    (net (code "133") (name "Net-(Q201-G)") (class "Default")
      (node (ref "Q201") (pin "4") (pinfunction "G_4") (pintype "passive"))
      (node (ref "R201") (pin "2") (pinfunction "2_2") (pintype "passive"))
    )
    (net (code "134") (name "Net-(Q301-B)") (class "Default")
      (node (ref "Q301") (pin "1") (pinfunction "B_1") (pintype "passive"))
      (node (ref "R302") (pin "2") (pinfunction "2_2") (pintype "passive"))
    )
    (net (code "135") (name "Net-(Q301-E)") (class "Default")
      (node (ref "D301") (pin "A") (pinfunction "A_A") (pintype "passive"))
      (node (ref "Q301") (pin "2") (pinfunction "E_2") (pintype "passive"))
    )
    (net (code "136") (name "Net-(Q401-B)") (class "Default")
      (node (ref "Q401") (pin "1") (pinfunction "B_1") (pintype "passive"))
      (node (ref "R403") (pin "2") (pinfunction "2_2") (pintype "passive"))
    )
    (net (code "137") (name "Net-(Q401-E)") (class "Default")
      (node (ref "D401") (pin "A") (pinfunction "A_A") (pintype "passive"))
      (node (ref "Q401") (pin "2") (pinfunction "E_2") (pintype "passive"))
    )
    (net (code "138") (name "Net-(Q501-D)") (class "Default")
      (node (ref "D501") (pin "A") (pinfunction "A_A") (pintype "passive"))
      (node (ref "J502") (pin "2") (pinfunction "2_2") (pintype "passive"))
      (node (ref "Q501") (pin "MB") (pinfunction "D_MB") (pintype "passive"))
    )
    (net (code "139") (name "Net-(Q501-G)") (class "Default")
      (node (ref "Q501") (pin "4") (pinfunction "G_4") (pintype "passive"))
      (node (ref "R502") (pin "2") (pinfunction "2_2") (pintype "passive"))
    )
    (net (code "140") (name "Net-(Q601-D)") (class "Default")
      (node (ref "D601") (pin "A") (pinfunction "A_A") (pintype "passive"))
      (node (ref "J602") (pin "2") (pinfunction "2_2") (pintype "passive"))
      (node (ref "Q601") (pin "MB") (pinfunction "D_MB") (pintype "passive"))
    )
    (net (code "141") (name "Net-(Q601-G)") (class "Default")
      (node (ref "Q601") (pin "4") (pinfunction "G_4") (pintype "passive"))
      (node (ref "R601") (pin "2") (pinfunction "2_2") (pintype "passive"))
    )
    (net (code "142") (name "Net-(Q801-D)") (class "Default")
      (node (ref "D801") (pin "A") (pinfunction "A_A") (pintype "passive"))
      (node (ref "J802") (pin "2") (pinfunction "2_2") (pintype "passive"))
      (node (ref "Q801") (pin "MB") (pinfunction "D_MB") (pintype "passive"))
    )
    (net (code "143") (name "Net-(Q801-G)") (class "Default")
      (node (ref "Q801") (pin "4") (pinfunction "G_4") (pintype "passive"))
      (node (ref "R802") (pin "2") (pinfunction "2_2") (pintype "passive"))
    )
    (net (code "144") (name "Net-(Q901-D)") (class "Default")
      (node (ref "D901") (pin "A") (pinfunction "A_A") (pintype "passive"))
      (node (ref "J902") (pin "2") (pinfunction "2_2") (pintype "passive"))
      (node (ref "Q901") (pin "MB") (pinfunction "D_MB") (pintype "passive"))
    )
    (net (code "145") (name "Net-(Q901-G)") (class "Default")
      (node (ref "Q901") (pin "4") (pinfunction "G_4") (pintype "passive"))
      (node (ref "R901") (pin "2") (pinfunction "2_2") (pintype "passive"))
    )
    (net (code "146") (name "Net-(Q1001-D)") (class "Default")
      (node (ref "D1001") (pin "A") (pinfunction "A_A") (pintype "passive"))
      (node (ref "J1001") (pin "2") (pinfunction "2_2") (pintype "passive"))
      (node (ref "Q1001") (pin "MB") (pinfunction "D_MB") (pintype "passive"))
    )
    (net (code "147") (name "Net-(Q1001-G)") (class "Default")
      (node (ref "Q1001") (pin "4") (pinfunction "G_4") (pintype "passive"))
      (node (ref "R1001") (pin "2") (pinfunction "2_2") (pintype "passive"))
    )
    (net (code "148") (name "Net-(Q1401-D)") (class "Default")
      (node (ref "D1401") (pin "A") (pinfunction "A_A") (pintype "passive"))
      (node (ref "J1402") (pin "2") (pinfunction "2_2") (pintype "passive"))
      (node (ref "Q1401") (pin "MB") (pinfunction "D_MB") (pintype "passive"))
    )
    (net (code "149") (name "Net-(Q1401-G)") (class "Default")
      (node (ref "Q1401") (pin "4") (pinfunction "G_4") (pintype "passive"))
      (node (ref "R1402") (pin "2") (pinfunction "2_2") (pintype "passive"))
    )
    (net (code "150") (name "Net-(S101-2)") (class "Default")
      (node (ref "JP101") (pin "1") (pinfunction "1_1") (pintype "passive"))
      (node (ref "R101") (pin "2") (pinfunction "2_2") (pintype "passive"))
      (node (ref "S101") (pin "P$2") (pinfunction "2_P$2") (pintype "passive"))
      (node (ref "U101") (pin "2") (pinfunction "A_2") (pintype "bidirectional"))
    )
    (net (code "151") (name "Net-(U101A-Y)") (class "Default")
      (node (ref "JP102") (pin "1") (pinfunction "1_1") (pintype "passive"))
      (node (ref "U101") (pin "4") (pinfunction "Y_4") (pintype "bidirectional"))
    )
    (net (code "152") (name "Net-(U201A-Y)") (class "Default")
      (node (ref "JP202") (pin "1") (pinfunction "1_1") (pintype "passive"))
      (node (ref "U201") (pin "4") (pinfunction "Y_4") (pintype "bidirectional"))
    )
    (net (code "153") (name "Net-(U202-PB3(ADC3))") (class "Default")
      (node (ref "TP203") (pin "TP") (pinfunction "TP_TP") (pintype "input"))
      (node (ref "U202") (pin "2") (pinfunction "PB3(ADC3)_2") (pintype "bidirectional"))
    )
    (net (code "154") (name "Net-(U301A-Y)") (class "Default")
      (node (ref "TP301") (pin "TP") (pinfunction "TP_TP") (pintype "input"))
      (node (ref "U301") (pin "4") (pinfunction "Y_4") (pintype "bidirectional"))
      (node (ref "U302") (pin "2") (pinfunction "B_2") (pintype "input"))
    )
    (net (code "155") (name "Net-(U302A-Y)") (class "Default")
      (node (ref "R302") (pin "1") (pinfunction "1_1") (pintype "passive"))
      (node (ref "TP302") (pin "TP") (pinfunction "TP_TP") (pintype "input"))
      (node (ref "U302") (pin "4") (pinfunction "Y_4") (pintype "output"))
    )
    (net (code "156") (name "Net-(U303-PB3(ADC3))") (class "Default")
      (node (ref "TP303") (pin "TP") (pinfunction "TP_TP") (pintype "input"))
      (node (ref "U303") (pin "2") (pinfunction "PB3(ADC3)_2") (pintype "bidirectional"))
    )
    (net (code "157") (name "Net-(U401A-Y)") (class "Default")
      (node (ref "TP401") (pin "TP") (pinfunction "TP_TP") (pintype "input"))
      (node (ref "U401") (pin "4") (pinfunction "Y_4") (pintype "bidirectional"))
      (node (ref "U402") (pin "2") (pinfunction "B_2") (pintype "input"))
    )
    (net (code "158") (name "Net-(U402A-Y)") (class "Default")
      (node (ref "R403") (pin "1") (pinfunction "1_1") (pintype "passive"))
      (node (ref "TP402") (pin "TP") (pinfunction "TP_TP") (pintype "input"))
      (node (ref "U402") (pin "4") (pinfunction "Y_4") (pintype "output"))
    )
    (net (code "159") (name "Net-(U403-PB3(ADC3))") (class "Default")
      (node (ref "TP404") (pin "TP") (pinfunction "TP_TP") (pintype "input"))
      (node (ref "U403") (pin "2") (pinfunction "PB3(ADC3)_2") (pintype "bidirectional"))
    )
    (net (code "160") (name "Net-(U501A-Y)") (class "Default")
      (node (ref "TP501") (pin "TP") (pinfunction "TP_TP") (pintype "input"))
      (node (ref "U501") (pin "4") (pinfunction "Y_4") (pintype "bidirectional"))
      (node (ref "U502") (pin "2") (pinfunction "B_2") (pintype "input"))
    )
    (net (code "161") (name "Net-(U502A-Y)") (class "Default")
      (node (ref "R502") (pin "1") (pinfunction "1_1") (pintype "passive"))
      (node (ref "R503") (pin "1") (pinfunction "1_1") (pintype "passive"))
      (node (ref "TP502") (pin "TP") (pinfunction "TP_TP") (pintype "input"))
      (node (ref "U502") (pin "4") (pinfunction "Y_4") (pintype "output"))
    )
    (net (code "162") (name "Net-(U503-PB3(ADC3))") (class "Default")
      (node (ref "TP504") (pin "TP") (pinfunction "TP_TP") (pintype "input"))
      (node (ref "U503") (pin "2") (pinfunction "PB3(ADC3)_2") (pintype "bidirectional"))
    )
    (net (code "163") (name "Net-(U601A-Y)") (class "Default")
      (node (ref "TP602") (pin "TP") (pinfunction "TP_TP") (pintype "input"))
      (node (ref "U601") (pin "4") (pinfunction "Y_4") (pintype "bidirectional"))
      (node (ref "U602") (pin "2") (pinfunction "B_2") (pintype "input"))
    )
    (net (code "164") (name "Net-(U602A-Y)") (class "Default")
      (node (ref "R601") (pin "1") (pinfunction "1_1") (pintype "passive"))
      (node (ref "R602") (pin "1") (pinfunction "1_1") (pintype "passive"))
      (node (ref "TP603") (pin "TP") (pinfunction "TP_TP") (pintype "input"))
      (node (ref "U602") (pin "4") (pinfunction "Y_4") (pintype "output"))
    )
    (net (code "165") (name "Net-(U603-PB3(ADC3))") (class "Default")
      (node (ref "TP604") (pin "TP") (pinfunction "TP_TP") (pintype "input"))
      (node (ref "U603") (pin "2") (pinfunction "PB3(ADC3)_2") (pintype "bidirectional"))
    )
    (net (code "166") (name "Net-(U701-PB3(ADC3))") (class "Default")
      (node (ref "TP702") (pin "TP") (pinfunction "TP_TP") (pintype "input"))
      (node (ref "U701") (pin "2") (pinfunction "PB3(ADC3)_2") (pintype "bidirectional"))
    )
    (net (code "167") (name "Net-(U702-PB4(ADC2))") (class "Default")
      (node (ref "TP703") (pin "TP") (pinfunction "TP_TP") (pintype "input"))
      (node (ref "U702") (pin "3") (pinfunction "PB4(ADC2)_3") (pintype "bidirectional"))
    )
    (net (code "168") (name "Net-(U801A-Y)") (class "Default")
      (node (ref "TP802") (pin "TP") (pinfunction "TP_TP") (pintype "input"))
      (node (ref "U801") (pin "4") (pinfunction "Y_4") (pintype "bidirectional"))
      (node (ref "U802") (pin "2") (pinfunction "B_2") (pintype "input"))
    )
    (net (code "169") (name "Net-(U802A-Y)") (class "Default")
      (node (ref "R802") (pin "1") (pinfunction "1_1") (pintype "passive"))
      (node (ref "R803") (pin "1") (pinfunction "1_1") (pintype "passive"))
      (node (ref "TP803") (pin "TP") (pinfunction "TP_TP") (pintype "input"))
      (node (ref "U802") (pin "4") (pinfunction "Y_4") (pintype "output"))
    )
    (net (code "170") (name "Net-(U901-PB4(ADC2))") (class "Default")
      (node (ref "TP902") (pin "TP") (pinfunction "TP_TP") (pintype "input"))
      (node (ref "U901") (pin "3") (pinfunction "PB4(ADC2)_3") (pintype "bidirectional"))
    )
    (net (code "171") (name "Net-(U1001-PB4(ADC2))") (class "Default")
      (node (ref "TP1002") (pin "TP") (pinfunction "TP_TP") (pintype "input"))
      (node (ref "U1001") (pin "3") (pinfunction "PB4(ADC2)_3") (pintype "bidirectional"))
    )
    (net (code "172") (name "Net-(U1101-AOUT1)") (class "Default")
      (node (ref "J1102") (pin "1") (pinfunction "1_1") (pintype "passive"))
      (node (ref "U1101") (pin "2") (pinfunction "AOUT1_2") (pintype "bidirectional"))
    )
    (net (code "173") (name "Net-(U1101-AOUT2)") (class "Default")
      (node (ref "J1102") (pin "2") (pinfunction "2_2") (pintype "passive"))
      (node (ref "U1101") (pin "3") (pinfunction "AOUT2_3") (pintype "bidirectional"))
    )
    (net (code "174") (name "Net-(U1102-PB4(ADC2))") (class "Default")
      (node (ref "TP1102") (pin "TP") (pinfunction "TP_TP") (pintype "input"))
      (node (ref "U1102") (pin "3") (pinfunction "PB4(ADC2)_3") (pintype "bidirectional"))
    )
    (net (code "175") (name "Net-(U1201-AOUT1)") (class "Default")
      (node (ref "J1203") (pin "1") (pinfunction "1_1") (pintype "passive"))
      (node (ref "U1201") (pin "2") (pinfunction "AOUT1_2") (pintype "bidirectional"))
    )
    (net (code "176") (name "Net-(U1201-AOUT2)") (class "Default")
      (node (ref "J1203") (pin "2") (pinfunction "2_2") (pintype "passive"))
      (node (ref "U1201") (pin "3") (pinfunction "AOUT2_3") (pintype "bidirectional"))
    )
    (net (code "177") (name "Net-(U1202-PB4(ADC2))") (class "Default")
      (node (ref "TP1202") (pin "TP") (pinfunction "TP_TP") (pintype "input"))
      (node (ref "U1202") (pin "3") (pinfunction "PB4(ADC2)_3") (pintype "bidirectional"))
    )
    (net (code "178") (name "Net-(U1301-AOUT1)") (class "Default")
      (node (ref "J1303") (pin "1") (pinfunction "1_1") (pintype "passive"))
      (node (ref "U1301") (pin "2") (pinfunction "AOUT1_2") (pintype "bidirectional"))
    )
    (net (code "179") (name "Net-(U1301-AOUT2)") (class "Default")
      (node (ref "J1303") (pin "2") (pinfunction "2_2") (pintype "passive"))
      (node (ref "U1301") (pin "3") (pinfunction "AOUT2_3") (pintype "bidirectional"))
    )
    (net (code "180") (name "Net-(U1302-PB4(ADC2))") (class "Default")
      (node (ref "TP1302") (pin "TP") (pinfunction "TP_TP") (pintype "input"))
      (node (ref "U1302") (pin "3") (pinfunction "PB4(ADC2)_3") (pintype "bidirectional"))
    )
    (net (code "181") (name "Net-(U1401A-Y)") (class "Default")
      (node (ref "JP1402") (pin "1") (pinfunction "1_1") (pintype "passive"))
      (node (ref "U1401") (pin "4") (pinfunction "Y_4") (pintype "bidirectional"))
    )
    (net (code "182") (name "START_OUT") (class "Default")
      (node (ref "D101") (pin "A") (pinfunction "A_A") (pintype "passive"))
      (node (ref "J1601") (pin "2") (pinfunction "2_2") (pintype "passive"))
      (node (ref "JP101") (pin "2") (pinfunction "2_2") (pintype "passive"))
      (node (ref "JP102") (pin "2") (pinfunction "2_2") (pintype "passive"))
      (node (ref "S102") (pin "2") (pinfunction "P_2") (pintype "passive"))
    )
    (net (code "183") (name "START_VCC") (class "Default")
      (node (ref "C101") (pin "+") (pinfunction "+_+") (pintype "passive"))
      (node (ref "D102") (pin "A") (pinfunction "A_A") (pintype "passive"))
      (node (ref "R101") (pin "1") (pinfunction "1_1") (pintype "passive"))
      (node (ref "S102") (pin "1") (pinfunction "O_1") (pintype "passive"))
      (node (ref "TP101") (pin "TP") (pinfunction "TP_TP") (pintype "input"))
      (node (ref "U101") (pin "5") (pinfunction "P$V+_5") (pintype "bidirectional"))
      (node (ref "U102") (pin "5") (pinfunction "OUT_5") (pintype "passive"))
    )
    (net (code "184") (name "TIMER_IN") (class "Default")
      (node (ref "D1102") (pin "A") (pinfunction "A_A") (pintype "passive"))
      (node (ref "J1610") (pin "1") (pinfunction "1_1") (pintype "passive"))
      (node (ref "U1102") (pin "2") (pinfunction "PB3(ADC3)_2") (pintype "bidirectional"))
    )
    (net (code "185") (name "TIMER_MISO") (class "Default")
      (node (ref "J1104") (pin "1") (pinfunction "1_1") (pintype "passive"))
      (node (ref "U1101") (pin "9") (pinfunction "AIN2/EN_9") (pintype "bidirectional"))
      (node (ref "U1102") (pin "6") (pinfunction "PB1(MISO)_6") (pintype "bidirectional"))
    )
    (net (code "186") (name "TIMER_MOSI") (class "Default")
      (node (ref "J1104") (pin "4") (pinfunction "4_4") (pintype "passive"))
      (node (ref "U1101") (pin "10") (pinfunction "AIN1/PH_10") (pintype "bidirectional"))
      (node (ref "U1102") (pin "5") (pinfunction "PB0(MOSI)_5") (pintype "bidirectional"))
    )
    (net (code "187") (name "TIMER_OUT") (class "Default")
      (node (ref "D1101") (pin "A") (pinfunction "A_A") (pintype "passive"))
      (node (ref "J1101") (pin "2") (pinfunction "2_2") (pintype "passive"))
      (node (ref "J1611") (pin "2") (pinfunction "2_2") (pintype "passive"))
      (node (ref "R1101") (pin "1") (pinfunction "1_1") (pintype "passive"))
      (node (ref "S1102") (pin "2") (pinfunction "P_2") (pintype "passive"))
    )
    (net (code "188") (name "TIMER_RST") (class "Default")
      (node (ref "J1104") (pin "5") (pinfunction "5_5") (pintype "passive"))
      (node (ref "R1103") (pin "1") (pinfunction "1_1") (pintype "passive"))
      (node (ref "S1101") (pin "3") (pinfunction "2_3") (pintype "passive"))
      (node (ref "S1101") (pin "4") (pinfunction "2_4") (pintype "passive"))
      (node (ref "U1102") (pin "1") (pinfunction "PB5(NRES)_1") (pintype "bidirectional"))
    )
    (net (code "189") (name "TIMER_SCK") (class "Default")
      (node (ref "J1103") (pin "2") (pinfunction "2_2") (pintype "passive"))
      (node (ref "J1104") (pin "3") (pinfunction "3_3") (pintype "passive"))
      (node (ref "R1102") (pin "1") (pinfunction "1_1") (pintype "passive"))
      (node (ref "U1102") (pin "7") (pinfunction "PB2(SCK/ADC1)_7") (pintype "bidirectional"))
    )
    (net (code "190") (name "TIMER_VCC") (class "Default")
      (node (ref "C1101") (pin "2") (pinfunction "2_2") (pintype "passive"))
      (node (ref "C1103") (pin "1") (pinfunction "1_1") (pintype "passive"))
      (node (ref "D1103") (pin "A") (pinfunction "A_A") (pintype "passive"))
      (node (ref "IC1101") (pin "2") (pinfunction "VO_2") (pintype "passive"))
      (node (ref "J1101") (pin "1") (pinfunction "1_1") (pintype "passive"))
      (node (ref "J1103") (pin "1") (pinfunction "1_1") (pintype "passive"))
      (node (ref "J1104") (pin "2") (pinfunction "2_2") (pintype "passive"))
      (node (ref "R1103") (pin "2") (pinfunction "2_2") (pintype "passive"))
      (node (ref "S1102") (pin "1") (pinfunction "O_1") (pintype "passive"))
      (node (ref "TP1101") (pin "TP") (pinfunction "TP_TP") (pintype "input"))
      (node (ref "U1101") (pin "1") (pinfunction "VM_1") (pintype "bidirectional"))
      (node (ref "U1101") (pin "11") (pinfunction "MODE_11") (pintype "bidirectional"))
      (node (ref "U1101") (pin "12") (pinfunction "VCC_12") (pintype "bidirectional"))
      (node (ref "U1102") (pin "8") (pinfunction "VCC_8") (pintype "bidirectional"))
    )
    (net (code "191") (name "V_BATT") (class "Default")
      (node (ref "C1102") (pin "2") (pinfunction "2_2") (pintype "passive"))
      (node (ref "C1202") (pin "2") (pinfunction "2_2") (pintype "passive"))
      (node (ref "C1302") (pin "2") (pinfunction "2_2") (pintype "passive"))
      (node (ref "C1501") (pin "2") (pinfunction "2_2") (pintype "passive"))
      (node (ref "C1601") (pin "+") (pinfunction "+_+") (pintype "passive"))
      (node (ref "C1602") (pin "+") (pinfunction "+_+") (pintype "passive"))
      (node (ref "C1603") (pin "+") (pinfunction "+_+") (pintype "passive"))
      (node (ref "C1604") (pin "1") (pinfunction "1_1") (pintype "passive"))
      (node (ref "D1001") (pin "C") (pinfunction "C_C") (pintype "passive"))
      (node (ref "D1401") (pin "C") (pinfunction "C_C") (pintype "passive"))
      (node (ref "D1601") (pin "C") (pinfunction "C_C") (pintype "passive"))
      (node (ref "D201") (pin "C") (pinfunction "C_C") (pintype "passive"))
      (node (ref "D501") (pin "C") (pinfunction "C_C") (pintype "passive"))
      (node (ref "D601") (pin "C") (pinfunction "C_C") (pintype "passive"))
      (node (ref "D801") (pin "C") (pinfunction "C_C") (pintype "passive"))
      (node (ref "D901") (pin "C") (pinfunction "C_C") (pintype "passive"))
      (node (ref "IC1101") (pin "1") (pinfunction "VI_1") (pintype "input"))
      (node (ref "IC1201") (pin "1") (pinfunction "VI_1") (pintype "input"))
      (node (ref "IC1301") (pin "1") (pinfunction "VI_1") (pintype "input"))
      (node (ref "IC1501") (pin "1") (pinfunction "VI_1") (pintype "input"))
      (node (ref "J1001") (pin "1") (pinfunction "1_1") (pintype "passive"))
      (node (ref "J1003") (pin "1") (pinfunction "1_1") (pintype "passive"))
      (node (ref "J1402") (pin "1") (pinfunction "1_1") (pintype "passive"))
      (node (ref "J201") (pin "2") (pinfunction "2_2") (pintype "passive"))
      (node (ref "J202") (pin "1") (pinfunction "1_1") (pintype "passive"))
      (node (ref "J203") (pin "1") (pinfunction "1_1") (pintype "passive"))
      (node (ref "J502") (pin "1") (pinfunction "1_1") (pintype "passive"))
      (node (ref "J602") (pin "1") (pinfunction "1_1") (pintype "passive"))
      (node (ref "J802") (pin "1") (pinfunction "1_1") (pintype "passive"))
      (node (ref "J902") (pin "1") (pinfunction "1_1") (pintype "passive"))
      (node (ref "U1002") (pin "1") (pinfunction "IN_1") (pintype "input"))
      (node (ref "U1002") (pin "3") (pinfunction "EN_3") (pintype "input"))
      (node (ref "U102") (pin "1") (pinfunction "IN_1") (pintype "input"))
      (node (ref "U102") (pin "3") (pinfunction "EN_3") (pintype "input"))
      (node (ref "U1402") (pin "1") (pinfunction "IN_1") (pintype "input"))
      (node (ref "U1402") (pin "3") (pinfunction "EN_3") (pintype "input"))
      (node (ref "U203") (pin "1") (pinfunction "IN_1") (pintype "input"))
      (node (ref "U203") (pin "3") (pinfunction "EN_3") (pintype "input"))
      (node (ref "U304") (pin "1") (pinfunction "IN_1") (pintype "input"))
      (node (ref "U304") (pin "3") (pinfunction "EN_3") (pintype "input"))
      (node (ref "U404") (pin "1") (pinfunction "IN_1") (pintype "input"))
      (node (ref "U404") (pin "3") (pinfunction "EN_3") (pintype "input"))
      (node (ref "U504") (pin "1") (pinfunction "IN_1") (pintype "input"))
      (node (ref "U504") (pin "3") (pinfunction "EN_3") (pintype "input"))
      (node (ref "U604") (pin "1") (pinfunction "IN_1") (pintype "input"))
      (node (ref "U604") (pin "3") (pinfunction "EN_3") (pintype "input"))
      (node (ref "U703") (pin "1") (pinfunction "IN_1") (pintype "input"))
      (node (ref "U703") (pin "3") (pinfunction "EN_3") (pintype "input"))
      (node (ref "U803") (pin "1") (pinfunction "IN_1") (pintype "input"))
      (node (ref "U803") (pin "3") (pinfunction "EN_3") (pintype "input"))
      (node (ref "U902") (pin "1") (pinfunction "IN_1") (pintype "input"))
      (node (ref "U902") (pin "3") (pinfunction "EN_3") (pintype "input"))
      (node (ref "X1601") (pin "1") (pinfunction "1_1") (pintype "passive"))
    )
    (net (code "192") (name "WATER_IN") (class "Default")
      (node (ref "D603") (pin "A") (pinfunction "A_A") (pintype "passive"))
      (node (ref "J1605") (pin "1") (pinfunction "1_1") (pintype "passive"))
      (node (ref "U602") (pin "1") (pinfunction "A_1") (pintype "input"))
    )
    (net (code "193") (name "WATER_MISO") (class "Default")
      (node (ref "J603") (pin "1") (pinfunction "1_1") (pintype "passive"))
      (node (ref "U603") (pin "6") (pinfunction "PB1(MISO)_6") (pintype "bidirectional"))
    )
    (net (code "194") (name "WATER_MOSI") (class "Default")
      (node (ref "J603") (pin "4") (pinfunction "4_4") (pintype "passive"))
      (node (ref "U603") (pin "5") (pinfunction "PB0(MOSI)_5") (pintype "bidirectional"))
    )
    (net (code "195") (name "WATER_OUT") (class "Default")
      (node (ref "D602") (pin "A") (pinfunction "A_A") (pintype "passive"))
      (node (ref "J1606") (pin "2") (pinfunction "2_2") (pintype "passive"))
      (node (ref "S602") (pin "2") (pinfunction "P_2") (pintype "passive"))
      (node (ref "U601") (pin "2") (pinfunction "A_2") (pintype "bidirectional"))
    )
    (net (code "196") (name "WATER_OUT_SWITCH") (class "Default")
      (node (ref "S602") (pin "3") (pinfunction "S_3") (pintype "passive"))
      (node (ref "U603") (pin "3") (pinfunction "PB4(ADC2)_3") (pintype "bidirectional"))
    )
    (net (code "197") (name "WATER_RST") (class "Default")
      (node (ref "J603") (pin "5") (pinfunction "5_5") (pintype "passive"))
      (node (ref "R604") (pin "1") (pinfunction "1_1") (pintype "passive"))
      (node (ref "S601") (pin "3") (pinfunction "2_3") (pintype "passive"))
      (node (ref "S601") (pin "4") (pinfunction "2_4") (pintype "passive"))
      (node (ref "U603") (pin "1") (pinfunction "PB5(NRES)_1") (pintype "bidirectional"))
    )
    (net (code "198") (name "WATER_SCK") (class "Default")
      (node (ref "J601") (pin "1") (pinfunction "1_1") (pintype "passive"))
      (node (ref "J603") (pin "3") (pinfunction "3_3") (pintype "passive"))
      (node (ref "R603") (pin "1") (pinfunction "1_1") (pintype "passive"))
      (node (ref "U603") (pin "7") (pinfunction "PB2(SCK/ADC1)_7") (pintype "bidirectional"))
    )
    (net (code "199") (name "WATER_VCC") (class "Default")
      (node (ref "C601") (pin "2") (pinfunction "2_2") (pintype "passive"))
      (node (ref "C602") (pin "+") (pinfunction "+_+") (pintype "passive"))
      (node (ref "D604") (pin "A") (pinfunction "A_A") (pintype "passive"))
      (node (ref "J603") (pin "2") (pinfunction "2_2") (pintype "passive"))
      (node (ref "R603") (pin "2") (pinfunction "2_2") (pintype "passive"))
      (node (ref "R604") (pin "2") (pinfunction "2_2") (pintype "passive"))
      (node (ref "S602") (pin "1") (pinfunction "O_1") (pintype "passive"))
      (node (ref "TP601") (pin "TP") (pinfunction "TP_TP") (pintype "input"))
      (node (ref "U601") (pin "5") (pinfunction "P$V+_5") (pintype "bidirectional"))
      (node (ref "U602") (pin "5") (pinfunction "VCC_5") (pintype "power_in"))
      (node (ref "U603") (pin "8") (pinfunction "VCC_8") (pintype "bidirectional"))
      (node (ref "U604") (pin "5") (pinfunction "OUT_5") (pintype "passive"))
    )
    (net (code "200") (name "unconnected-(S102-S-Pad3)") (class "Default")
      (node (ref "S102") (pin "3") (pinfunction "S_3") (pintype "passive"))
    )
    (net (code "201") (name "unconnected-(S801-S-Pad3)") (class "Default")
      (node (ref "S801") (pin "3") (pinfunction "S_3") (pintype "passive"))
    )
    (net (code "202") (name "unconnected-(S902-S-Pad3)") (class "Default")
      (node (ref "S902") (pin "3") (pinfunction "S_3") (pintype "passive"))
    )
    (net (code "203") (name "unconnected-(S1002-S-Pad3)") (class "Default")
      (node (ref "S1002") (pin "3") (pinfunction "S_3") (pintype "passive"))
    )
    (net (code "204") (name "unconnected-(S1102-S-Pad3)") (class "Default")
      (node (ref "S1102") (pin "3") (pinfunction "S_3") (pintype "passive"))
    )
    (net (code "205") (name "unconnected-(S1202-S-Pad3)") (class "Default")
      (node (ref "S1202") (pin "3") (pinfunction "S_3") (pintype "passive"))
    )
    (net (code "206") (name "unconnected-(S1302-S-Pad3)") (class "Default")
      (node (ref "S1302") (pin "3") (pinfunction "S_3") (pintype "passive"))
    )
    (net (code "207") (name "unconnected-(S1401-S-Pad3)") (class "Default")
      (node (ref "S1401") (pin "3") (pinfunction "S_3") (pintype "passive"))
    )
    (net (code "208") (name "unconnected-(U102-BP-Pad4)") (class "Default")
      (node (ref "U102") (pin "4") (pinfunction "BP_4") (pintype "input"))
    )
    (net (code "209") (name "unconnected-(U203-BP-Pad4)") (class "Default")
      (node (ref "U203") (pin "4") (pinfunction "BP_4") (pintype "input"))
    )
    (net (code "210") (name "unconnected-(U304-BP-Pad4)") (class "Default")
      (node (ref "U304") (pin "4") (pinfunction "BP_4") (pintype "input"))
    )
    (net (code "211") (name "unconnected-(U404-BP-Pad4)") (class "Default")
      (node (ref "U404") (pin "4") (pinfunction "BP_4") (pintype "input"))
    )
    (net (code "212") (name "unconnected-(U504-BP-Pad4)") (class "Default")
      (node (ref "U504") (pin "4") (pinfunction "BP_4") (pintype "input"))
    )
    (net (code "213") (name "unconnected-(U604-BP-Pad4)") (class "Default")
      (node (ref "U604") (pin "4") (pinfunction "BP_4") (pintype "input"))
    )
    (net (code "214") (name "unconnected-(U703-BP-Pad4)") (class "Default")
      (node (ref "U703") (pin "4") (pinfunction "BP_4") (pintype "input"))
    )
    (net (code "215") (name "unconnected-(U803-BP-Pad4)") (class "Default")
      (node (ref "U803") (pin "4") (pinfunction "BP_4") (pintype "input"))
    )
    (net (code "216") (name "unconnected-(U902-BP-Pad4)") (class "Default")
      (node (ref "U902") (pin "4") (pinfunction "BP_4") (pintype "input"))
    )
    (net (code "217") (name "unconnected-(U1002-BP-Pad4)") (class "Default")
      (node (ref "U1002") (pin "4") (pinfunction "BP_4") (pintype "input"))
    )
    (net (code "218") (name "unconnected-(U1101-BIN1{slash}PH-Pad8)") (class "Default")
      (node (ref "U1101") (pin "8") (pinfunction "BIN1/PH_8") (pintype "bidirectional"))
    )
    (net (code "219") (name "unconnected-(U1101-BIN2{slash}EN-Pad7)") (class "Default")
      (node (ref "U1101") (pin "7") (pinfunction "BIN2/EN_7") (pintype "bidirectional"))
    )
    (net (code "220") (name "unconnected-(U1101-BOUT1-Pad4)") (class "Default")
      (node (ref "U1101") (pin "4") (pinfunction "BOUT1_4") (pintype "bidirectional"))
    )
    (net (code "221") (name "unconnected-(U1101-BOUT2-Pad5)") (class "Default")
      (node (ref "U1101") (pin "5") (pinfunction "BOUT2_5") (pintype "bidirectional"))
    )
    (net (code "222") (name "unconnected-(U1201-BIN1{slash}PH-Pad8)") (class "Default")
      (node (ref "U1201") (pin "8") (pinfunction "BIN1/PH_8") (pintype "bidirectional"))
    )
    (net (code "223") (name "unconnected-(U1201-BIN2{slash}EN-Pad7)") (class "Default")
      (node (ref "U1201") (pin "7") (pinfunction "BIN2/EN_7") (pintype "bidirectional"))
    )
    (net (code "224") (name "unconnected-(U1201-BOUT1-Pad4)") (class "Default")
      (node (ref "U1201") (pin "4") (pinfunction "BOUT1_4") (pintype "bidirectional"))
    )
    (net (code "225") (name "unconnected-(U1201-BOUT2-Pad5)") (class "Default")
      (node (ref "U1201") (pin "5") (pinfunction "BOUT2_5") (pintype "bidirectional"))
    )
    (net (code "226") (name "unconnected-(U1301-BIN1{slash}PH-Pad8)") (class "Default")
      (node (ref "U1301") (pin "8") (pinfunction "BIN1/PH_8") (pintype "bidirectional"))
    )
    (net (code "227") (name "unconnected-(U1301-BIN2{slash}EN-Pad7)") (class "Default")
      (node (ref "U1301") (pin "7") (pinfunction "BIN2/EN_7") (pintype "bidirectional"))
    )
    (net (code "228") (name "unconnected-(U1301-BOUT1-Pad4)") (class "Default")
      (node (ref "U1301") (pin "4") (pinfunction "BOUT1_4") (pintype "bidirectional"))
    )
    (net (code "229") (name "unconnected-(U1301-BOUT2-Pad5)") (class "Default")
      (node (ref "U1301") (pin "5") (pinfunction "BOUT2_5") (pintype "bidirectional"))
    )
    (net (code "230") (name "unconnected-(U1402-BP-Pad4)") (class "Default")
      (node (ref "U1402") (pin "4") (pinfunction "BP_4") (pintype "input"))
    )
  )
)
